# ws2812b-board.net
KiCad netlist of a schematic drawn in EAGLE
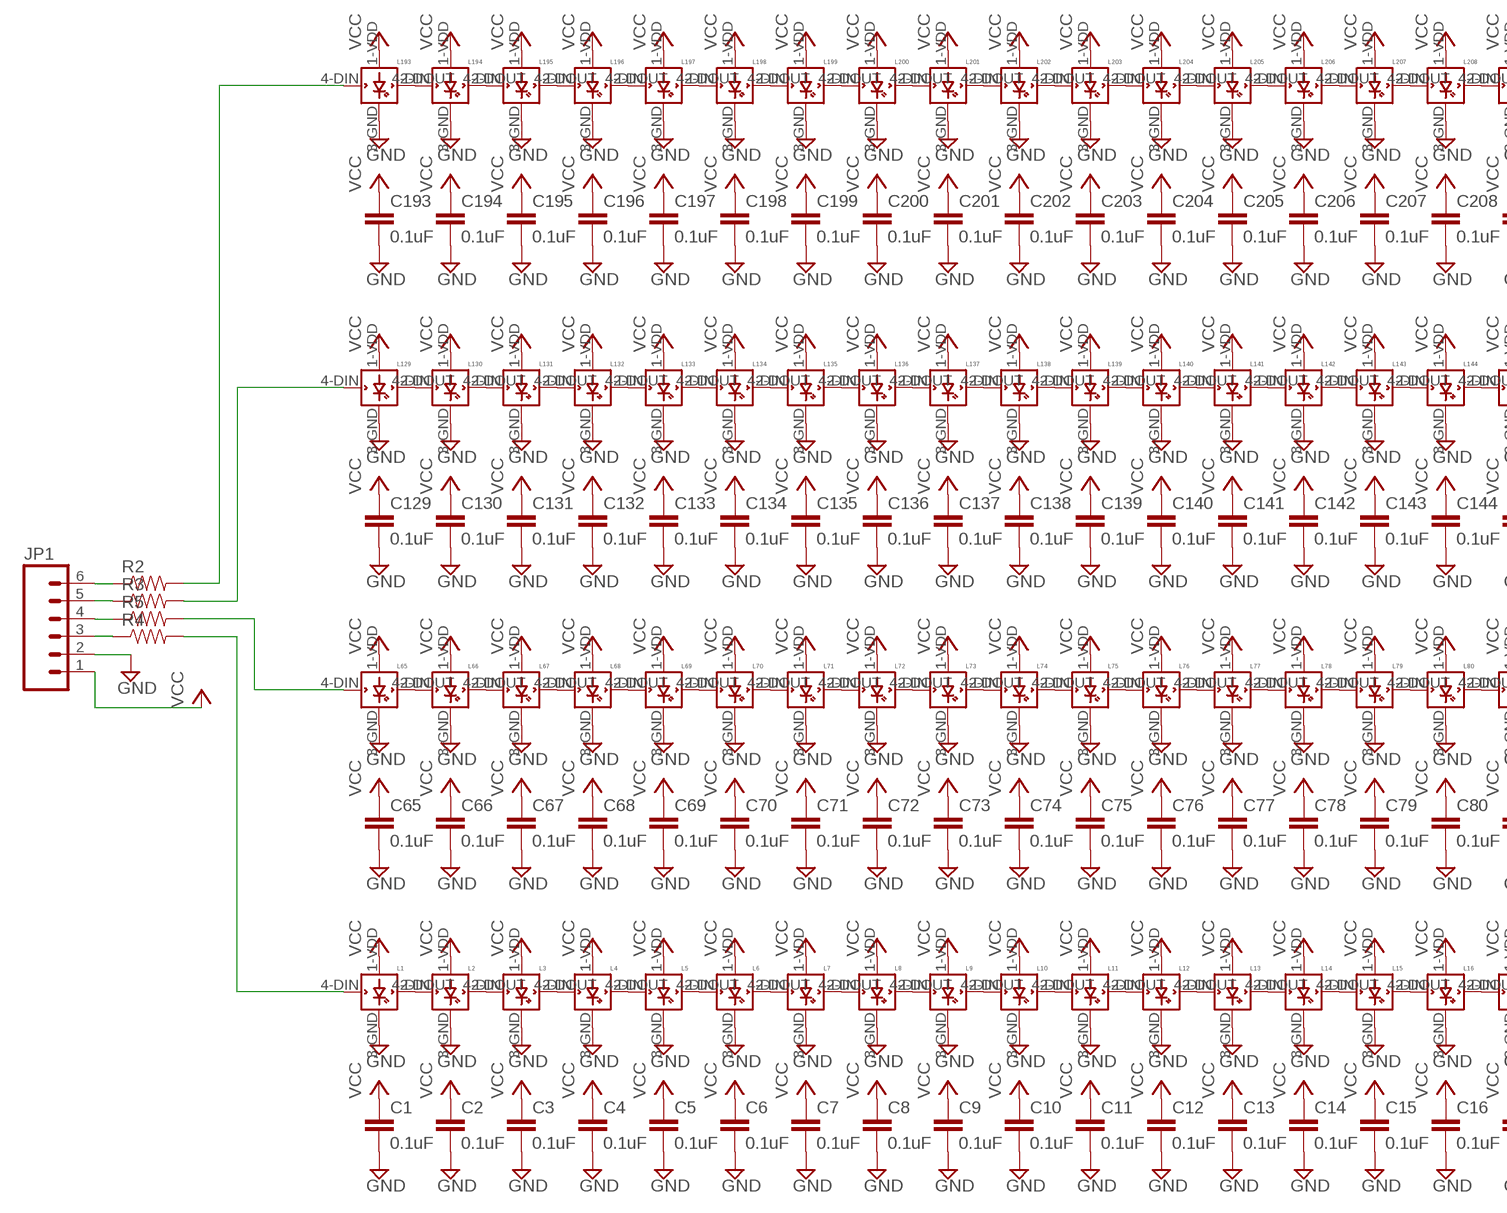
[diagram p0: schematic, sheet 1, part 1 of 2]
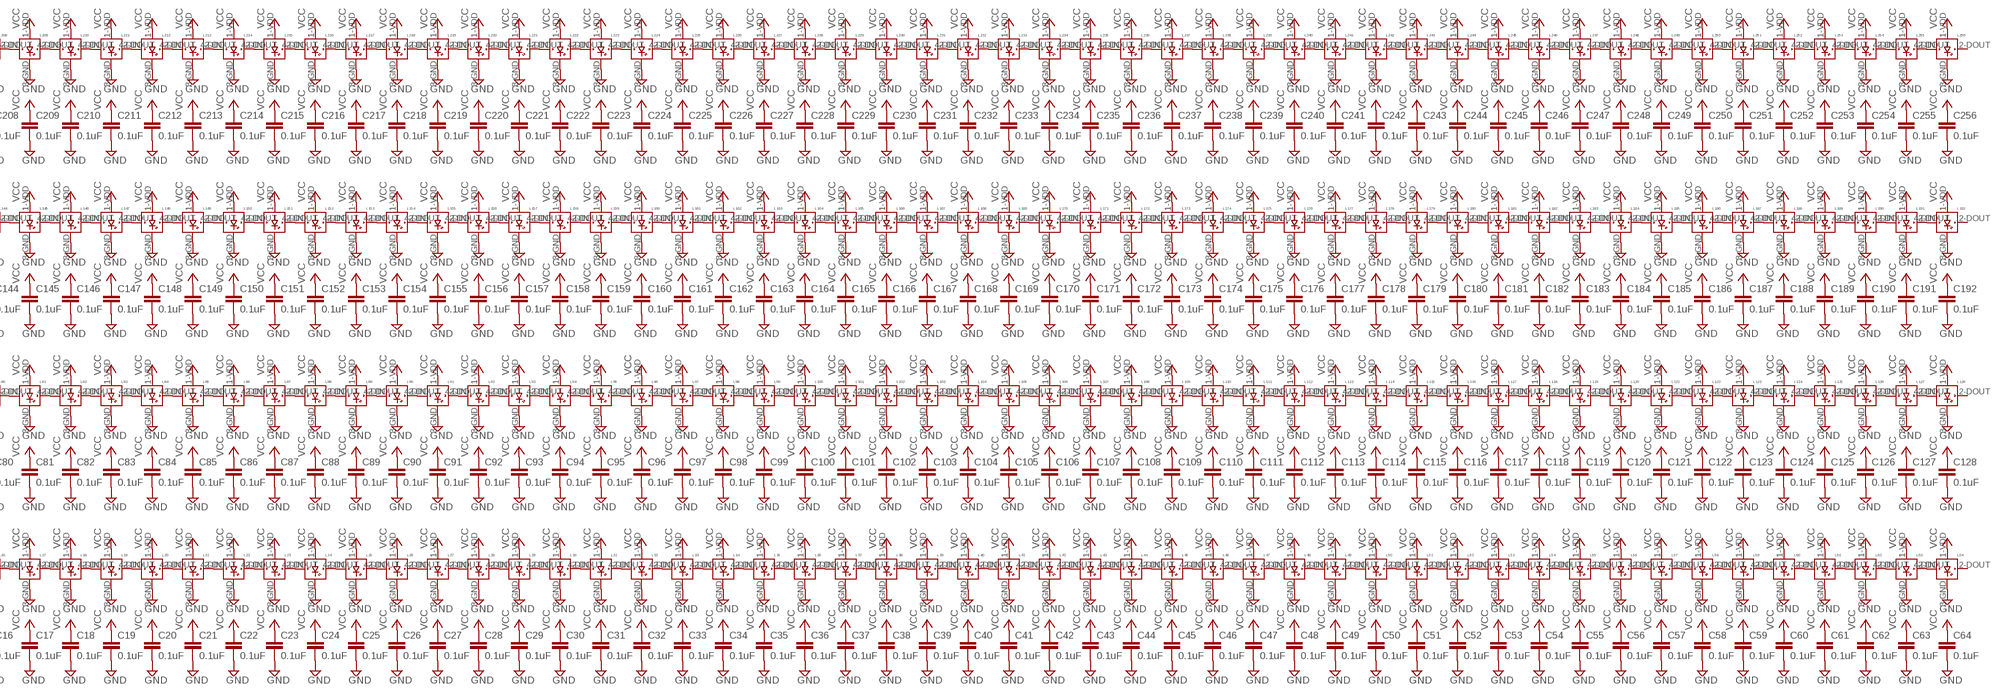
[diagram p1: schematic, sheet 1, part 2 of 2]

(export (version "E")
  (design (tool "Eeschema 10.0.6"))
  (components
    (comp (ref "C1")
      (value "0.1uF")
      (footprint "eagle-import:0603-CAP")
      (libsource (lib "eagle-import") (part "CAP0603-CAP"))
    )
    (comp (ref "C2")
      (value "0.1uF")
      (footprint "eagle-import:0603-CAP")
      (libsource (lib "eagle-import") (part "CAP0603-CAP"))
    )
    (comp (ref "C3")
      (value "0.1uF")
      (footprint "eagle-import:0603-CAP")
      (libsource (lib "eagle-import") (part "CAP0603-CAP"))
    )
    (comp (ref "C4")
      (value "0.1uF")
      (footprint "eagle-import:0603-CAP")
      (libsource (lib "eagle-import") (part "CAP0603-CAP"))
    )
    (comp (ref "C5")
      (value "0.1uF")
      (footprint "eagle-import:0603-CAP")
      (libsource (lib "eagle-import") (part "CAP0603-CAP"))
    )
    (comp (ref "C6")
      (value "0.1uF")
      (footprint "eagle-import:0603-CAP")
      (libsource (lib "eagle-import") (part "CAP0603-CAP"))
    )
    (comp (ref "C7")
      (value "0.1uF")
      (footprint "eagle-import:0603-CAP")
      (libsource (lib "eagle-import") (part "CAP0603-CAP"))
    )
    (comp (ref "C8")
      (value "0.1uF")
      (footprint "eagle-import:0603-CAP")
      (libsource (lib "eagle-import") (part "CAP0603-CAP"))
    )
    (comp (ref "C9")
      (value "0.1uF")
      (footprint "eagle-import:0603-CAP")
      (libsource (lib "eagle-import") (part "CAP0603-CAP"))
    )
    (comp (ref "C10")
      (value "0.1uF")
      (footprint "eagle-import:0603-CAP")
      (libsource (lib "eagle-import") (part "CAP0603-CAP"))
    )
    (comp (ref "C11")
      (value "0.1uF")
      (footprint "eagle-import:0603-CAP")
      (libsource (lib "eagle-import") (part "CAP0603-CAP"))
    )
    (comp (ref "C12")
      (value "0.1uF")
      (footprint "eagle-import:0603-CAP")
      (libsource (lib "eagle-import") (part "CAP0603-CAP"))
    )
    (comp (ref "C13")
      (value "0.1uF")
      (footprint "eagle-import:0603-CAP")
      (libsource (lib "eagle-import") (part "CAP0603-CAP"))
    )
    (comp (ref "C14")
      (value "0.1uF")
      (footprint "eagle-import:0603-CAP")
      (libsource (lib "eagle-import") (part "CAP0603-CAP"))
    )
    (comp (ref "C15")
      (value "0.1uF")
      (footprint "eagle-import:0603-CAP")
      (libsource (lib "eagle-import") (part "CAP0603-CAP"))
    )
    (comp (ref "C16")
      (value "0.1uF")
      (footprint "eagle-import:0603-CAP")
      (libsource (lib "eagle-import") (part "CAP0603-CAP"))
    )
    (comp (ref "C17")
      (value "0.1uF")
      (footprint "eagle-import:0603-CAP")
      (libsource (lib "eagle-import") (part "CAP0603-CAP"))
    )
    (comp (ref "C18")
      (value "0.1uF")
      (footprint "eagle-import:0603-CAP")
      (libsource (lib "eagle-import") (part "CAP0603-CAP"))
    )
    (comp (ref "C19")
      (value "0.1uF")
      (footprint "eagle-import:0603-CAP")
      (libsource (lib "eagle-import") (part "CAP0603-CAP"))
    )
    (comp (ref "C20")
      (value "0.1uF")
      (footprint "eagle-import:0603-CAP")
      (libsource (lib "eagle-import") (part "CAP0603-CAP"))
    )
    (comp (ref "C21")
      (value "0.1uF")
      (footprint "eagle-import:0603-CAP")
      (libsource (lib "eagle-import") (part "CAP0603-CAP"))
    )
    (comp (ref "C22")
      (value "0.1uF")
      (footprint "eagle-import:0603-CAP")
      (libsource (lib "eagle-import") (part "CAP0603-CAP"))
    )
    (comp (ref "C23")
      (value "0.1uF")
      (footprint "eagle-import:0603-CAP")
      (libsource (lib "eagle-import") (part "CAP0603-CAP"))
    )
    (comp (ref "C24")
      (value "0.1uF")
      (footprint "eagle-import:0603-CAP")
      (libsource (lib "eagle-import") (part "CAP0603-CAP"))
    )
    (comp (ref "C25")
      (value "0.1uF")
      (footprint "eagle-import:0603-CAP")
      (libsource (lib "eagle-import") (part "CAP0603-CAP"))
    )
    (comp (ref "C26")
      (value "0.1uF")
      (footprint "eagle-import:0603-CAP")
      (libsource (lib "eagle-import") (part "CAP0603-CAP"))
    )
    (comp (ref "C27")
      (value "0.1uF")
      (footprint "eagle-import:0603-CAP")
      (libsource (lib "eagle-import") (part "CAP0603-CAP"))
    )
    (comp (ref "C28")
      (value "0.1uF")
      (footprint "eagle-import:0603-CAP")
      (libsource (lib "eagle-import") (part "CAP0603-CAP"))
    )
    (comp (ref "C29")
      (value "0.1uF")
      (footprint "eagle-import:0603-CAP")
      (libsource (lib "eagle-import") (part "CAP0603-CAP"))
    )
    (comp (ref "C30")
      (value "0.1uF")
      (footprint "eagle-import:0603-CAP")
      (libsource (lib "eagle-import") (part "CAP0603-CAP"))
    )
    (comp (ref "C31")
      (value "0.1uF")
      (footprint "eagle-import:0603-CAP")
      (libsource (lib "eagle-import") (part "CAP0603-CAP"))
    )
    (comp (ref "C32")
      (value "0.1uF")
      (footprint "eagle-import:0603-CAP")
      (libsource (lib "eagle-import") (part "CAP0603-CAP"))
    )
    (comp (ref "C33")
      (value "0.1uF")
      (footprint "eagle-import:0603-CAP")
      (libsource (lib "eagle-import") (part "CAP0603-CAP"))
    )
    (comp (ref "C34")
      (value "0.1uF")
      (footprint "eagle-import:0603-CAP")
      (libsource (lib "eagle-import") (part "CAP0603-CAP"))
    )
    (comp (ref "C35")
      (value "0.1uF")
      (footprint "eagle-import:0603-CAP")
      (libsource (lib "eagle-import") (part "CAP0603-CAP"))
    )
    (comp (ref "C36")
      (value "0.1uF")
      (footprint "eagle-import:0603-CAP")
      (libsource (lib "eagle-import") (part "CAP0603-CAP"))
    )
    (comp (ref "C37")
      (value "0.1uF")
      (footprint "eagle-import:0603-CAP")
      (libsource (lib "eagle-import") (part "CAP0603-CAP"))
    )
    (comp (ref "C38")
      (value "0.1uF")
      (footprint "eagle-import:0603-CAP")
      (libsource (lib "eagle-import") (part "CAP0603-CAP"))
    )
    (comp (ref "C39")
      (value "0.1uF")
      (footprint "eagle-import:0603-CAP")
      (libsource (lib "eagle-import") (part "CAP0603-CAP"))
    )
    (comp (ref "C40")
      (value "0.1uF")
      (footprint "eagle-import:0603-CAP")
      (libsource (lib "eagle-import") (part "CAP0603-CAP"))
    )
    (comp (ref "C41")
      (value "0.1uF")
      (footprint "eagle-import:0603-CAP")
      (libsource (lib "eagle-import") (part "CAP0603-CAP"))
    )
    (comp (ref "C42")
      (value "0.1uF")
      (footprint "eagle-import:0603-CAP")
      (libsource (lib "eagle-import") (part "CAP0603-CAP"))
    )
    (comp (ref "C43")
      (value "0.1uF")
      (footprint "eagle-import:0603-CAP")
      (libsource (lib "eagle-import") (part "CAP0603-CAP"))
    )
    (comp (ref "C44")
      (value "0.1uF")
      (footprint "eagle-import:0603-CAP")
      (libsource (lib "eagle-import") (part "CAP0603-CAP"))
    )
    (comp (ref "C45")
      (value "0.1uF")
      (footprint "eagle-import:0603-CAP")
      (libsource (lib "eagle-import") (part "CAP0603-CAP"))
    )
    (comp (ref "C46")
      (value "0.1uF")
      (footprint "eagle-import:0603-CAP")
      (libsource (lib "eagle-import") (part "CAP0603-CAP"))
    )
    (comp (ref "C47")
      (value "0.1uF")
      (footprint "eagle-import:0603-CAP")
      (libsource (lib "eagle-import") (part "CAP0603-CAP"))
    )
    (comp (ref "C48")
      (value "0.1uF")
      (footprint "eagle-import:0603-CAP")
      (libsource (lib "eagle-import") (part "CAP0603-CAP"))
    )
    (comp (ref "C49")
      (value "0.1uF")
      (footprint "eagle-import:0603-CAP")
      (libsource (lib "eagle-import") (part "CAP0603-CAP"))
    )
    (comp (ref "C50")
      (value "0.1uF")
      (footprint "eagle-import:0603-CAP")
      (libsource (lib "eagle-import") (part "CAP0603-CAP"))
    )
    (comp (ref "C51")
      (value "0.1uF")
      (footprint "eagle-import:0603-CAP")
      (libsource (lib "eagle-import") (part "CAP0603-CAP"))
    )
    (comp (ref "C52")
      (value "0.1uF")
      (footprint "eagle-import:0603-CAP")
      (libsource (lib "eagle-import") (part "CAP0603-CAP"))
    )
    (comp (ref "C53")
      (value "0.1uF")
      (footprint "eagle-import:0603-CAP")
      (libsource (lib "eagle-import") (part "CAP0603-CAP"))
    )
    (comp (ref "C54")
      (value "0.1uF")
      (footprint "eagle-import:0603-CAP")
      (libsource (lib "eagle-import") (part "CAP0603-CAP"))
    )
    (comp (ref "C55")
      (value "0.1uF")
      (footprint "eagle-import:0603-CAP")
      (libsource (lib "eagle-import") (part "CAP0603-CAP"))
    )
    (comp (ref "C56")
      (value "0.1uF")
      (footprint "eagle-import:0603-CAP")
      (libsource (lib "eagle-import") (part "CAP0603-CAP"))
    )
    (comp (ref "C57")
      (value "0.1uF")
      (footprint "eagle-import:0603-CAP")
      (libsource (lib "eagle-import") (part "CAP0603-CAP"))
    )
    (comp (ref "C58")
      (value "0.1uF")
      (footprint "eagle-import:0603-CAP")
      (libsource (lib "eagle-import") (part "CAP0603-CAP"))
    )
    (comp (ref "C59")
      (value "0.1uF")
      (footprint "eagle-import:0603-CAP")
      (libsource (lib "eagle-import") (part "CAP0603-CAP"))
    )
    (comp (ref "C60")
      (value "0.1uF")
      (footprint "eagle-import:0603-CAP")
      (libsource (lib "eagle-import") (part "CAP0603-CAP"))
    )
    (comp (ref "C61")
      (value "0.1uF")
      (footprint "eagle-import:0603-CAP")
      (libsource (lib "eagle-import") (part "CAP0603-CAP"))
    )
    (comp (ref "C62")
      (value "0.1uF")
      (footprint "eagle-import:0603-CAP")
      (libsource (lib "eagle-import") (part "CAP0603-CAP"))
    )
    (comp (ref "C63")
      (value "0.1uF")
      (footprint "eagle-import:0603-CAP")
      (libsource (lib "eagle-import") (part "CAP0603-CAP"))
    )
    (comp (ref "C64")
      (value "0.1uF")
      (footprint "eagle-import:0603-CAP")
      (libsource (lib "eagle-import") (part "CAP0603-CAP"))
    )
    (comp (ref "C65")
      (value "0.1uF")
      (footprint "eagle-import:0603-CAP")
      (libsource (lib "eagle-import") (part "CAP0603-CAP"))
    )
    (comp (ref "C66")
      (value "0.1uF")
      (footprint "eagle-import:0603-CAP")
      (libsource (lib "eagle-import") (part "CAP0603-CAP"))
    )
    (comp (ref "C67")
      (value "0.1uF")
      (footprint "eagle-import:0603-CAP")
      (libsource (lib "eagle-import") (part "CAP0603-CAP"))
    )
    (comp (ref "C68")
      (value "0.1uF")
      (footprint "eagle-import:0603-CAP")
      (libsource (lib "eagle-import") (part "CAP0603-CAP"))
    )
    (comp (ref "C69")
      (value "0.1uF")
      (footprint "eagle-import:0603-CAP")
      (libsource (lib "eagle-import") (part "CAP0603-CAP"))
    )
    (comp (ref "C70")
      (value "0.1uF")
      (footprint "eagle-import:0603-CAP")
      (libsource (lib "eagle-import") (part "CAP0603-CAP"))
    )
    (comp (ref "C71")
      (value "0.1uF")
      (footprint "eagle-import:0603-CAP")
      (libsource (lib "eagle-import") (part "CAP0603-CAP"))
    )
    (comp (ref "C72")
      (value "0.1uF")
      (footprint "eagle-import:0603-CAP")
      (libsource (lib "eagle-import") (part "CAP0603-CAP"))
    )
    (comp (ref "C73")
      (value "0.1uF")
      (footprint "eagle-import:0603-CAP")
      (libsource (lib "eagle-import") (part "CAP0603-CAP"))
    )
    (comp (ref "C74")
      (value "0.1uF")
      (footprint "eagle-import:0603-CAP")
      (libsource (lib "eagle-import") (part "CAP0603-CAP"))
    )
    (comp (ref "C75")
      (value "0.1uF")
      (footprint "eagle-import:0603-CAP")
      (libsource (lib "eagle-import") (part "CAP0603-CAP"))
    )
    (comp (ref "C76")
      (value "0.1uF")
      (footprint "eagle-import:0603-CAP")
      (libsource (lib "eagle-import") (part "CAP0603-CAP"))
    )
    (comp (ref "C77")
      (value "0.1uF")
      (footprint "eagle-import:0603-CAP")
      (libsource (lib "eagle-import") (part "CAP0603-CAP"))
    )
    (comp (ref "C78")
      (value "0.1uF")
      (footprint "eagle-import:0603-CAP")
      (libsource (lib "eagle-import") (part "CAP0603-CAP"))
    )
    (comp (ref "C79")
      (value "0.1uF")
      (footprint "eagle-import:0603-CAP")
      (libsource (lib "eagle-import") (part "CAP0603-CAP"))
    )
    (comp (ref "C80")
      (value "0.1uF")
      (footprint "eagle-import:0603-CAP")
      (libsource (lib "eagle-import") (part "CAP0603-CAP"))
    )
    (comp (ref "C81")
      (value "0.1uF")
      (footprint "eagle-import:0603-CAP")
      (libsource (lib "eagle-import") (part "CAP0603-CAP"))
    )
    (comp (ref "C82")
      (value "0.1uF")
      (footprint "eagle-import:0603-CAP")
      (libsource (lib "eagle-import") (part "CAP0603-CAP"))
    )
    (comp (ref "C83")
      (value "0.1uF")
      (footprint "eagle-import:0603-CAP")
      (libsource (lib "eagle-import") (part "CAP0603-CAP"))
    )
    (comp (ref "C84")
      (value "0.1uF")
      (footprint "eagle-import:0603-CAP")
      (libsource (lib "eagle-import") (part "CAP0603-CAP"))
    )
    (comp (ref "C85")
      (value "0.1uF")
      (footprint "eagle-import:0603-CAP")
      (libsource (lib "eagle-import") (part "CAP0603-CAP"))
    )
    (comp (ref "C86")
      (value "0.1uF")
      (footprint "eagle-import:0603-CAP")
      (libsource (lib "eagle-import") (part "CAP0603-CAP"))
    )
    (comp (ref "C87")
      (value "0.1uF")
      (footprint "eagle-import:0603-CAP")
      (libsource (lib "eagle-import") (part "CAP0603-CAP"))
    )
    (comp (ref "C88")
      (value "0.1uF")
      (footprint "eagle-import:0603-CAP")
      (libsource (lib "eagle-import") (part "CAP0603-CAP"))
    )
    (comp (ref "C89")
      (value "0.1uF")
      (footprint "eagle-import:0603-CAP")
      (libsource (lib "eagle-import") (part "CAP0603-CAP"))
    )
    (comp (ref "C90")
      (value "0.1uF")
      (footprint "eagle-import:0603-CAP")
      (libsource (lib "eagle-import") (part "CAP0603-CAP"))
    )
    (comp (ref "C91")
      (value "0.1uF")
      (footprint "eagle-import:0603-CAP")
      (libsource (lib "eagle-import") (part "CAP0603-CAP"))
    )
    (comp (ref "C92")
      (value "0.1uF")
      (footprint "eagle-import:0603-CAP")
      (libsource (lib "eagle-import") (part "CAP0603-CAP"))
    )
    (comp (ref "C93")
      (value "0.1uF")
      (footprint "eagle-import:0603-CAP")
      (libsource (lib "eagle-import") (part "CAP0603-CAP"))
    )
    (comp (ref "C94")
      (value "0.1uF")
      (footprint "eagle-import:0603-CAP")
      (libsource (lib "eagle-import") (part "CAP0603-CAP"))
    )
    (comp (ref "C95")
      (value "0.1uF")
      (footprint "eagle-import:0603-CAP")
      (libsource (lib "eagle-import") (part "CAP0603-CAP"))
    )
    (comp (ref "C96")
      (value "0.1uF")
      (footprint "eagle-import:0603-CAP")
      (libsource (lib "eagle-import") (part "CAP0603-CAP"))
    )
    (comp (ref "C97")
      (value "0.1uF")
      (footprint "eagle-import:0603-CAP")
      (libsource (lib "eagle-import") (part "CAP0603-CAP"))
    )
    (comp (ref "C98")
      (value "0.1uF")
      (footprint "eagle-import:0603-CAP")
      (libsource (lib "eagle-import") (part "CAP0603-CAP"))
    )
    (comp (ref "C99")
      (value "0.1uF")
      (footprint "eagle-import:0603-CAP")
      (libsource (lib "eagle-import") (part "CAP0603-CAP"))
    )
    (comp (ref "C100")
      (value "0.1uF")
      (footprint "eagle-import:0603-CAP")
      (libsource (lib "eagle-import") (part "CAP0603-CAP"))
    )
    (comp (ref "C101")
      (value "0.1uF")
      (footprint "eagle-import:0603-CAP")
      (libsource (lib "eagle-import") (part "CAP0603-CAP"))
    )
    (comp (ref "C102")
      (value "0.1uF")
      (footprint "eagle-import:0603-CAP")
      (libsource (lib "eagle-import") (part "CAP0603-CAP"))
    )
    (comp (ref "C103")
      (value "0.1uF")
      (footprint "eagle-import:0603-CAP")
      (libsource (lib "eagle-import") (part "CAP0603-CAP"))
    )
    (comp (ref "C104")
      (value "0.1uF")
      (footprint "eagle-import:0603-CAP")
      (libsource (lib "eagle-import") (part "CAP0603-CAP"))
    )
    (comp (ref "C105")
      (value "0.1uF")
      (footprint "eagle-import:0603-CAP")
      (libsource (lib "eagle-import") (part "CAP0603-CAP"))
    )
    (comp (ref "C106")
      (value "0.1uF")
      (footprint "eagle-import:0603-CAP")
      (libsource (lib "eagle-import") (part "CAP0603-CAP"))
    )
    (comp (ref "C107")
      (value "0.1uF")
      (footprint "eagle-import:0603-CAP")
      (libsource (lib "eagle-import") (part "CAP0603-CAP"))
    )
    (comp (ref "C108")
      (value "0.1uF")
      (footprint "eagle-import:0603-CAP")
      (libsource (lib "eagle-import") (part "CAP0603-CAP"))
    )
    (comp (ref "C109")
      (value "0.1uF")
      (footprint "eagle-import:0603-CAP")
      (libsource (lib "eagle-import") (part "CAP0603-CAP"))
    )
    (comp (ref "C110")
      (value "0.1uF")
      (footprint "eagle-import:0603-CAP")
      (libsource (lib "eagle-import") (part "CAP0603-CAP"))
    )
    (comp (ref "C111")
      (value "0.1uF")
      (footprint "eagle-import:0603-CAP")
      (libsource (lib "eagle-import") (part "CAP0603-CAP"))
    )
    (comp (ref "C112")
      (value "0.1uF")
      (footprint "eagle-import:0603-CAP")
      (libsource (lib "eagle-import") (part "CAP0603-CAP"))
    )
    (comp (ref "C113")
      (value "0.1uF")
      (footprint "eagle-import:0603-CAP")
      (libsource (lib "eagle-import") (part "CAP0603-CAP"))
    )
    (comp (ref "C114")
      (value "0.1uF")
      (footprint "eagle-import:0603-CAP")
      (libsource (lib "eagle-import") (part "CAP0603-CAP"))
    )
    (comp (ref "C115")
      (value "0.1uF")
      (footprint "eagle-import:0603-CAP")
      (libsource (lib "eagle-import") (part "CAP0603-CAP"))
    )
    (comp (ref "C116")
      (value "0.1uF")
      (footprint "eagle-import:0603-CAP")
      (libsource (lib "eagle-import") (part "CAP0603-CAP"))
    )
    (comp (ref "C117")
      (value "0.1uF")
      (footprint "eagle-import:0603-CAP")
      (libsource (lib "eagle-import") (part "CAP0603-CAP"))
    )
    (comp (ref "C118")
      (value "0.1uF")
      (footprint "eagle-import:0603-CAP")
      (libsource (lib "eagle-import") (part "CAP0603-CAP"))
    )
    (comp (ref "C119")
      (value "0.1uF")
      (footprint "eagle-import:0603-CAP")
      (libsource (lib "eagle-import") (part "CAP0603-CAP"))
    )
    (comp (ref "C120")
      (value "0.1uF")
      (footprint "eagle-import:0603-CAP")
      (libsource (lib "eagle-import") (part "CAP0603-CAP"))
    )
    (comp (ref "C121")
      (value "0.1uF")
      (footprint "eagle-import:0603-CAP")
      (libsource (lib "eagle-import") (part "CAP0603-CAP"))
    )
    (comp (ref "C122")
      (value "0.1uF")
      (footprint "eagle-import:0603-CAP")
      (libsource (lib "eagle-import") (part "CAP0603-CAP"))
    )
    (comp (ref "C123")
      (value "0.1uF")
      (footprint "eagle-import:0603-CAP")
      (libsource (lib "eagle-import") (part "CAP0603-CAP"))
    )
    (comp (ref "C124")
      (value "0.1uF")
      (footprint "eagle-import:0603-CAP")
      (libsource (lib "eagle-import") (part "CAP0603-CAP"))
    )
    (comp (ref "C125")
      (value "0.1uF")
      (footprint "eagle-import:0603-CAP")
      (libsource (lib "eagle-import") (part "CAP0603-CAP"))
    )
    (comp (ref "C126")
      (value "0.1uF")
      (footprint "eagle-import:0603-CAP")
      (libsource (lib "eagle-import") (part "CAP0603-CAP"))
    )
    (comp (ref "C127")
      (value "0.1uF")
      (footprint "eagle-import:0603-CAP")
      (libsource (lib "eagle-import") (part "CAP0603-CAP"))
    )
    (comp (ref "C128")
      (value "0.1uF")
      (footprint "eagle-import:0603-CAP")
      (libsource (lib "eagle-import") (part "CAP0603-CAP"))
    )
    (comp (ref "C129")
      (value "0.1uF")
      (footprint "eagle-import:0603-CAP")
      (libsource (lib "eagle-import") (part "CAP0603-CAP"))
    )
    (comp (ref "C130")
      (value "0.1uF")
      (footprint "eagle-import:0603-CAP")
      (libsource (lib "eagle-import") (part "CAP0603-CAP"))
    )
    (comp (ref "C131")
      (value "0.1uF")
      (footprint "eagle-import:0603-CAP")
      (libsource (lib "eagle-import") (part "CAP0603-CAP"))
    )
    (comp (ref "C132")
      (value "0.1uF")
      (footprint "eagle-import:0603-CAP")
      (libsource (lib "eagle-import") (part "CAP0603-CAP"))
    )
    (comp (ref "C133")
      (value "0.1uF")
      (footprint "eagle-import:0603-CAP")
      (libsource (lib "eagle-import") (part "CAP0603-CAP"))
    )
    (comp (ref "C134")
      (value "0.1uF")
      (footprint "eagle-import:0603-CAP")
      (libsource (lib "eagle-import") (part "CAP0603-CAP"))
    )
    (comp (ref "C135")
      (value "0.1uF")
      (footprint "eagle-import:0603-CAP")
      (libsource (lib "eagle-import") (part "CAP0603-CAP"))
    )
    (comp (ref "C136")
      (value "0.1uF")
      (footprint "eagle-import:0603-CAP")
      (libsource (lib "eagle-import") (part "CAP0603-CAP"))
    )
    (comp (ref "C137")
      (value "0.1uF")
      (footprint "eagle-import:0603-CAP")
      (libsource (lib "eagle-import") (part "CAP0603-CAP"))
    )
    (comp (ref "C138")
      (value "0.1uF")
      (footprint "eagle-import:0603-CAP")
      (libsource (lib "eagle-import") (part "CAP0603-CAP"))
    )
    (comp (ref "C139")
      (value "0.1uF")
      (footprint "eagle-import:0603-CAP")
      (libsource (lib "eagle-import") (part "CAP0603-CAP"))
    )
    (comp (ref "C140")
      (value "0.1uF")
      (footprint "eagle-import:0603-CAP")
      (libsource (lib "eagle-import") (part "CAP0603-CAP"))
    )
    (comp (ref "C141")
      (value "0.1uF")
      (footprint "eagle-import:0603-CAP")
      (libsource (lib "eagle-import") (part "CAP0603-CAP"))
    )
    (comp (ref "C142")
      (value "0.1uF")
      (footprint "eagle-import:0603-CAP")
      (libsource (lib "eagle-import") (part "CAP0603-CAP"))
    )
    (comp (ref "C143")
      (value "0.1uF")
      (footprint "eagle-import:0603-CAP")
      (libsource (lib "eagle-import") (part "CAP0603-CAP"))
    )
    (comp (ref "C144")
      (value "0.1uF")
      (footprint "eagle-import:0603-CAP")
      (libsource (lib "eagle-import") (part "CAP0603-CAP"))
    )
    (comp (ref "C145")
      (value "0.1uF")
      (footprint "eagle-import:0603-CAP")
      (libsource (lib "eagle-import") (part "CAP0603-CAP"))
    )
    (comp (ref "C146")
      (value "0.1uF")
      (footprint "eagle-import:0603-CAP")
      (libsource (lib "eagle-import") (part "CAP0603-CAP"))
    )
    (comp (ref "C147")
      (value "0.1uF")
      (footprint "eagle-import:0603-CAP")
      (libsource (lib "eagle-import") (part "CAP0603-CAP"))
    )
    (comp (ref "C148")
      (value "0.1uF")
      (footprint "eagle-import:0603-CAP")
      (libsource (lib "eagle-import") (part "CAP0603-CAP"))
    )
    (comp (ref "C149")
      (value "0.1uF")
      (footprint "eagle-import:0603-CAP")
      (libsource (lib "eagle-import") (part "CAP0603-CAP"))
    )
    (comp (ref "C150")
      (value "0.1uF")
      (footprint "eagle-import:0603-CAP")
      (libsource (lib "eagle-import") (part "CAP0603-CAP"))
    )
    (comp (ref "C151")
      (value "0.1uF")
      (footprint "eagle-import:0603-CAP")
      (libsource (lib "eagle-import") (part "CAP0603-CAP"))
    )
    (comp (ref "C152")
      (value "0.1uF")
      (footprint "eagle-import:0603-CAP")
      (libsource (lib "eagle-import") (part "CAP0603-CAP"))
    )
    (comp (ref "C153")
      (value "0.1uF")
      (footprint "eagle-import:0603-CAP")
      (libsource (lib "eagle-import") (part "CAP0603-CAP"))
    )
    (comp (ref "C154")
      (value "0.1uF")
      (footprint "eagle-import:0603-CAP")
      (libsource (lib "eagle-import") (part "CAP0603-CAP"))
    )
    (comp (ref "C155")
      (value "0.1uF")
      (footprint "eagle-import:0603-CAP")
      (libsource (lib "eagle-import") (part "CAP0603-CAP"))
    )
    (comp (ref "C156")
      (value "0.1uF")
      (footprint "eagle-import:0603-CAP")
      (libsource (lib "eagle-import") (part "CAP0603-CAP"))
    )
    (comp (ref "C157")
      (value "0.1uF")
      (footprint "eagle-import:0603-CAP")
      (libsource (lib "eagle-import") (part "CAP0603-CAP"))
    )
    (comp (ref "C158")
      (value "0.1uF")
      (footprint "eagle-import:0603-CAP")
      (libsource (lib "eagle-import") (part "CAP0603-CAP"))
    )
    (comp (ref "C159")
      (value "0.1uF")
      (footprint "eagle-import:0603-CAP")
      (libsource (lib "eagle-import") (part "CAP0603-CAP"))
    )
    (comp (ref "C160")
      (value "0.1uF")
      (footprint "eagle-import:0603-CAP")
      (libsource (lib "eagle-import") (part "CAP0603-CAP"))
    )
    (comp (ref "C161")
      (value "0.1uF")
      (footprint "eagle-import:0603-CAP")
      (libsource (lib "eagle-import") (part "CAP0603-CAP"))
    )
    (comp (ref "C162")
      (value "0.1uF")
      (footprint "eagle-import:0603-CAP")
      (libsource (lib "eagle-import") (part "CAP0603-CAP"))
    )
    (comp (ref "C163")
      (value "0.1uF")
      (footprint "eagle-import:0603-CAP")
      (libsource (lib "eagle-import") (part "CAP0603-CAP"))
    )
    (comp (ref "C164")
      (value "0.1uF")
      (footprint "eagle-import:0603-CAP")
      (libsource (lib "eagle-import") (part "CAP0603-CAP"))
    )
    (comp (ref "C165")
      (value "0.1uF")
      (footprint "eagle-import:0603-CAP")
      (libsource (lib "eagle-import") (part "CAP0603-CAP"))
    )
    (comp (ref "C166")
      (value "0.1uF")
      (footprint "eagle-import:0603-CAP")
      (libsource (lib "eagle-import") (part "CAP0603-CAP"))
    )
    (comp (ref "C167")
      (value "0.1uF")
      (footprint "eagle-import:0603-CAP")
      (libsource (lib "eagle-import") (part "CAP0603-CAP"))
    )
    (comp (ref "C168")
      (value "0.1uF")
      (footprint "eagle-import:0603-CAP")
      (libsource (lib "eagle-import") (part "CAP0603-CAP"))
    )
    (comp (ref "C169")
      (value "0.1uF")
      (footprint "eagle-import:0603-CAP")
      (libsource (lib "eagle-import") (part "CAP0603-CAP"))
    )
    (comp (ref "C170")
      (value "0.1uF")
      (footprint "eagle-import:0603-CAP")
      (libsource (lib "eagle-import") (part "CAP0603-CAP"))
    )
    (comp (ref "C171")
      (value "0.1uF")
      (footprint "eagle-import:0603-CAP")
      (libsource (lib "eagle-import") (part "CAP0603-CAP"))
    )
    (comp (ref "C172")
      (value "0.1uF")
      (footprint "eagle-import:0603-CAP")
      (libsource (lib "eagle-import") (part "CAP0603-CAP"))
    )
    (comp (ref "C173")
      (value "0.1uF")
      (footprint "eagle-import:0603-CAP")
      (libsource (lib "eagle-import") (part "CAP0603-CAP"))
    )
    (comp (ref "C174")
      (value "0.1uF")
      (footprint "eagle-import:0603-CAP")
      (libsource (lib "eagle-import") (part "CAP0603-CAP"))
    )
    (comp (ref "C175")
      (value "0.1uF")
      (footprint "eagle-import:0603-CAP")
      (libsource (lib "eagle-import") (part "CAP0603-CAP"))
    )
    (comp (ref "C176")
      (value "0.1uF")
      (footprint "eagle-import:0603-CAP")
      (libsource (lib "eagle-import") (part "CAP0603-CAP"))
    )
    (comp (ref "C177")
      (value "0.1uF")
      (footprint "eagle-import:0603-CAP")
      (libsource (lib "eagle-import") (part "CAP0603-CAP"))
    )
    (comp (ref "C178")
      (value "0.1uF")
      (footprint "eagle-import:0603-CAP")
      (libsource (lib "eagle-import") (part "CAP0603-CAP"))
    )
    (comp (ref "C179")
      (value "0.1uF")
      (footprint "eagle-import:0603-CAP")
      (libsource (lib "eagle-import") (part "CAP0603-CAP"))
    )
    (comp (ref "C180")
      (value "0.1uF")
      (footprint "eagle-import:0603-CAP")
      (libsource (lib "eagle-import") (part "CAP0603-CAP"))
    )
    (comp (ref "C181")
      (value "0.1uF")
      (footprint "eagle-import:0603-CAP")
      (libsource (lib "eagle-import") (part "CAP0603-CAP"))
    )
    (comp (ref "C182")
      (value "0.1uF")
      (footprint "eagle-import:0603-CAP")
      (libsource (lib "eagle-import") (part "CAP0603-CAP"))
    )
    (comp (ref "C183")
      (value "0.1uF")
      (footprint "eagle-import:0603-CAP")
      (libsource (lib "eagle-import") (part "CAP0603-CAP"))
    )
    (comp (ref "C184")
      (value "0.1uF")
      (footprint "eagle-import:0603-CAP")
      (libsource (lib "eagle-import") (part "CAP0603-CAP"))
    )
    (comp (ref "C185")
      (value "0.1uF")
      (footprint "eagle-import:0603-CAP")
      (libsource (lib "eagle-import") (part "CAP0603-CAP"))
    )
    (comp (ref "C186")
      (value "0.1uF")
      (footprint "eagle-import:0603-CAP")
      (libsource (lib "eagle-import") (part "CAP0603-CAP"))
    )
    (comp (ref "C187")
      (value "0.1uF")
      (footprint "eagle-import:0603-CAP")
      (libsource (lib "eagle-import") (part "CAP0603-CAP"))
    )
    (comp (ref "C188")
      (value "0.1uF")
      (footprint "eagle-import:0603-CAP")
      (libsource (lib "eagle-import") (part "CAP0603-CAP"))
    )
    (comp (ref "C189")
      (value "0.1uF")
      (footprint "eagle-import:0603-CAP")
      (libsource (lib "eagle-import") (part "CAP0603-CAP"))
    )
    (comp (ref "C190")
      (value "0.1uF")
      (footprint "eagle-import:0603-CAP")
      (libsource (lib "eagle-import") (part "CAP0603-CAP"))
    )
    (comp (ref "C191")
      (value "0.1uF")
      (footprint "eagle-import:0603-CAP")
      (libsource (lib "eagle-import") (part "CAP0603-CAP"))
    )
    (comp (ref "C192")
      (value "0.1uF")
      (footprint "eagle-import:0603-CAP")
      (libsource (lib "eagle-import") (part "CAP0603-CAP"))
    )
    (comp (ref "C193")
      (value "0.1uF")
      (footprint "eagle-import:0603-CAP")
      (libsource (lib "eagle-import") (part "CAP0603-CAP"))
    )
    (comp (ref "C194")
      (value "0.1uF")
      (footprint "eagle-import:0603-CAP")
      (libsource (lib "eagle-import") (part "CAP0603-CAP"))
    )
    (comp (ref "C195")
      (value "0.1uF")
      (footprint "eagle-import:0603-CAP")
      (libsource (lib "eagle-import") (part "CAP0603-CAP"))
    )
    (comp (ref "C196")
      (value "0.1uF")
      (footprint "eagle-import:0603-CAP")
      (libsource (lib "eagle-import") (part "CAP0603-CAP"))
    )
    (comp (ref "C197")
      (value "0.1uF")
      (footprint "eagle-import:0603-CAP")
      (libsource (lib "eagle-import") (part "CAP0603-CAP"))
    )
    (comp (ref "C198")
      (value "0.1uF")
      (footprint "eagle-import:0603-CAP")
      (libsource (lib "eagle-import") (part "CAP0603-CAP"))
    )
    (comp (ref "C199")
      (value "0.1uF")
      (footprint "eagle-import:0603-CAP")
      (libsource (lib "eagle-import") (part "CAP0603-CAP"))
    )
    (comp (ref "C200")
      (value "0.1uF")
      (footprint "eagle-import:0603-CAP")
      (libsource (lib "eagle-import") (part "CAP0603-CAP"))
    )
    (comp (ref "C201")
      (value "0.1uF")
      (footprint "eagle-import:0603-CAP")
      (libsource (lib "eagle-import") (part "CAP0603-CAP"))
    )
    (comp (ref "C202")
      (value "0.1uF")
      (footprint "eagle-import:0603-CAP")
      (libsource (lib "eagle-import") (part "CAP0603-CAP"))
    )
    (comp (ref "C203")
      (value "0.1uF")
      (footprint "eagle-import:0603-CAP")
      (libsource (lib "eagle-import") (part "CAP0603-CAP"))
    )
    (comp (ref "C204")
      (value "0.1uF")
      (footprint "eagle-import:0603-CAP")
      (libsource (lib "eagle-import") (part "CAP0603-CAP"))
    )
    (comp (ref "C205")
      (value "0.1uF")
      (footprint "eagle-import:0603-CAP")
      (libsource (lib "eagle-import") (part "CAP0603-CAP"))
    )
    (comp (ref "C206")
      (value "0.1uF")
      (footprint "eagle-import:0603-CAP")
      (libsource (lib "eagle-import") (part "CAP0603-CAP"))
    )
    (comp (ref "C207")
      (value "0.1uF")
      (footprint "eagle-import:0603-CAP")
      (libsource (lib "eagle-import") (part "CAP0603-CAP"))
    )
    (comp (ref "C208")
      (value "0.1uF")
      (footprint "eagle-import:0603-CAP")
      (libsource (lib "eagle-import") (part "CAP0603-CAP"))
    )
    (comp (ref "C209")
      (value "0.1uF")
      (footprint "eagle-import:0603-CAP")
      (libsource (lib "eagle-import") (part "CAP0603-CAP"))
    )
    (comp (ref "C210")
      (value "0.1uF")
      (footprint "eagle-import:0603-CAP")
      (libsource (lib "eagle-import") (part "CAP0603-CAP"))
    )
    (comp (ref "C211")
      (value "0.1uF")
      (footprint "eagle-import:0603-CAP")
      (libsource (lib "eagle-import") (part "CAP0603-CAP"))
    )
    (comp (ref "C212")
      (value "0.1uF")
      (footprint "eagle-import:0603-CAP")
      (libsource (lib "eagle-import") (part "CAP0603-CAP"))
    )
    (comp (ref "C213")
      (value "0.1uF")
      (footprint "eagle-import:0603-CAP")
      (libsource (lib "eagle-import") (part "CAP0603-CAP"))
    )
    (comp (ref "C214")
      (value "0.1uF")
      (footprint "eagle-import:0603-CAP")
      (libsource (lib "eagle-import") (part "CAP0603-CAP"))
    )
    (comp (ref "C215")
      (value "0.1uF")
      (footprint "eagle-import:0603-CAP")
      (libsource (lib "eagle-import") (part "CAP0603-CAP"))
    )
    (comp (ref "C216")
      (value "0.1uF")
      (footprint "eagle-import:0603-CAP")
      (libsource (lib "eagle-import") (part "CAP0603-CAP"))
    )
    (comp (ref "C217")
      (value "0.1uF")
      (footprint "eagle-import:0603-CAP")
      (libsource (lib "eagle-import") (part "CAP0603-CAP"))
    )
    (comp (ref "C218")
      (value "0.1uF")
      (footprint "eagle-import:0603-CAP")
      (libsource (lib "eagle-import") (part "CAP0603-CAP"))
    )
    (comp (ref "C219")
      (value "0.1uF")
      (footprint "eagle-import:0603-CAP")
      (libsource (lib "eagle-import") (part "CAP0603-CAP"))
    )
    (comp (ref "C220")
      (value "0.1uF")
      (footprint "eagle-import:0603-CAP")
      (libsource (lib "eagle-import") (part "CAP0603-CAP"))
    )
    (comp (ref "C221")
      (value "0.1uF")
      (footprint "eagle-import:0603-CAP")
      (libsource (lib "eagle-import") (part "CAP0603-CAP"))
    )
    (comp (ref "C222")
      (value "0.1uF")
      (footprint "eagle-import:0603-CAP")
      (libsource (lib "eagle-import") (part "CAP0603-CAP"))
    )
    (comp (ref "C223")
      (value "0.1uF")
      (footprint "eagle-import:0603-CAP")
      (libsource (lib "eagle-import") (part "CAP0603-CAP"))
    )
    (comp (ref "C224")
      (value "0.1uF")
      (footprint "eagle-import:0603-CAP")
      (libsource (lib "eagle-import") (part "CAP0603-CAP"))
    )
    (comp (ref "C225")
      (value "0.1uF")
      (footprint "eagle-import:0603-CAP")
      (libsource (lib "eagle-import") (part "CAP0603-CAP"))
    )
    (comp (ref "C226")
      (value "0.1uF")
      (footprint "eagle-import:0603-CAP")
      (libsource (lib "eagle-import") (part "CAP0603-CAP"))
    )
    (comp (ref "C227")
      (value "0.1uF")
      (footprint "eagle-import:0603-CAP")
      (libsource (lib "eagle-import") (part "CAP0603-CAP"))
    )
    (comp (ref "C228")
      (value "0.1uF")
      (footprint "eagle-import:0603-CAP")
      (libsource (lib "eagle-import") (part "CAP0603-CAP"))
    )
    (comp (ref "C229")
      (value "0.1uF")
      (footprint "eagle-import:0603-CAP")
      (libsource (lib "eagle-import") (part "CAP0603-CAP"))
    )
    (comp (ref "C230")
      (value "0.1uF")
      (footprint "eagle-import:0603-CAP")
      (libsource (lib "eagle-import") (part "CAP0603-CAP"))
    )
    (comp (ref "C231")
      (value "0.1uF")
      (footprint "eagle-import:0603-CAP")
      (libsource (lib "eagle-import") (part "CAP0603-CAP"))
    )
    (comp (ref "C232")
      (value "0.1uF")
      (footprint "eagle-import:0603-CAP")
      (libsource (lib "eagle-import") (part "CAP0603-CAP"))
    )
    (comp (ref "C233")
      (value "0.1uF")
      (footprint "eagle-import:0603-CAP")
      (libsource (lib "eagle-import") (part "CAP0603-CAP"))
    )
    (comp (ref "C234")
      (value "0.1uF")
      (footprint "eagle-import:0603-CAP")
      (libsource (lib "eagle-import") (part "CAP0603-CAP"))
    )
    (comp (ref "C235")
      (value "0.1uF")
      (footprint "eagle-import:0603-CAP")
      (libsource (lib "eagle-import") (part "CAP0603-CAP"))
    )
    (comp (ref "C236")
      (value "0.1uF")
      (footprint "eagle-import:0603-CAP")
      (libsource (lib "eagle-import") (part "CAP0603-CAP"))
    )
    (comp (ref "C237")
      (value "0.1uF")
      (footprint "eagle-import:0603-CAP")
      (libsource (lib "eagle-import") (part "CAP0603-CAP"))
    )
    (comp (ref "C238")
      (value "0.1uF")
      (footprint "eagle-import:0603-CAP")
      (libsource (lib "eagle-import") (part "CAP0603-CAP"))
    )
    (comp (ref "C239")
      (value "0.1uF")
      (footprint "eagle-import:0603-CAP")
      (libsource (lib "eagle-import") (part "CAP0603-CAP"))
    )
    (comp (ref "C240")
      (value "0.1uF")
      (footprint "eagle-import:0603-CAP")
      (libsource (lib "eagle-import") (part "CAP0603-CAP"))
    )
    (comp (ref "C241")
      (value "0.1uF")
      (footprint "eagle-import:0603-CAP")
      (libsource (lib "eagle-import") (part "CAP0603-CAP"))
    )
    (comp (ref "C242")
      (value "0.1uF")
      (footprint "eagle-import:0603-CAP")
      (libsource (lib "eagle-import") (part "CAP0603-CAP"))
    )
    (comp (ref "C243")
      (value "0.1uF")
      (footprint "eagle-import:0603-CAP")
      (libsource (lib "eagle-import") (part "CAP0603-CAP"))
    )
    (comp (ref "C244")
      (value "0.1uF")
      (footprint "eagle-import:0603-CAP")
      (libsource (lib "eagle-import") (part "CAP0603-CAP"))
    )
    (comp (ref "C245")
      (value "0.1uF")
      (footprint "eagle-import:0603-CAP")
      (libsource (lib "eagle-import") (part "CAP0603-CAP"))
    )
    (comp (ref "C246")
      (value "0.1uF")
      (footprint "eagle-import:0603-CAP")
      (libsource (lib "eagle-import") (part "CAP0603-CAP"))
    )
    (comp (ref "C247")
      (value "0.1uF")
      (footprint "eagle-import:0603-CAP")
      (libsource (lib "eagle-import") (part "CAP0603-CAP"))
    )
    (comp (ref "C248")
      (value "0.1uF")
      (footprint "eagle-import:0603-CAP")
      (libsource (lib "eagle-import") (part "CAP0603-CAP"))
    )
    (comp (ref "C249")
      (value "0.1uF")
      (footprint "eagle-import:0603-CAP")
      (libsource (lib "eagle-import") (part "CAP0603-CAP"))
    )
    (comp (ref "C250")
      (value "0.1uF")
      (footprint "eagle-import:0603-CAP")
      (libsource (lib "eagle-import") (part "CAP0603-CAP"))
    )
    (comp (ref "C251")
      (value "0.1uF")
      (footprint "eagle-import:0603-CAP")
      (libsource (lib "eagle-import") (part "CAP0603-CAP"))
    )
    (comp (ref "C252")
      (value "0.1uF")
      (footprint "eagle-import:0603-CAP")
      (libsource (lib "eagle-import") (part "CAP0603-CAP"))
    )
    (comp (ref "C253")
      (value "0.1uF")
      (footprint "eagle-import:0603-CAP")
      (libsource (lib "eagle-import") (part "CAP0603-CAP"))
    )
    (comp (ref "C254")
      (value "0.1uF")
      (footprint "eagle-import:0603-CAP")
      (libsource (lib "eagle-import") (part "CAP0603-CAP"))
    )
    (comp (ref "C255")
      (value "0.1uF")
      (footprint "eagle-import:0603-CAP")
      (libsource (lib "eagle-import") (part "CAP0603-CAP"))
    )
    (comp (ref "C256")
      (value "0.1uF")
      (footprint "eagle-import:0603-CAP")
      (libsource (lib "eagle-import") (part "CAP0603-CAP"))
    )
    (comp (ref "JP1")
      (value "M06SIP")
      (footprint "eagle-import:1X06")
      (libsource (lib "eagle-import") (part "M06SIP"))
    )
    (comp (ref "L1")
      (value "WS2812B")
      (footprint "eagle-import:WS2812B")
      (libsource (lib "eagle-import") (part "WS2812B"))
    )
    (comp (ref "L2")
      (value "WS2812B")
      (footprint "eagle-import:WS2812B")
      (libsource (lib "eagle-import") (part "WS2812B"))
    )
    (comp (ref "L3")
      (value "WS2812B")
      (footprint "eagle-import:WS2812B")
      (libsource (lib "eagle-import") (part "WS2812B"))
    )
    (comp (ref "L4")
      (value "WS2812B")
      (footprint "eagle-import:WS2812B")
      (libsource (lib "eagle-import") (part "WS2812B"))
    )
    (comp (ref "L5")
      (value "WS2812B")
      (footprint "eagle-import:WS2812B")
      (libsource (lib "eagle-import") (part "WS2812B"))
    )
    (comp (ref "L6")
      (value "WS2812B")
      (footprint "eagle-import:WS2812B")
      (libsource (lib "eagle-import") (part "WS2812B"))
    )
    (comp (ref "L7")
      (value "WS2812B")
      (footprint "eagle-import:WS2812B")
      (libsource (lib "eagle-import") (part "WS2812B"))
    )
    (comp (ref "L8")
      (value "WS2812B")
      (footprint "eagle-import:WS2812B")
      (libsource (lib "eagle-import") (part "WS2812B"))
    )
    (comp (ref "L9")
      (value "WS2812B")
      (footprint "eagle-import:WS2812B")
      (libsource (lib "eagle-import") (part "WS2812B"))
    )
    (comp (ref "L10")
      (value "WS2812B")
      (footprint "eagle-import:WS2812B")
      (libsource (lib "eagle-import") (part "WS2812B"))
    )
    (comp (ref "L11")
      (value "WS2812B")
      (footprint "eagle-import:WS2812B")
      (libsource (lib "eagle-import") (part "WS2812B"))
    )
    (comp (ref "L12")
      (value "WS2812B")
      (footprint "eagle-import:WS2812B")
      (libsource (lib "eagle-import") (part "WS2812B"))
    )
    (comp (ref "L13")
      (value "WS2812B")
      (footprint "eagle-import:WS2812B")
      (libsource (lib "eagle-import") (part "WS2812B"))
    )
    (comp (ref "L14")
      (value "WS2812B")
      (footprint "eagle-import:WS2812B")
      (libsource (lib "eagle-import") (part "WS2812B"))
    )
    (comp (ref "L15")
      (value "WS2812B")
      (footprint "eagle-import:WS2812B")
      (libsource (lib "eagle-import") (part "WS2812B"))
    )
    (comp (ref "L16")
      (value "WS2812B")
      (footprint "eagle-import:WS2812B")
      (libsource (lib "eagle-import") (part "WS2812B"))
    )
    (comp (ref "L17")
      (value "WS2812B")
      (footprint "eagle-import:WS2812B")
      (libsource (lib "eagle-import") (part "WS2812B"))
    )
    (comp (ref "L18")
      (value "WS2812B")
      (footprint "eagle-import:WS2812B")
      (libsource (lib "eagle-import") (part "WS2812B"))
    )
    (comp (ref "L19")
      (value "WS2812B")
      (footprint "eagle-import:WS2812B")
      (libsource (lib "eagle-import") (part "WS2812B"))
    )
    (comp (ref "L20")
      (value "WS2812B")
      (footprint "eagle-import:WS2812B")
      (libsource (lib "eagle-import") (part "WS2812B"))
    )
    (comp (ref "L21")
      (value "WS2812B")
      (footprint "eagle-import:WS2812B")
      (libsource (lib "eagle-import") (part "WS2812B"))
    )
    (comp (ref "L22")
      (value "WS2812B")
      (footprint "eagle-import:WS2812B")
      (libsource (lib "eagle-import") (part "WS2812B"))
    )
    (comp (ref "L23")
      (value "WS2812B")
      (footprint "eagle-import:WS2812B")
      (libsource (lib "eagle-import") (part "WS2812B"))
    )
    (comp (ref "L24")
      (value "WS2812B")
      (footprint "eagle-import:WS2812B")
      (libsource (lib "eagle-import") (part "WS2812B"))
    )
    (comp (ref "L25")
      (value "WS2812B")
      (footprint "eagle-import:WS2812B")
      (libsource (lib "eagle-import") (part "WS2812B"))
    )
    (comp (ref "L26")
      (value "WS2812B")
      (footprint "eagle-import:WS2812B")
      (libsource (lib "eagle-import") (part "WS2812B"))
    )
    (comp (ref "L27")
      (value "WS2812B")
      (footprint "eagle-import:WS2812B")
      (libsource (lib "eagle-import") (part "WS2812B"))
    )
    (comp (ref "L28")
      (value "WS2812B")
      (footprint "eagle-import:WS2812B")
      (libsource (lib "eagle-import") (part "WS2812B"))
    )
    (comp (ref "L29")
      (value "WS2812B")
      (footprint "eagle-import:WS2812B")
      (libsource (lib "eagle-import") (part "WS2812B"))
    )
    (comp (ref "L30")
      (value "WS2812B")
      (footprint "eagle-import:WS2812B")
      (libsource (lib "eagle-import") (part "WS2812B"))
    )
    (comp (ref "L31")
      (value "WS2812B")
      (footprint "eagle-import:WS2812B")
      (libsource (lib "eagle-import") (part "WS2812B"))
    )
    (comp (ref "L32")
      (value "WS2812B")
      (footprint "eagle-import:WS2812B")
      (libsource (lib "eagle-import") (part "WS2812B"))
    )
    (comp (ref "L33")
      (value "WS2812B")
      (footprint "eagle-import:WS2812B")
      (libsource (lib "eagle-import") (part "WS2812B"))
    )
    (comp (ref "L34")
      (value "WS2812B")
      (footprint "eagle-import:WS2812B")
      (libsource (lib "eagle-import") (part "WS2812B"))
    )
    (comp (ref "L35")
      (value "WS2812B")
      (footprint "eagle-import:WS2812B")
      (libsource (lib "eagle-import") (part "WS2812B"))
    )
    (comp (ref "L36")
      (value "WS2812B")
      (footprint "eagle-import:WS2812B")
      (libsource (lib "eagle-import") (part "WS2812B"))
    )
    (comp (ref "L37")
      (value "WS2812B")
      (footprint "eagle-import:WS2812B")
      (libsource (lib "eagle-import") (part "WS2812B"))
    )
    (comp (ref "L38")
      (value "WS2812B")
      (footprint "eagle-import:WS2812B")
      (libsource (lib "eagle-import") (part "WS2812B"))
    )
    (comp (ref "L39")
      (value "WS2812B")
      (footprint "eagle-import:WS2812B")
      (libsource (lib "eagle-import") (part "WS2812B"))
    )
    (comp (ref "L40")
      (value "WS2812B")
      (footprint "eagle-import:WS2812B")
      (libsource (lib "eagle-import") (part "WS2812B"))
    )
    (comp (ref "L41")
      (value "WS2812B")
      (footprint "eagle-import:WS2812B")
      (libsource (lib "eagle-import") (part "WS2812B"))
    )
    (comp (ref "L42")
      (value "WS2812B")
      (footprint "eagle-import:WS2812B")
      (libsource (lib "eagle-import") (part "WS2812B"))
    )
    (comp (ref "L43")
      (value "WS2812B")
      (footprint "eagle-import:WS2812B")
      (libsource (lib "eagle-import") (part "WS2812B"))
    )
    (comp (ref "L44")
      (value "WS2812B")
      (footprint "eagle-import:WS2812B")
      (libsource (lib "eagle-import") (part "WS2812B"))
    )
    (comp (ref "L45")
      (value "WS2812B")
      (footprint "eagle-import:WS2812B")
      (libsource (lib "eagle-import") (part "WS2812B"))
    )
    (comp (ref "L46")
      (value "WS2812B")
      (footprint "eagle-import:WS2812B")
      (libsource (lib "eagle-import") (part "WS2812B"))
    )
    (comp (ref "L47")
      (value "WS2812B")
      (footprint "eagle-import:WS2812B")
      (libsource (lib "eagle-import") (part "WS2812B"))
    )
    (comp (ref "L48")
      (value "WS2812B")
      (footprint "eagle-import:WS2812B")
      (libsource (lib "eagle-import") (part "WS2812B"))
    )
    (comp (ref "L49")
      (value "WS2812B")
      (footprint "eagle-import:WS2812B")
      (libsource (lib "eagle-import") (part "WS2812B"))
    )
    (comp (ref "L50")
      (value "WS2812B")
      (footprint "eagle-import:WS2812B")
      (libsource (lib "eagle-import") (part "WS2812B"))
    )
    (comp (ref "L51")
      (value "WS2812B")
      (footprint "eagle-import:WS2812B")
      (libsource (lib "eagle-import") (part "WS2812B"))
    )
    (comp (ref "L52")
      (value "WS2812B")
      (footprint "eagle-import:WS2812B")
      (libsource (lib "eagle-import") (part "WS2812B"))
    )
    (comp (ref "L53")
      (value "WS2812B")
      (footprint "eagle-import:WS2812B")
      (libsource (lib "eagle-import") (part "WS2812B"))
    )
    (comp (ref "L54")
      (value "WS2812B")
      (footprint "eagle-import:WS2812B")
      (libsource (lib "eagle-import") (part "WS2812B"))
    )
    (comp (ref "L55")
      (value "WS2812B")
      (footprint "eagle-import:WS2812B")
      (libsource (lib "eagle-import") (part "WS2812B"))
    )
    (comp (ref "L56")
      (value "WS2812B")
      (footprint "eagle-import:WS2812B")
      (libsource (lib "eagle-import") (part "WS2812B"))
    )
    (comp (ref "L57")
      (value "WS2812B")
      (footprint "eagle-import:WS2812B")
      (libsource (lib "eagle-import") (part "WS2812B"))
    )
    (comp (ref "L58")
      (value "WS2812B")
      (footprint "eagle-import:WS2812B")
      (libsource (lib "eagle-import") (part "WS2812B"))
    )
    (comp (ref "L59")
      (value "WS2812B")
      (footprint "eagle-import:WS2812B")
      (libsource (lib "eagle-import") (part "WS2812B"))
    )
    (comp (ref "L60")
      (value "WS2812B")
      (footprint "eagle-import:WS2812B")
      (libsource (lib "eagle-import") (part "WS2812B"))
    )
    (comp (ref "L61")
      (value "WS2812B")
      (footprint "eagle-import:WS2812B")
      (libsource (lib "eagle-import") (part "WS2812B"))
    )
    (comp (ref "L62")
      (value "WS2812B")
      (footprint "eagle-import:WS2812B")
      (libsource (lib "eagle-import") (part "WS2812B"))
    )
    (comp (ref "L63")
      (value "WS2812B")
      (footprint "eagle-import:WS2812B")
      (libsource (lib "eagle-import") (part "WS2812B"))
    )
    (comp (ref "L64")
      (value "WS2812B")
      (footprint "eagle-import:WS2812B")
      (libsource (lib "eagle-import") (part "WS2812B"))
    )
    (comp (ref "L65")
      (value "WS2812B")
      (footprint "eagle-import:WS2812B")
      (libsource (lib "eagle-import") (part "WS2812B"))
    )
    (comp (ref "L66")
      (value "WS2812B")
      (footprint "eagle-import:WS2812B")
      (libsource (lib "eagle-import") (part "WS2812B"))
    )
    (comp (ref "L67")
      (value "WS2812B")
      (footprint "eagle-import:WS2812B")
      (libsource (lib "eagle-import") (part "WS2812B"))
    )
    (comp (ref "L68")
      (value "WS2812B")
      (footprint "eagle-import:WS2812B")
      (libsource (lib "eagle-import") (part "WS2812B"))
    )
    (comp (ref "L69")
      (value "WS2812B")
      (footprint "eagle-import:WS2812B")
      (libsource (lib "eagle-import") (part "WS2812B"))
    )
    (comp (ref "L70")
      (value "WS2812B")
      (footprint "eagle-import:WS2812B")
      (libsource (lib "eagle-import") (part "WS2812B"))
    )
    (comp (ref "L71")
      (value "WS2812B")
      (footprint "eagle-import:WS2812B")
      (libsource (lib "eagle-import") (part "WS2812B"))
    )
    (comp (ref "L72")
      (value "WS2812B")
      (footprint "eagle-import:WS2812B")
      (libsource (lib "eagle-import") (part "WS2812B"))
    )
    (comp (ref "L73")
      (value "WS2812B")
      (footprint "eagle-import:WS2812B")
      (libsource (lib "eagle-import") (part "WS2812B"))
    )
    (comp (ref "L74")
      (value "WS2812B")
      (footprint "eagle-import:WS2812B")
      (libsource (lib "eagle-import") (part "WS2812B"))
    )
    (comp (ref "L75")
      (value "WS2812B")
      (footprint "eagle-import:WS2812B")
      (libsource (lib "eagle-import") (part "WS2812B"))
    )
    (comp (ref "L76")
      (value "WS2812B")
      (footprint "eagle-import:WS2812B")
      (libsource (lib "eagle-import") (part "WS2812B"))
    )
    (comp (ref "L77")
      (value "WS2812B")
      (footprint "eagle-import:WS2812B")
      (libsource (lib "eagle-import") (part "WS2812B"))
    )
    (comp (ref "L78")
      (value "WS2812B")
      (footprint "eagle-import:WS2812B")
      (libsource (lib "eagle-import") (part "WS2812B"))
    )
    (comp (ref "L79")
      (value "WS2812B")
      (footprint "eagle-import:WS2812B")
      (libsource (lib "eagle-import") (part "WS2812B"))
    )
    (comp (ref "L80")
      (value "WS2812B")
      (footprint "eagle-import:WS2812B")
      (libsource (lib "eagle-import") (part "WS2812B"))
    )
    (comp (ref "L81")
      (value "WS2812B")
      (footprint "eagle-import:WS2812B")
      (libsource (lib "eagle-import") (part "WS2812B"))
    )
    (comp (ref "L82")
      (value "WS2812B")
      (footprint "eagle-import:WS2812B")
      (libsource (lib "eagle-import") (part "WS2812B"))
    )
    (comp (ref "L83")
      (value "WS2812B")
      (footprint "eagle-import:WS2812B")
      (libsource (lib "eagle-import") (part "WS2812B"))
    )
    (comp (ref "L84")
      (value "WS2812B")
      (footprint "eagle-import:WS2812B")
      (libsource (lib "eagle-import") (part "WS2812B"))
    )
    (comp (ref "L85")
      (value "WS2812B")
      (footprint "eagle-import:WS2812B")
      (libsource (lib "eagle-import") (part "WS2812B"))
    )
    (comp (ref "L86")
      (value "WS2812B")
      (footprint "eagle-import:WS2812B")
      (libsource (lib "eagle-import") (part "WS2812B"))
    )
    (comp (ref "L87")
      (value "WS2812B")
      (footprint "eagle-import:WS2812B")
      (libsource (lib "eagle-import") (part "WS2812B"))
    )
    (comp (ref "L88")
      (value "WS2812B")
      (footprint "eagle-import:WS2812B")
      (libsource (lib "eagle-import") (part "WS2812B"))
    )
    (comp (ref "L89")
      (value "WS2812B")
      (footprint "eagle-import:WS2812B")
      (libsource (lib "eagle-import") (part "WS2812B"))
    )
    (comp (ref "L90")
      (value "WS2812B")
      (footprint "eagle-import:WS2812B")
      (libsource (lib "eagle-import") (part "WS2812B"))
    )
    (comp (ref "L91")
      (value "WS2812B")
      (footprint "eagle-import:WS2812B")
      (libsource (lib "eagle-import") (part "WS2812B"))
    )
    (comp (ref "L92")
      (value "WS2812B")
      (footprint "eagle-import:WS2812B")
      (libsource (lib "eagle-import") (part "WS2812B"))
    )
    (comp (ref "L93")
      (value "WS2812B")
      (footprint "eagle-import:WS2812B")
      (libsource (lib "eagle-import") (part "WS2812B"))
    )
    (comp (ref "L94")
      (value "WS2812B")
      (footprint "eagle-import:WS2812B")
      (libsource (lib "eagle-import") (part "WS2812B"))
    )
    (comp (ref "L95")
      (value "WS2812B")
      (footprint "eagle-import:WS2812B")
      (libsource (lib "eagle-import") (part "WS2812B"))
    )
    (comp (ref "L96")
      (value "WS2812B")
      (footprint "eagle-import:WS2812B")
      (libsource (lib "eagle-import") (part "WS2812B"))
    )
    (comp (ref "L97")
      (value "WS2812B")
      (footprint "eagle-import:WS2812B")
      (libsource (lib "eagle-import") (part "WS2812B"))
    )
    (comp (ref "L98")
      (value "WS2812B")
      (footprint "eagle-import:WS2812B")
      (libsource (lib "eagle-import") (part "WS2812B"))
    )
    (comp (ref "L99")
      (value "WS2812B")
      (footprint "eagle-import:WS2812B")
      (libsource (lib "eagle-import") (part "WS2812B"))
    )
    (comp (ref "L100")
      (value "WS2812B")
      (footprint "eagle-import:WS2812B")
      (libsource (lib "eagle-import") (part "WS2812B"))
    )
    (comp (ref "L101")
      (value "WS2812B")
      (footprint "eagle-import:WS2812B")
      (libsource (lib "eagle-import") (part "WS2812B"))
    )
    (comp (ref "L102")
      (value "WS2812B")
      (footprint "eagle-import:WS2812B")
      (libsource (lib "eagle-import") (part "WS2812B"))
    )
    (comp (ref "L103")
      (value "WS2812B")
      (footprint "eagle-import:WS2812B")
      (libsource (lib "eagle-import") (part "WS2812B"))
    )
    (comp (ref "L104")
      (value "WS2812B")
      (footprint "eagle-import:WS2812B")
      (libsource (lib "eagle-import") (part "WS2812B"))
    )
    (comp (ref "L105")
      (value "WS2812B")
      (footprint "eagle-import:WS2812B")
      (libsource (lib "eagle-import") (part "WS2812B"))
    )
    (comp (ref "L106")
      (value "WS2812B")
      (footprint "eagle-import:WS2812B")
      (libsource (lib "eagle-import") (part "WS2812B"))
    )
    (comp (ref "L107")
      (value "WS2812B")
      (footprint "eagle-import:WS2812B")
      (libsource (lib "eagle-import") (part "WS2812B"))
    )
    (comp (ref "L108")
      (value "WS2812B")
      (footprint "eagle-import:WS2812B")
      (libsource (lib "eagle-import") (part "WS2812B"))
    )
    (comp (ref "L109")
      (value "WS2812B")
      (footprint "eagle-import:WS2812B")
      (libsource (lib "eagle-import") (part "WS2812B"))
    )
    (comp (ref "L110")
      (value "WS2812B")
      (footprint "eagle-import:WS2812B")
      (libsource (lib "eagle-import") (part "WS2812B"))
    )
    (comp (ref "L111")
      (value "WS2812B")
      (footprint "eagle-import:WS2812B")
      (libsource (lib "eagle-import") (part "WS2812B"))
    )
    (comp (ref "L112")
      (value "WS2812B")
      (footprint "eagle-import:WS2812B")
      (libsource (lib "eagle-import") (part "WS2812B"))
    )
    (comp (ref "L113")
      (value "WS2812B")
      (footprint "eagle-import:WS2812B")
      (libsource (lib "eagle-import") (part "WS2812B"))
    )
    (comp (ref "L114")
      (value "WS2812B")
      (footprint "eagle-import:WS2812B")
      (libsource (lib "eagle-import") (part "WS2812B"))
    )
    (comp (ref "L115")
      (value "WS2812B")
      (footprint "eagle-import:WS2812B")
      (libsource (lib "eagle-import") (part "WS2812B"))
    )
    (comp (ref "L116")
      (value "WS2812B")
      (footprint "eagle-import:WS2812B")
      (libsource (lib "eagle-import") (part "WS2812B"))
    )
    (comp (ref "L117")
      (value "WS2812B")
      (footprint "eagle-import:WS2812B")
      (libsource (lib "eagle-import") (part "WS2812B"))
    )
    (comp (ref "L118")
      (value "WS2812B")
      (footprint "eagle-import:WS2812B")
      (libsource (lib "eagle-import") (part "WS2812B"))
    )
    (comp (ref "L119")
      (value "WS2812B")
      (footprint "eagle-import:WS2812B")
      (libsource (lib "eagle-import") (part "WS2812B"))
    )
    (comp (ref "L120")
      (value "WS2812B")
      (footprint "eagle-import:WS2812B")
      (libsource (lib "eagle-import") (part "WS2812B"))
    )
    (comp (ref "L121")
      (value "WS2812B")
      (footprint "eagle-import:WS2812B")
      (libsource (lib "eagle-import") (part "WS2812B"))
    )
    (comp (ref "L122")
      (value "WS2812B")
      (footprint "eagle-import:WS2812B")
      (libsource (lib "eagle-import") (part "WS2812B"))
    )
    (comp (ref "L123")
      (value "WS2812B")
      (footprint "eagle-import:WS2812B")
      (libsource (lib "eagle-import") (part "WS2812B"))
    )
    (comp (ref "L124")
      (value "WS2812B")
      (footprint "eagle-import:WS2812B")
      (libsource (lib "eagle-import") (part "WS2812B"))
    )
    (comp (ref "L125")
      (value "WS2812B")
      (footprint "eagle-import:WS2812B")
      (libsource (lib "eagle-import") (part "WS2812B"))
    )
    (comp (ref "L126")
      (value "WS2812B")
      (footprint "eagle-import:WS2812B")
      (libsource (lib "eagle-import") (part "WS2812B"))
    )
    (comp (ref "L127")
      (value "WS2812B")
      (footprint "eagle-import:WS2812B")
      (libsource (lib "eagle-import") (part "WS2812B"))
    )
    (comp (ref "L128")
      (value "WS2812B")
      (footprint "eagle-import:WS2812B")
      (libsource (lib "eagle-import") (part "WS2812B"))
    )
    (comp (ref "L129")
      (value "WS2812B")
      (footprint "eagle-import:WS2812B")
      (libsource (lib "eagle-import") (part "WS2812B"))
    )
    (comp (ref "L130")
      (value "WS2812B")
      (footprint "eagle-import:WS2812B")
      (libsource (lib "eagle-import") (part "WS2812B"))
    )
    (comp (ref "L131")
      (value "WS2812B")
      (footprint "eagle-import:WS2812B")
      (libsource (lib "eagle-import") (part "WS2812B"))
    )
    (comp (ref "L132")
      (value "WS2812B")
      (footprint "eagle-import:WS2812B")
      (libsource (lib "eagle-import") (part "WS2812B"))
    )
    (comp (ref "L133")
      (value "WS2812B")
      (footprint "eagle-import:WS2812B")
      (libsource (lib "eagle-import") (part "WS2812B"))
    )
    (comp (ref "L134")
      (value "WS2812B")
      (footprint "eagle-import:WS2812B")
      (libsource (lib "eagle-import") (part "WS2812B"))
    )
    (comp (ref "L135")
      (value "WS2812B")
      (footprint "eagle-import:WS2812B")
      (libsource (lib "eagle-import") (part "WS2812B"))
    )
    (comp (ref "L136")
      (value "WS2812B")
      (footprint "eagle-import:WS2812B")
      (libsource (lib "eagle-import") (part "WS2812B"))
    )
    (comp (ref "L137")
      (value "WS2812B")
      (footprint "eagle-import:WS2812B")
      (libsource (lib "eagle-import") (part "WS2812B"))
    )
    (comp (ref "L138")
      (value "WS2812B")
      (footprint "eagle-import:WS2812B")
      (libsource (lib "eagle-import") (part "WS2812B"))
    )
    (comp (ref "L139")
      (value "WS2812B")
      (footprint "eagle-import:WS2812B")
      (libsource (lib "eagle-import") (part "WS2812B"))
    )
    (comp (ref "L140")
      (value "WS2812B")
      (footprint "eagle-import:WS2812B")
      (libsource (lib "eagle-import") (part "WS2812B"))
    )
    (comp (ref "L141")
      (value "WS2812B")
      (footprint "eagle-import:WS2812B")
      (libsource (lib "eagle-import") (part "WS2812B"))
    )
    (comp (ref "L142")
      (value "WS2812B")
      (footprint "eagle-import:WS2812B")
      (libsource (lib "eagle-import") (part "WS2812B"))
    )
    (comp (ref "L143")
      (value "WS2812B")
      (footprint "eagle-import:WS2812B")
      (libsource (lib "eagle-import") (part "WS2812B"))
    )
    (comp (ref "L144")
      (value "WS2812B")
      (footprint "eagle-import:WS2812B")
      (libsource (lib "eagle-import") (part "WS2812B"))
    )
    (comp (ref "L145")
      (value "WS2812B")
      (footprint "eagle-import:WS2812B")
      (libsource (lib "eagle-import") (part "WS2812B"))
    )
    (comp (ref "L146")
      (value "WS2812B")
      (footprint "eagle-import:WS2812B")
      (libsource (lib "eagle-import") (part "WS2812B"))
    )
    (comp (ref "L147")
      (value "WS2812B")
      (footprint "eagle-import:WS2812B")
      (libsource (lib "eagle-import") (part "WS2812B"))
    )
    (comp (ref "L148")
      (value "WS2812B")
      (footprint "eagle-import:WS2812B")
      (libsource (lib "eagle-import") (part "WS2812B"))
    )
    (comp (ref "L149")
      (value "WS2812B")
      (footprint "eagle-import:WS2812B")
      (libsource (lib "eagle-import") (part "WS2812B"))
    )
    (comp (ref "L150")
      (value "WS2812B")
      (footprint "eagle-import:WS2812B")
      (libsource (lib "eagle-import") (part "WS2812B"))
    )
    (comp (ref "L151")
      (value "WS2812B")
      (footprint "eagle-import:WS2812B")
      (libsource (lib "eagle-import") (part "WS2812B"))
    )
    (comp (ref "L152")
      (value "WS2812B")
      (footprint "eagle-import:WS2812B")
      (libsource (lib "eagle-import") (part "WS2812B"))
    )
    (comp (ref "L153")
      (value "WS2812B")
      (footprint "eagle-import:WS2812B")
      (libsource (lib "eagle-import") (part "WS2812B"))
    )
    (comp (ref "L154")
      (value "WS2812B")
      (footprint "eagle-import:WS2812B")
      (libsource (lib "eagle-import") (part "WS2812B"))
    )
    (comp (ref "L155")
      (value "WS2812B")
      (footprint "eagle-import:WS2812B")
      (libsource (lib "eagle-import") (part "WS2812B"))
    )
    (comp (ref "L156")
      (value "WS2812B")
      (footprint "eagle-import:WS2812B")
      (libsource (lib "eagle-import") (part "WS2812B"))
    )
    (comp (ref "L157")
      (value "WS2812B")
      (footprint "eagle-import:WS2812B")
      (libsource (lib "eagle-import") (part "WS2812B"))
    )
    (comp (ref "L158")
      (value "WS2812B")
      (footprint "eagle-import:WS2812B")
      (libsource (lib "eagle-import") (part "WS2812B"))
    )
    (comp (ref "L159")
      (value "WS2812B")
      (footprint "eagle-import:WS2812B")
      (libsource (lib "eagle-import") (part "WS2812B"))
    )
    (comp (ref "L160")
      (value "WS2812B")
      (footprint "eagle-import:WS2812B")
      (libsource (lib "eagle-import") (part "WS2812B"))
    )
    (comp (ref "L161")
      (value "WS2812B")
      (footprint "eagle-import:WS2812B")
      (libsource (lib "eagle-import") (part "WS2812B"))
    )
    (comp (ref "L162")
      (value "WS2812B")
      (footprint "eagle-import:WS2812B")
      (libsource (lib "eagle-import") (part "WS2812B"))
    )
    (comp (ref "L163")
      (value "WS2812B")
      (footprint "eagle-import:WS2812B")
      (libsource (lib "eagle-import") (part "WS2812B"))
    )
    (comp (ref "L164")
      (value "WS2812B")
      (footprint "eagle-import:WS2812B")
      (libsource (lib "eagle-import") (part "WS2812B"))
    )
    (comp (ref "L165")
      (value "WS2812B")
      (footprint "eagle-import:WS2812B")
      (libsource (lib "eagle-import") (part "WS2812B"))
    )
    (comp (ref "L166")
      (value "WS2812B")
      (footprint "eagle-import:WS2812B")
      (libsource (lib "eagle-import") (part "WS2812B"))
    )
    (comp (ref "L167")
      (value "WS2812B")
      (footprint "eagle-import:WS2812B")
      (libsource (lib "eagle-import") (part "WS2812B"))
    )
    (comp (ref "L168")
      (value "WS2812B")
      (footprint "eagle-import:WS2812B")
      (libsource (lib "eagle-import") (part "WS2812B"))
    )
    (comp (ref "L169")
      (value "WS2812B")
      (footprint "eagle-import:WS2812B")
      (libsource (lib "eagle-import") (part "WS2812B"))
    )
    (comp (ref "L170")
      (value "WS2812B")
      (footprint "eagle-import:WS2812B")
      (libsource (lib "eagle-import") (part "WS2812B"))
    )
    (comp (ref "L171")
      (value "WS2812B")
      (footprint "eagle-import:WS2812B")
      (libsource (lib "eagle-import") (part "WS2812B"))
    )
    (comp (ref "L172")
      (value "WS2812B")
      (footprint "eagle-import:WS2812B")
      (libsource (lib "eagle-import") (part "WS2812B"))
    )
    (comp (ref "L173")
      (value "WS2812B")
      (footprint "eagle-import:WS2812B")
      (libsource (lib "eagle-import") (part "WS2812B"))
    )
    (comp (ref "L174")
      (value "WS2812B")
      (footprint "eagle-import:WS2812B")
      (libsource (lib "eagle-import") (part "WS2812B"))
    )
    (comp (ref "L175")
      (value "WS2812B")
      (footprint "eagle-import:WS2812B")
      (libsource (lib "eagle-import") (part "WS2812B"))
    )
    (comp (ref "L176")
      (value "WS2812B")
      (footprint "eagle-import:WS2812B")
      (libsource (lib "eagle-import") (part "WS2812B"))
    )
    (comp (ref "L177")
      (value "WS2812B")
      (footprint "eagle-import:WS2812B")
      (libsource (lib "eagle-import") (part "WS2812B"))
    )
    (comp (ref "L178")
      (value "WS2812B")
      (footprint "eagle-import:WS2812B")
      (libsource (lib "eagle-import") (part "WS2812B"))
    )
    (comp (ref "L179")
      (value "WS2812B")
      (footprint "eagle-import:WS2812B")
      (libsource (lib "eagle-import") (part "WS2812B"))
    )
    (comp (ref "L180")
      (value "WS2812B")
      (footprint "eagle-import:WS2812B")
      (libsource (lib "eagle-import") (part "WS2812B"))
    )
    (comp (ref "L181")
      (value "WS2812B")
      (footprint "eagle-import:WS2812B")
      (libsource (lib "eagle-import") (part "WS2812B"))
    )
    (comp (ref "L182")
      (value "WS2812B")
      (footprint "eagle-import:WS2812B")
      (libsource (lib "eagle-import") (part "WS2812B"))
    )
    (comp (ref "L183")
      (value "WS2812B")
      (footprint "eagle-import:WS2812B")
      (libsource (lib "eagle-import") (part "WS2812B"))
    )
    (comp (ref "L184")
      (value "WS2812B")
      (footprint "eagle-import:WS2812B")
      (libsource (lib "eagle-import") (part "WS2812B"))
    )
    (comp (ref "L185")
      (value "WS2812B")
      (footprint "eagle-import:WS2812B")
      (libsource (lib "eagle-import") (part "WS2812B"))
    )
    (comp (ref "L186")
      (value "WS2812B")
      (footprint "eagle-import:WS2812B")
      (libsource (lib "eagle-import") (part "WS2812B"))
    )
    (comp (ref "L187")
      (value "WS2812B")
      (footprint "eagle-import:WS2812B")
      (libsource (lib "eagle-import") (part "WS2812B"))
    )
    (comp (ref "L188")
      (value "WS2812B")
      (footprint "eagle-import:WS2812B")
      (libsource (lib "eagle-import") (part "WS2812B"))
    )
    (comp (ref "L189")
      (value "WS2812B")
      (footprint "eagle-import:WS2812B")
      (libsource (lib "eagle-import") (part "WS2812B"))
    )
    (comp (ref "L190")
      (value "WS2812B")
      (footprint "eagle-import:WS2812B")
      (libsource (lib "eagle-import") (part "WS2812B"))
    )
    (comp (ref "L191")
      (value "WS2812B")
      (footprint "eagle-import:WS2812B")
      (libsource (lib "eagle-import") (part "WS2812B"))
    )
    (comp (ref "L192")
      (value "WS2812B")
      (footprint "eagle-import:WS2812B")
      (libsource (lib "eagle-import") (part "WS2812B"))
    )
    (comp (ref "L193")
      (value "WS2812B")
      (footprint "eagle-import:WS2812B")
      (libsource (lib "eagle-import") (part "WS2812B"))
    )
    (comp (ref "L194")
      (value "WS2812B")
      (footprint "eagle-import:WS2812B")
      (libsource (lib "eagle-import") (part "WS2812B"))
    )
    (comp (ref "L195")
      (value "WS2812B")
      (footprint "eagle-import:WS2812B")
      (libsource (lib "eagle-import") (part "WS2812B"))
    )
    (comp (ref "L196")
      (value "WS2812B")
      (footprint "eagle-import:WS2812B")
      (libsource (lib "eagle-import") (part "WS2812B"))
    )
    (comp (ref "L197")
      (value "WS2812B")
      (footprint "eagle-import:WS2812B")
      (libsource (lib "eagle-import") (part "WS2812B"))
    )
    (comp (ref "L198")
      (value "WS2812B")
      (footprint "eagle-import:WS2812B")
      (libsource (lib "eagle-import") (part "WS2812B"))
    )
    (comp (ref "L199")
      (value "WS2812B")
      (footprint "eagle-import:WS2812B")
      (libsource (lib "eagle-import") (part "WS2812B"))
    )
    (comp (ref "L200")
      (value "WS2812B")
      (footprint "eagle-import:WS2812B")
      (libsource (lib "eagle-import") (part "WS2812B"))
    )
    (comp (ref "L201")
      (value "WS2812B")
      (footprint "eagle-import:WS2812B")
      (libsource (lib "eagle-import") (part "WS2812B"))
    )
    (comp (ref "L202")
      (value "WS2812B")
      (footprint "eagle-import:WS2812B")
      (libsource (lib "eagle-import") (part "WS2812B"))
    )
    (comp (ref "L203")
      (value "WS2812B")
      (footprint "eagle-import:WS2812B")
      (libsource (lib "eagle-import") (part "WS2812B"))
    )
    (comp (ref "L204")
      (value "WS2812B")
      (footprint "eagle-import:WS2812B")
      (libsource (lib "eagle-import") (part "WS2812B"))
    )
    (comp (ref "L205")
      (value "WS2812B")
      (footprint "eagle-import:WS2812B")
      (libsource (lib "eagle-import") (part "WS2812B"))
    )
    (comp (ref "L206")
      (value "WS2812B")
      (footprint "eagle-import:WS2812B")
      (libsource (lib "eagle-import") (part "WS2812B"))
    )
    (comp (ref "L207")
      (value "WS2812B")
      (footprint "eagle-import:WS2812B")
      (libsource (lib "eagle-import") (part "WS2812B"))
    )
    (comp (ref "L208")
      (value "WS2812B")
      (footprint "eagle-import:WS2812B")
      (libsource (lib "eagle-import") (part "WS2812B"))
    )
    (comp (ref "L209")
      (value "WS2812B")
      (footprint "eagle-import:WS2812B")
      (libsource (lib "eagle-import") (part "WS2812B"))
    )
    (comp (ref "L210")
      (value "WS2812B")
      (footprint "eagle-import:WS2812B")
      (libsource (lib "eagle-import") (part "WS2812B"))
    )
    (comp (ref "L211")
      (value "WS2812B")
      (footprint "eagle-import:WS2812B")
      (libsource (lib "eagle-import") (part "WS2812B"))
    )
    (comp (ref "L212")
      (value "WS2812B")
      (footprint "eagle-import:WS2812B")
      (libsource (lib "eagle-import") (part "WS2812B"))
    )
    (comp (ref "L213")
      (value "WS2812B")
      (footprint "eagle-import:WS2812B")
      (libsource (lib "eagle-import") (part "WS2812B"))
    )
    (comp (ref "L214")
      (value "WS2812B")
      (footprint "eagle-import:WS2812B")
      (libsource (lib "eagle-import") (part "WS2812B"))
    )
    (comp (ref "L215")
      (value "WS2812B")
      (footprint "eagle-import:WS2812B")
      (libsource (lib "eagle-import") (part "WS2812B"))
    )
    (comp (ref "L216")
      (value "WS2812B")
      (footprint "eagle-import:WS2812B")
      (libsource (lib "eagle-import") (part "WS2812B"))
    )
    (comp (ref "L217")
      (value "WS2812B")
      (footprint "eagle-import:WS2812B")
      (libsource (lib "eagle-import") (part "WS2812B"))
    )
    (comp (ref "L218")
      (value "WS2812B")
      (footprint "eagle-import:WS2812B")
      (libsource (lib "eagle-import") (part "WS2812B"))
    )
    (comp (ref "L219")
      (value "WS2812B")
      (footprint "eagle-import:WS2812B")
      (libsource (lib "eagle-import") (part "WS2812B"))
    )
    (comp (ref "L220")
      (value "WS2812B")
      (footprint "eagle-import:WS2812B")
      (libsource (lib "eagle-import") (part "WS2812B"))
    )
    (comp (ref "L221")
      (value "WS2812B")
      (footprint "eagle-import:WS2812B")
      (libsource (lib "eagle-import") (part "WS2812B"))
    )
    (comp (ref "L222")
      (value "WS2812B")
      (footprint "eagle-import:WS2812B")
      (libsource (lib "eagle-import") (part "WS2812B"))
    )
    (comp (ref "L223")
      (value "WS2812B")
      (footprint "eagle-import:WS2812B")
      (libsource (lib "eagle-import") (part "WS2812B"))
    )
    (comp (ref "L224")
      (value "WS2812B")
      (footprint "eagle-import:WS2812B")
      (libsource (lib "eagle-import") (part "WS2812B"))
    )
    (comp (ref "L225")
      (value "WS2812B")
      (footprint "eagle-import:WS2812B")
      (libsource (lib "eagle-import") (part "WS2812B"))
    )
    (comp (ref "L226")
      (value "WS2812B")
      (footprint "eagle-import:WS2812B")
      (libsource (lib "eagle-import") (part "WS2812B"))
    )
    (comp (ref "L227")
      (value "WS2812B")
      (footprint "eagle-import:WS2812B")
      (libsource (lib "eagle-import") (part "WS2812B"))
    )
    (comp (ref "L228")
      (value "WS2812B")
      (footprint "eagle-import:WS2812B")
      (libsource (lib "eagle-import") (part "WS2812B"))
    )
    (comp (ref "L229")
      (value "WS2812B")
      (footprint "eagle-import:WS2812B")
      (libsource (lib "eagle-import") (part "WS2812B"))
    )
    (comp (ref "L230")
      (value "WS2812B")
      (footprint "eagle-import:WS2812B")
      (libsource (lib "eagle-import") (part "WS2812B"))
    )
    (comp (ref "L231")
      (value "WS2812B")
      (footprint "eagle-import:WS2812B")
      (libsource (lib "eagle-import") (part "WS2812B"))
    )
    (comp (ref "L232")
      (value "WS2812B")
      (footprint "eagle-import:WS2812B")
      (libsource (lib "eagle-import") (part "WS2812B"))
    )
    (comp (ref "L233")
      (value "WS2812B")
      (footprint "eagle-import:WS2812B")
      (libsource (lib "eagle-import") (part "WS2812B"))
    )
    (comp (ref "L234")
      (value "WS2812B")
      (footprint "eagle-import:WS2812B")
      (libsource (lib "eagle-import") (part "WS2812B"))
    )
    (comp (ref "L235")
      (value "WS2812B")
      (footprint "eagle-import:WS2812B")
      (libsource (lib "eagle-import") (part "WS2812B"))
    )
    (comp (ref "L236")
      (value "WS2812B")
      (footprint "eagle-import:WS2812B")
      (libsource (lib "eagle-import") (part "WS2812B"))
    )
    (comp (ref "L237")
      (value "WS2812B")
      (footprint "eagle-import:WS2812B")
      (libsource (lib "eagle-import") (part "WS2812B"))
    )
    (comp (ref "L238")
      (value "WS2812B")
      (footprint "eagle-import:WS2812B")
      (libsource (lib "eagle-import") (part "WS2812B"))
    )
    (comp (ref "L239")
      (value "WS2812B")
      (footprint "eagle-import:WS2812B")
      (libsource (lib "eagle-import") (part "WS2812B"))
    )
    (comp (ref "L240")
      (value "WS2812B")
      (footprint "eagle-import:WS2812B")
      (libsource (lib "eagle-import") (part "WS2812B"))
    )
    (comp (ref "L241")
      (value "WS2812B")
      (footprint "eagle-import:WS2812B")
      (libsource (lib "eagle-import") (part "WS2812B"))
    )
    (comp (ref "L242")
      (value "WS2812B")
      (footprint "eagle-import:WS2812B")
      (libsource (lib "eagle-import") (part "WS2812B"))
    )
    (comp (ref "L243")
      (value "WS2812B")
      (footprint "eagle-import:WS2812B")
      (libsource (lib "eagle-import") (part "WS2812B"))
    )
    (comp (ref "L244")
      (value "WS2812B")
      (footprint "eagle-import:WS2812B")
      (libsource (lib "eagle-import") (part "WS2812B"))
    )
    (comp (ref "L245")
      (value "WS2812B")
      (footprint "eagle-import:WS2812B")
      (libsource (lib "eagle-import") (part "WS2812B"))
    )
    (comp (ref "L246")
      (value "WS2812B")
      (footprint "eagle-import:WS2812B")
      (libsource (lib "eagle-import") (part "WS2812B"))
    )
    (comp (ref "L247")
      (value "WS2812B")
      (footprint "eagle-import:WS2812B")
      (libsource (lib "eagle-import") (part "WS2812B"))
    )
    (comp (ref "L248")
      (value "WS2812B")
      (footprint "eagle-import:WS2812B")
      (libsource (lib "eagle-import") (part "WS2812B"))
    )
    (comp (ref "L249")
      (value "WS2812B")
      (footprint "eagle-import:WS2812B")
      (libsource (lib "eagle-import") (part "WS2812B"))
    )
    (comp (ref "L250")
      (value "WS2812B")
      (footprint "eagle-import:WS2812B")
      (libsource (lib "eagle-import") (part "WS2812B"))
    )
    (comp (ref "L251")
      (value "WS2812B")
      (footprint "eagle-import:WS2812B")
      (libsource (lib "eagle-import") (part "WS2812B"))
    )
    (comp (ref "L252")
      (value "WS2812B")
      (footprint "eagle-import:WS2812B")
      (libsource (lib "eagle-import") (part "WS2812B"))
    )
    (comp (ref "L253")
      (value "WS2812B")
      (footprint "eagle-import:WS2812B")
      (libsource (lib "eagle-import") (part "WS2812B"))
    )
    (comp (ref "L254")
      (value "WS2812B")
      (footprint "eagle-import:WS2812B")
      (libsource (lib "eagle-import") (part "WS2812B"))
    )
    (comp (ref "L255")
      (value "WS2812B")
      (footprint "eagle-import:WS2812B")
      (libsource (lib "eagle-import") (part "WS2812B"))
    )
    (comp (ref "L256")
      (value "WS2812B")
      (footprint "eagle-import:WS2812B")
      (libsource (lib "eagle-import") (part "WS2812B"))
    )
    (comp (ref "R2")
      (value "RESISTOR0805-RES")
      (footprint "eagle-import:0805")
      (libsource (lib "eagle-import") (part "RESISTOR0805-RES"))
    )
    (comp (ref "R3")
      (value "RESISTOR0805-RES")
      (footprint "eagle-import:0805")
      (libsource (lib "eagle-import") (part "RESISTOR0805-RES"))
    )
    (comp (ref "R4")
      (value "RESISTOR0805-RES")
      (footprint "eagle-import:0805")
      (libsource (lib "eagle-import") (part "RESISTOR0805-RES"))
    )
    (comp (ref "R5")
      (value "RESISTOR0805-RES")
      (footprint "eagle-import:0805")
      (libsource (lib "eagle-import") (part "RESISTOR0805-RES"))
    )
  )
  (nets
    (net (code "1") (name "GND") (class "Default")
      (node (ref "C1") (pin "2") (pinfunction "2_2") (pintype "passive"))
      (node (ref "C10") (pin "2") (pinfunction "2_2") (pintype "passive"))
      (node (ref "C100") (pin "2") (pinfunction "2_2") (pintype "passive"))
      (node (ref "C101") (pin "2") (pinfunction "2_2") (pintype "passive"))
      (node (ref "C102") (pin "2") (pinfunction "2_2") (pintype "passive"))
      (node (ref "C103") (pin "2") (pinfunction "2_2") (pintype "passive"))
      (node (ref "C104") (pin "2") (pinfunction "2_2") (pintype "passive"))
      (node (ref "C105") (pin "2") (pinfunction "2_2") (pintype "passive"))
      (node (ref "C106") (pin "2") (pinfunction "2_2") (pintype "passive"))
      (node (ref "C107") (pin "2") (pinfunction "2_2") (pintype "passive"))
      (node (ref "C108") (pin "2") (pinfunction "2_2") (pintype "passive"))
      (node (ref "C109") (pin "2") (pinfunction "2_2") (pintype "passive"))
      (node (ref "C11") (pin "2") (pinfunction "2_2") (pintype "passive"))
      (node (ref "C110") (pin "2") (pinfunction "2_2") (pintype "passive"))
      (node (ref "C111") (pin "2") (pinfunction "2_2") (pintype "passive"))
      (node (ref "C112") (pin "2") (pinfunction "2_2") (pintype "passive"))
      (node (ref "C113") (pin "2") (pinfunction "2_2") (pintype "passive"))
      (node (ref "C114") (pin "2") (pinfunction "2_2") (pintype "passive"))
      (node (ref "C115") (pin "2") (pinfunction "2_2") (pintype "passive"))
      (node (ref "C116") (pin "2") (pinfunction "2_2") (pintype "passive"))
      (node (ref "C117") (pin "2") (pinfunction "2_2") (pintype "passive"))
      (node (ref "C118") (pin "2") (pinfunction "2_2") (pintype "passive"))
      (node (ref "C119") (pin "2") (pinfunction "2_2") (pintype "passive"))
      (node (ref "C12") (pin "2") (pinfunction "2_2") (pintype "passive"))
      (node (ref "C120") (pin "2") (pinfunction "2_2") (pintype "passive"))
      (node (ref "C121") (pin "2") (pinfunction "2_2") (pintype "passive"))
      (node (ref "C122") (pin "2") (pinfunction "2_2") (pintype "passive"))
      (node (ref "C123") (pin "2") (pinfunction "2_2") (pintype "passive"))
      (node (ref "C124") (pin "2") (pinfunction "2_2") (pintype "passive"))
      (node (ref "C125") (pin "2") (pinfunction "2_2") (pintype "passive"))
      (node (ref "C126") (pin "2") (pinfunction "2_2") (pintype "passive"))
      (node (ref "C127") (pin "2") (pinfunction "2_2") (pintype "passive"))
      (node (ref "C128") (pin "2") (pinfunction "2_2") (pintype "passive"))
      (node (ref "C129") (pin "2") (pinfunction "2_2") (pintype "passive"))
      (node (ref "C13") (pin "2") (pinfunction "2_2") (pintype "passive"))
      (node (ref "C130") (pin "2") (pinfunction "2_2") (pintype "passive"))
      (node (ref "C131") (pin "2") (pinfunction "2_2") (pintype "passive"))
      (node (ref "C132") (pin "2") (pinfunction "2_2") (pintype "passive"))
      (node (ref "C133") (pin "2") (pinfunction "2_2") (pintype "passive"))
      (node (ref "C134") (pin "2") (pinfunction "2_2") (pintype "passive"))
      (node (ref "C135") (pin "2") (pinfunction "2_2") (pintype "passive"))
      (node (ref "C136") (pin "2") (pinfunction "2_2") (pintype "passive"))
      (node (ref "C137") (pin "2") (pinfunction "2_2") (pintype "passive"))
      (node (ref "C138") (pin "2") (pinfunction "2_2") (pintype "passive"))
      (node (ref "C139") (pin "2") (pinfunction "2_2") (pintype "passive"))
      (node (ref "C14") (pin "2") (pinfunction "2_2") (pintype "passive"))
      (node (ref "C140") (pin "2") (pinfunction "2_2") (pintype "passive"))
      (node (ref "C141") (pin "2") (pinfunction "2_2") (pintype "passive"))
      (node (ref "C142") (pin "2") (pinfunction "2_2") (pintype "passive"))
      (node (ref "C143") (pin "2") (pinfunction "2_2") (pintype "passive"))
      (node (ref "C144") (pin "2") (pinfunction "2_2") (pintype "passive"))
      (node (ref "C145") (pin "2") (pinfunction "2_2") (pintype "passive"))
      (node (ref "C146") (pin "2") (pinfunction "2_2") (pintype "passive"))
      (node (ref "C147") (pin "2") (pinfunction "2_2") (pintype "passive"))
      (node (ref "C148") (pin "2") (pinfunction "2_2") (pintype "passive"))
      (node (ref "C149") (pin "2") (pinfunction "2_2") (pintype "passive"))
      (node (ref "C15") (pin "2") (pinfunction "2_2") (pintype "passive"))
      (node (ref "C150") (pin "2") (pinfunction "2_2") (pintype "passive"))
      (node (ref "C151") (pin "2") (pinfunction "2_2") (pintype "passive"))
      (node (ref "C152") (pin "2") (pinfunction "2_2") (pintype "passive"))
      (node (ref "C153") (pin "2") (pinfunction "2_2") (pintype "passive"))
      (node (ref "C154") (pin "2") (pinfunction "2_2") (pintype "passive"))
      (node (ref "C155") (pin "2") (pinfunction "2_2") (pintype "passive"))
      (node (ref "C156") (pin "2") (pinfunction "2_2") (pintype "passive"))
      (node (ref "C157") (pin "2") (pinfunction "2_2") (pintype "passive"))
      (node (ref "C158") (pin "2") (pinfunction "2_2") (pintype "passive"))
      (node (ref "C159") (pin "2") (pinfunction "2_2") (pintype "passive"))
      (node (ref "C16") (pin "2") (pinfunction "2_2") (pintype "passive"))
      (node (ref "C160") (pin "2") (pinfunction "2_2") (pintype "passive"))
      (node (ref "C161") (pin "2") (pinfunction "2_2") (pintype "passive"))
      (node (ref "C162") (pin "2") (pinfunction "2_2") (pintype "passive"))
      (node (ref "C163") (pin "2") (pinfunction "2_2") (pintype "passive"))
      (node (ref "C164") (pin "2") (pinfunction "2_2") (pintype "passive"))
      (node (ref "C165") (pin "2") (pinfunction "2_2") (pintype "passive"))
      (node (ref "C166") (pin "2") (pinfunction "2_2") (pintype "passive"))
      (node (ref "C167") (pin "2") (pinfunction "2_2") (pintype "passive"))
      (node (ref "C168") (pin "2") (pinfunction "2_2") (pintype "passive"))
      (node (ref "C169") (pin "2") (pinfunction "2_2") (pintype "passive"))
      (node (ref "C17") (pin "2") (pinfunction "2_2") (pintype "passive"))
      (node (ref "C170") (pin "2") (pinfunction "2_2") (pintype "passive"))
      (node (ref "C171") (pin "2") (pinfunction "2_2") (pintype "passive"))
      (node (ref "C172") (pin "2") (pinfunction "2_2") (pintype "passive"))
      (node (ref "C173") (pin "2") (pinfunction "2_2") (pintype "passive"))
      (node (ref "C174") (pin "2") (pinfunction "2_2") (pintype "passive"))
      (node (ref "C175") (pin "2") (pinfunction "2_2") (pintype "passive"))
      (node (ref "C176") (pin "2") (pinfunction "2_2") (pintype "passive"))
      (node (ref "C177") (pin "2") (pinfunction "2_2") (pintype "passive"))
      (node (ref "C178") (pin "2") (pinfunction "2_2") (pintype "passive"))
      (node (ref "C179") (pin "2") (pinfunction "2_2") (pintype "passive"))
      (node (ref "C18") (pin "2") (pinfunction "2_2") (pintype "passive"))
      (node (ref "C180") (pin "2") (pinfunction "2_2") (pintype "passive"))
      (node (ref "C181") (pin "2") (pinfunction "2_2") (pintype "passive"))
      (node (ref "C182") (pin "2") (pinfunction "2_2") (pintype "passive"))
      (node (ref "C183") (pin "2") (pinfunction "2_2") (pintype "passive"))
      (node (ref "C184") (pin "2") (pinfunction "2_2") (pintype "passive"))
      (node (ref "C185") (pin "2") (pinfunction "2_2") (pintype "passive"))
      (node (ref "C186") (pin "2") (pinfunction "2_2") (pintype "passive"))
      (node (ref "C187") (pin "2") (pinfunction "2_2") (pintype "passive"))
      (node (ref "C188") (pin "2") (pinfunction "2_2") (pintype "passive"))
      (node (ref "C189") (pin "2") (pinfunction "2_2") (pintype "passive"))
      (node (ref "C19") (pin "2") (pinfunction "2_2") (pintype "passive"))
      (node (ref "C190") (pin "2") (pinfunction "2_2") (pintype "passive"))
      (node (ref "C191") (pin "2") (pinfunction "2_2") (pintype "passive"))
      (node (ref "C192") (pin "2") (pinfunction "2_2") (pintype "passive"))
      (node (ref "C193") (pin "2") (pinfunction "2_2") (pintype "passive"))
      (node (ref "C194") (pin "2") (pinfunction "2_2") (pintype "passive"))
      (node (ref "C195") (pin "2") (pinfunction "2_2") (pintype "passive"))
      (node (ref "C196") (pin "2") (pinfunction "2_2") (pintype "passive"))
      (node (ref "C197") (pin "2") (pinfunction "2_2") (pintype "passive"))
      (node (ref "C198") (pin "2") (pinfunction "2_2") (pintype "passive"))
      (node (ref "C199") (pin "2") (pinfunction "2_2") (pintype "passive"))
      (node (ref "C2") (pin "2") (pinfunction "2_2") (pintype "passive"))
      (node (ref "C20") (pin "2") (pinfunction "2_2") (pintype "passive"))
      (node (ref "C200") (pin "2") (pinfunction "2_2") (pintype "passive"))
      (node (ref "C201") (pin "2") (pinfunction "2_2") (pintype "passive"))
      (node (ref "C202") (pin "2") (pinfunction "2_2") (pintype "passive"))
      (node (ref "C203") (pin "2") (pinfunction "2_2") (pintype "passive"))
      (node (ref "C204") (pin "2") (pinfunction "2_2") (pintype "passive"))
      (node (ref "C205") (pin "2") (pinfunction "2_2") (pintype "passive"))
      (node (ref "C206") (pin "2") (pinfunction "2_2") (pintype "passive"))
      (node (ref "C207") (pin "2") (pinfunction "2_2") (pintype "passive"))
      (node (ref "C208") (pin "2") (pinfunction "2_2") (pintype "passive"))
      (node (ref "C209") (pin "2") (pinfunction "2_2") (pintype "passive"))
      (node (ref "C21") (pin "2") (pinfunction "2_2") (pintype "passive"))
      (node (ref "C210") (pin "2") (pinfunction "2_2") (pintype "passive"))
      (node (ref "C211") (pin "2") (pinfunction "2_2") (pintype "passive"))
      (node (ref "C212") (pin "2") (pinfunction "2_2") (pintype "passive"))
      (node (ref "C213") (pin "2") (pinfunction "2_2") (pintype "passive"))
      (node (ref "C214") (pin "2") (pinfunction "2_2") (pintype "passive"))
      (node (ref "C215") (pin "2") (pinfunction "2_2") (pintype "passive"))
      (node (ref "C216") (pin "2") (pinfunction "2_2") (pintype "passive"))
      (node (ref "C217") (pin "2") (pinfunction "2_2") (pintype "passive"))
      (node (ref "C218") (pin "2") (pinfunction "2_2") (pintype "passive"))
      (node (ref "C219") (pin "2") (pinfunction "2_2") (pintype "passive"))
      (node (ref "C22") (pin "2") (pinfunction "2_2") (pintype "passive"))
      (node (ref "C220") (pin "2") (pinfunction "2_2") (pintype "passive"))
      (node (ref "C221") (pin "2") (pinfunction "2_2") (pintype "passive"))
      (node (ref "C222") (pin "2") (pinfunction "2_2") (pintype "passive"))
      (node (ref "C223") (pin "2") (pinfunction "2_2") (pintype "passive"))
      (node (ref "C224") (pin "2") (pinfunction "2_2") (pintype "passive"))
      (node (ref "C225") (pin "2") (pinfunction "2_2") (pintype "passive"))
      (node (ref "C226") (pin "2") (pinfunction "2_2") (pintype "passive"))
      (node (ref "C227") (pin "2") (pinfunction "2_2") (pintype "passive"))
      (node (ref "C228") (pin "2") (pinfunction "2_2") (pintype "passive"))
      (node (ref "C229") (pin "2") (pinfunction "2_2") (pintype "passive"))
      (node (ref "C23") (pin "2") (pinfunction "2_2") (pintype "passive"))
      (node (ref "C230") (pin "2") (pinfunction "2_2") (pintype "passive"))
      (node (ref "C231") (pin "2") (pinfunction "2_2") (pintype "passive"))
      (node (ref "C232") (pin "2") (pinfunction "2_2") (pintype "passive"))
      (node (ref "C233") (pin "2") (pinfunction "2_2") (pintype "passive"))
      (node (ref "C234") (pin "2") (pinfunction "2_2") (pintype "passive"))
      (node (ref "C235") (pin "2") (pinfunction "2_2") (pintype "passive"))
      (node (ref "C236") (pin "2") (pinfunction "2_2") (pintype "passive"))
      (node (ref "C237") (pin "2") (pinfunction "2_2") (pintype "passive"))
      (node (ref "C238") (pin "2") (pinfunction "2_2") (pintype "passive"))
      (node (ref "C239") (pin "2") (pinfunction "2_2") (pintype "passive"))
      (node (ref "C24") (pin "2") (pinfunction "2_2") (pintype "passive"))
      (node (ref "C240") (pin "2") (pinfunction "2_2") (pintype "passive"))
      (node (ref "C241") (pin "2") (pinfunction "2_2") (pintype "passive"))
      (node (ref "C242") (pin "2") (pinfunction "2_2") (pintype "passive"))
      (node (ref "C243") (pin "2") (pinfunction "2_2") (pintype "passive"))
      (node (ref "C244") (pin "2") (pinfunction "2_2") (pintype "passive"))
      (node (ref "C245") (pin "2") (pinfunction "2_2") (pintype "passive"))
      (node (ref "C246") (pin "2") (pinfunction "2_2") (pintype "passive"))
      (node (ref "C247") (pin "2") (pinfunction "2_2") (pintype "passive"))
      (node (ref "C248") (pin "2") (pinfunction "2_2") (pintype "passive"))
      (node (ref "C249") (pin "2") (pinfunction "2_2") (pintype "passive"))
      (node (ref "C25") (pin "2") (pinfunction "2_2") (pintype "passive"))
      (node (ref "C250") (pin "2") (pinfunction "2_2") (pintype "passive"))
      (node (ref "C251") (pin "2") (pinfunction "2_2") (pintype "passive"))
      (node (ref "C252") (pin "2") (pinfunction "2_2") (pintype "passive"))
      (node (ref "C253") (pin "2") (pinfunction "2_2") (pintype "passive"))
      (node (ref "C254") (pin "2") (pinfunction "2_2") (pintype "passive"))
      (node (ref "C255") (pin "2") (pinfunction "2_2") (pintype "passive"))
      (node (ref "C256") (pin "2") (pinfunction "2_2") (pintype "passive"))
      (node (ref "C26") (pin "2") (pinfunction "2_2") (pintype "passive"))
      (node (ref "C27") (pin "2") (pinfunction "2_2") (pintype "passive"))
      (node (ref "C28") (pin "2") (pinfunction "2_2") (pintype "passive"))
      (node (ref "C29") (pin "2") (pinfunction "2_2") (pintype "passive"))
      (node (ref "C3") (pin "2") (pinfunction "2_2") (pintype "passive"))
      (node (ref "C30") (pin "2") (pinfunction "2_2") (pintype "passive"))
      (node (ref "C31") (pin "2") (pinfunction "2_2") (pintype "passive"))
      (node (ref "C32") (pin "2") (pinfunction "2_2") (pintype "passive"))
      (node (ref "C33") (pin "2") (pinfunction "2_2") (pintype "passive"))
      (node (ref "C34") (pin "2") (pinfunction "2_2") (pintype "passive"))
      (node (ref "C35") (pin "2") (pinfunction "2_2") (pintype "passive"))
      (node (ref "C36") (pin "2") (pinfunction "2_2") (pintype "passive"))
      (node (ref "C37") (pin "2") (pinfunction "2_2") (pintype "passive"))
      (node (ref "C38") (pin "2") (pinfunction "2_2") (pintype "passive"))
      (node (ref "C39") (pin "2") (pinfunction "2_2") (pintype "passive"))
      (node (ref "C4") (pin "2") (pinfunction "2_2") (pintype "passive"))
      (node (ref "C40") (pin "2") (pinfunction "2_2") (pintype "passive"))
      (node (ref "C41") (pin "2") (pinfunction "2_2") (pintype "passive"))
      (node (ref "C42") (pin "2") (pinfunction "2_2") (pintype "passive"))
      (node (ref "C43") (pin "2") (pinfunction "2_2") (pintype "passive"))
      (node (ref "C44") (pin "2") (pinfunction "2_2") (pintype "passive"))
      (node (ref "C45") (pin "2") (pinfunction "2_2") (pintype "passive"))
      (node (ref "C46") (pin "2") (pinfunction "2_2") (pintype "passive"))
      (node (ref "C47") (pin "2") (pinfunction "2_2") (pintype "passive"))
      (node (ref "C48") (pin "2") (pinfunction "2_2") (pintype "passive"))
      (node (ref "C49") (pin "2") (pinfunction "2_2") (pintype "passive"))
      (node (ref "C5") (pin "2") (pinfunction "2_2") (pintype "passive"))
      (node (ref "C50") (pin "2") (pinfunction "2_2") (pintype "passive"))
      (node (ref "C51") (pin "2") (pinfunction "2_2") (pintype "passive"))
      (node (ref "C52") (pin "2") (pinfunction "2_2") (pintype "passive"))
      (node (ref "C53") (pin "2") (pinfunction "2_2") (pintype "passive"))
      (node (ref "C54") (pin "2") (pinfunction "2_2") (pintype "passive"))
      (node (ref "C55") (pin "2") (pinfunction "2_2") (pintype "passive"))
      (node (ref "C56") (pin "2") (pinfunction "2_2") (pintype "passive"))
      (node (ref "C57") (pin "2") (pinfunction "2_2") (pintype "passive"))
      (node (ref "C58") (pin "2") (pinfunction "2_2") (pintype "passive"))
      (node (ref "C59") (pin "2") (pinfunction "2_2") (pintype "passive"))
      (node (ref "C6") (pin "2") (pinfunction "2_2") (pintype "passive"))
      (node (ref "C60") (pin "2") (pinfunction "2_2") (pintype "passive"))
      (node (ref "C61") (pin "2") (pinfunction "2_2") (pintype "passive"))
      (node (ref "C62") (pin "2") (pinfunction "2_2") (pintype "passive"))
      (node (ref "C63") (pin "2") (pinfunction "2_2") (pintype "passive"))
      (node (ref "C64") (pin "2") (pinfunction "2_2") (pintype "passive"))
      (node (ref "C65") (pin "2") (pinfunction "2_2") (pintype "passive"))
      (node (ref "C66") (pin "2") (pinfunction "2_2") (pintype "passive"))
      (node (ref "C67") (pin "2") (pinfunction "2_2") (pintype "passive"))
      (node (ref "C68") (pin "2") (pinfunction "2_2") (pintype "passive"))
      (node (ref "C69") (pin "2") (pinfunction "2_2") (pintype "passive"))
      (node (ref "C7") (pin "2") (pinfunction "2_2") (pintype "passive"))
      (node (ref "C70") (pin "2") (pinfunction "2_2") (pintype "passive"))
      (node (ref "C71") (pin "2") (pinfunction "2_2") (pintype "passive"))
      (node (ref "C72") (pin "2") (pinfunction "2_2") (pintype "passive"))
      (node (ref "C73") (pin "2") (pinfunction "2_2") (pintype "passive"))
      (node (ref "C74") (pin "2") (pinfunction "2_2") (pintype "passive"))
      (node (ref "C75") (pin "2") (pinfunction "2_2") (pintype "passive"))
      (node (ref "C76") (pin "2") (pinfunction "2_2") (pintype "passive"))
      (node (ref "C77") (pin "2") (pinfunction "2_2") (pintype "passive"))
      (node (ref "C78") (pin "2") (pinfunction "2_2") (pintype "passive"))
      (node (ref "C79") (pin "2") (pinfunction "2_2") (pintype "passive"))
      (node (ref "C8") (pin "2") (pinfunction "2_2") (pintype "passive"))
      (node (ref "C80") (pin "2") (pinfunction "2_2") (pintype "passive"))
      (node (ref "C81") (pin "2") (pinfunction "2_2") (pintype "passive"))
      (node (ref "C82") (pin "2") (pinfunction "2_2") (pintype "passive"))
      (node (ref "C83") (pin "2") (pinfunction "2_2") (pintype "passive"))
      (node (ref "C84") (pin "2") (pinfunction "2_2") (pintype "passive"))
      (node (ref "C85") (pin "2") (pinfunction "2_2") (pintype "passive"))
      (node (ref "C86") (pin "2") (pinfunction "2_2") (pintype "passive"))
      (node (ref "C87") (pin "2") (pinfunction "2_2") (pintype "passive"))
      (node (ref "C88") (pin "2") (pinfunction "2_2") (pintype "passive"))
      (node (ref "C89") (pin "2") (pinfunction "2_2") (pintype "passive"))
      (node (ref "C9") (pin "2") (pinfunction "2_2") (pintype "passive"))
      (node (ref "C90") (pin "2") (pinfunction "2_2") (pintype "passive"))
      (node (ref "C91") (pin "2") (pinfunction "2_2") (pintype "passive"))
      (node (ref "C92") (pin "2") (pinfunction "2_2") (pintype "passive"))
      (node (ref "C93") (pin "2") (pinfunction "2_2") (pintype "passive"))
      (node (ref "C94") (pin "2") (pinfunction "2_2") (pintype "passive"))
      (node (ref "C95") (pin "2") (pinfunction "2_2") (pintype "passive"))
      (node (ref "C96") (pin "2") (pinfunction "2_2") (pintype "passive"))
      (node (ref "C97") (pin "2") (pinfunction "2_2") (pintype "passive"))
      (node (ref "C98") (pin "2") (pinfunction "2_2") (pintype "passive"))
      (node (ref "C99") (pin "2") (pinfunction "2_2") (pintype "passive"))
      (node (ref "JP1") (pin "2") (pinfunction "2_2") (pintype "passive"))
      (node (ref "L1") (pin "3-GND") (pinfunction "GND_3-GND") (pintype "bidirectional"))
      (node (ref "L10") (pin "3-GND") (pinfunction "GND_3-GND") (pintype "bidirectional"))
      (node (ref "L100") (pin "3-GND") (pinfunction "GND_3-GND") (pintype "bidirectional"))
      (node (ref "L101") (pin "3-GND") (pinfunction "GND_3-GND") (pintype "bidirectional"))
      (node (ref "L102") (pin "3-GND") (pinfunction "GND_3-GND") (pintype "bidirectional"))
      (node (ref "L103") (pin "3-GND") (pinfunction "GND_3-GND") (pintype "bidirectional"))
      (node (ref "L104") (pin "3-GND") (pinfunction "GND_3-GND") (pintype "bidirectional"))
      (node (ref "L105") (pin "3-GND") (pinfunction "GND_3-GND") (pintype "bidirectional"))
      (node (ref "L106") (pin "3-GND") (pinfunction "GND_3-GND") (pintype "bidirectional"))
      (node (ref "L107") (pin "3-GND") (pinfunction "GND_3-GND") (pintype "bidirectional"))
      (node (ref "L108") (pin "3-GND") (pinfunction "GND_3-GND") (pintype "bidirectional"))
      (node (ref "L109") (pin "3-GND") (pinfunction "GND_3-GND") (pintype "bidirectional"))
      (node (ref "L11") (pin "3-GND") (pinfunction "GND_3-GND") (pintype "bidirectional"))
      (node (ref "L110") (pin "3-GND") (pinfunction "GND_3-GND") (pintype "bidirectional"))
      (node (ref "L111") (pin "3-GND") (pinfunction "GND_3-GND") (pintype "bidirectional"))
      (node (ref "L112") (pin "3-GND") (pinfunction "GND_3-GND") (pintype "bidirectional"))
      (node (ref "L113") (pin "3-GND") (pinfunction "GND_3-GND") (pintype "bidirectional"))
      (node (ref "L114") (pin "3-GND") (pinfunction "GND_3-GND") (pintype "bidirectional"))
      (node (ref "L115") (pin "3-GND") (pinfunction "GND_3-GND") (pintype "bidirectional"))
      (node (ref "L116") (pin "3-GND") (pinfunction "GND_3-GND") (pintype "bidirectional"))
      (node (ref "L117") (pin "3-GND") (pinfunction "GND_3-GND") (pintype "bidirectional"))
      (node (ref "L118") (pin "3-GND") (pinfunction "GND_3-GND") (pintype "bidirectional"))
      (node (ref "L119") (pin "3-GND") (pinfunction "GND_3-GND") (pintype "bidirectional"))
      (node (ref "L12") (pin "3-GND") (pinfunction "GND_3-GND") (pintype "bidirectional"))
      (node (ref "L120") (pin "3-GND") (pinfunction "GND_3-GND") (pintype "bidirectional"))
      (node (ref "L121") (pin "3-GND") (pinfunction "GND_3-GND") (pintype "bidirectional"))
      (node (ref "L122") (pin "3-GND") (pinfunction "GND_3-GND") (pintype "bidirectional"))
      (node (ref "L123") (pin "3-GND") (pinfunction "GND_3-GND") (pintype "bidirectional"))
      (node (ref "L124") (pin "3-GND") (pinfunction "GND_3-GND") (pintype "bidirectional"))
      (node (ref "L125") (pin "3-GND") (pinfunction "GND_3-GND") (pintype "bidirectional"))
      (node (ref "L126") (pin "3-GND") (pinfunction "GND_3-GND") (pintype "bidirectional"))
      (node (ref "L127") (pin "3-GND") (pinfunction "GND_3-GND") (pintype "bidirectional"))
      (node (ref "L128") (pin "3-GND") (pinfunction "GND_3-GND") (pintype "bidirectional"))
      (node (ref "L129") (pin "3-GND") (pinfunction "GND_3-GND") (pintype "bidirectional"))
      (node (ref "L13") (pin "3-GND") (pinfunction "GND_3-GND") (pintype "bidirectional"))
      (node (ref "L130") (pin "3-GND") (pinfunction "GND_3-GND") (pintype "bidirectional"))
      (node (ref "L131") (pin "3-GND") (pinfunction "GND_3-GND") (pintype "bidirectional"))
      (node (ref "L132") (pin "3-GND") (pinfunction "GND_3-GND") (pintype "bidirectional"))
      (node (ref "L133") (pin "3-GND") (pinfunction "GND_3-GND") (pintype "bidirectional"))
      (node (ref "L134") (pin "3-GND") (pinfunction "GND_3-GND") (pintype "bidirectional"))
      (node (ref "L135") (pin "3-GND") (pinfunction "GND_3-GND") (pintype "bidirectional"))
      (node (ref "L136") (pin "3-GND") (pinfunction "GND_3-GND") (pintype "bidirectional"))
      (node (ref "L137") (pin "3-GND") (pinfunction "GND_3-GND") (pintype "bidirectional"))
      (node (ref "L138") (pin "3-GND") (pinfunction "GND_3-GND") (pintype "bidirectional"))
      (node (ref "L139") (pin "3-GND") (pinfunction "GND_3-GND") (pintype "bidirectional"))
      (node (ref "L14") (pin "3-GND") (pinfunction "GND_3-GND") (pintype "bidirectional"))
      (node (ref "L140") (pin "3-GND") (pinfunction "GND_3-GND") (pintype "bidirectional"))
      (node (ref "L141") (pin "3-GND") (pinfunction "GND_3-GND") (pintype "bidirectional"))
      (node (ref "L142") (pin "3-GND") (pinfunction "GND_3-GND") (pintype "bidirectional"))
      (node (ref "L143") (pin "3-GND") (pinfunction "GND_3-GND") (pintype "bidirectional"))
      (node (ref "L144") (pin "3-GND") (pinfunction "GND_3-GND") (pintype "bidirectional"))
      (node (ref "L145") (pin "3-GND") (pinfunction "GND_3-GND") (pintype "bidirectional"))
      (node (ref "L146") (pin "3-GND") (pinfunction "GND_3-GND") (pintype "bidirectional"))
      (node (ref "L147") (pin "3-GND") (pinfunction "GND_3-GND") (pintype "bidirectional"))
      (node (ref "L148") (pin "3-GND") (pinfunction "GND_3-GND") (pintype "bidirectional"))
      (node (ref "L149") (pin "3-GND") (pinfunction "GND_3-GND") (pintype "bidirectional"))
      (node (ref "L15") (pin "3-GND") (pinfunction "GND_3-GND") (pintype "bidirectional"))
      (node (ref "L150") (pin "3-GND") (pinfunction "GND_3-GND") (pintype "bidirectional"))
      (node (ref "L151") (pin "3-GND") (pinfunction "GND_3-GND") (pintype "bidirectional"))
      (node (ref "L152") (pin "3-GND") (pinfunction "GND_3-GND") (pintype "bidirectional"))
      (node (ref "L153") (pin "3-GND") (pinfunction "GND_3-GND") (pintype "bidirectional"))
      (node (ref "L154") (pin "3-GND") (pinfunction "GND_3-GND") (pintype "bidirectional"))
      (node (ref "L155") (pin "3-GND") (pinfunction "GND_3-GND") (pintype "bidirectional"))
      (node (ref "L156") (pin "3-GND") (pinfunction "GND_3-GND") (pintype "bidirectional"))
      (node (ref "L157") (pin "3-GND") (pinfunction "GND_3-GND") (pintype "bidirectional"))
      (node (ref "L158") (pin "3-GND") (pinfunction "GND_3-GND") (pintype "bidirectional"))
      (node (ref "L159") (pin "3-GND") (pinfunction "GND_3-GND") (pintype "bidirectional"))
      (node (ref "L16") (pin "3-GND") (pinfunction "GND_3-GND") (pintype "bidirectional"))
      (node (ref "L160") (pin "3-GND") (pinfunction "GND_3-GND") (pintype "bidirectional"))
      (node (ref "L161") (pin "3-GND") (pinfunction "GND_3-GND") (pintype "bidirectional"))
      (node (ref "L162") (pin "3-GND") (pinfunction "GND_3-GND") (pintype "bidirectional"))
      (node (ref "L163") (pin "3-GND") (pinfunction "GND_3-GND") (pintype "bidirectional"))
      (node (ref "L164") (pin "3-GND") (pinfunction "GND_3-GND") (pintype "bidirectional"))
      (node (ref "L165") (pin "3-GND") (pinfunction "GND_3-GND") (pintype "bidirectional"))
      (node (ref "L166") (pin "3-GND") (pinfunction "GND_3-GND") (pintype "bidirectional"))
      (node (ref "L167") (pin "3-GND") (pinfunction "GND_3-GND") (pintype "bidirectional"))
      (node (ref "L168") (pin "3-GND") (pinfunction "GND_3-GND") (pintype "bidirectional"))
      (node (ref "L169") (pin "3-GND") (pinfunction "GND_3-GND") (pintype "bidirectional"))
      (node (ref "L17") (pin "3-GND") (pinfunction "GND_3-GND") (pintype "bidirectional"))
      (node (ref "L170") (pin "3-GND") (pinfunction "GND_3-GND") (pintype "bidirectional"))
      (node (ref "L171") (pin "3-GND") (pinfunction "GND_3-GND") (pintype "bidirectional"))
      (node (ref "L172") (pin "3-GND") (pinfunction "GND_3-GND") (pintype "bidirectional"))
      (node (ref "L173") (pin "3-GND") (pinfunction "GND_3-GND") (pintype "bidirectional"))
      (node (ref "L174") (pin "3-GND") (pinfunction "GND_3-GND") (pintype "bidirectional"))
      (node (ref "L175") (pin "3-GND") (pinfunction "GND_3-GND") (pintype "bidirectional"))
      (node (ref "L176") (pin "3-GND") (pinfunction "GND_3-GND") (pintype "bidirectional"))
      (node (ref "L177") (pin "3-GND") (pinfunction "GND_3-GND") (pintype "bidirectional"))
      (node (ref "L178") (pin "3-GND") (pinfunction "GND_3-GND") (pintype "bidirectional"))
      (node (ref "L179") (pin "3-GND") (pinfunction "GND_3-GND") (pintype "bidirectional"))
      (node (ref "L18") (pin "3-GND") (pinfunction "GND_3-GND") (pintype "bidirectional"))
      (node (ref "L180") (pin "3-GND") (pinfunction "GND_3-GND") (pintype "bidirectional"))
      (node (ref "L181") (pin "3-GND") (pinfunction "GND_3-GND") (pintype "bidirectional"))
      (node (ref "L182") (pin "3-GND") (pinfunction "GND_3-GND") (pintype "bidirectional"))
      (node (ref "L183") (pin "3-GND") (pinfunction "GND_3-GND") (pintype "bidirectional"))
      (node (ref "L184") (pin "3-GND") (pinfunction "GND_3-GND") (pintype "bidirectional"))
      (node (ref "L185") (pin "3-GND") (pinfunction "GND_3-GND") (pintype "bidirectional"))
      (node (ref "L186") (pin "3-GND") (pinfunction "GND_3-GND") (pintype "bidirectional"))
      (node (ref "L187") (pin "3-GND") (pinfunction "GND_3-GND") (pintype "bidirectional"))
      (node (ref "L188") (pin "3-GND") (pinfunction "GND_3-GND") (pintype "bidirectional"))
      (node (ref "L189") (pin "3-GND") (pinfunction "GND_3-GND") (pintype "bidirectional"))
      (node (ref "L19") (pin "3-GND") (pinfunction "GND_3-GND") (pintype "bidirectional"))
      (node (ref "L190") (pin "3-GND") (pinfunction "GND_3-GND") (pintype "bidirectional"))
      (node (ref "L191") (pin "3-GND") (pinfunction "GND_3-GND") (pintype "bidirectional"))
      (node (ref "L192") (pin "3-GND") (pinfunction "GND_3-GND") (pintype "bidirectional"))
      (node (ref "L193") (pin "3-GND") (pinfunction "GND_3-GND") (pintype "bidirectional"))
      (node (ref "L194") (pin "3-GND") (pinfunction "GND_3-GND") (pintype "bidirectional"))
      (node (ref "L195") (pin "3-GND") (pinfunction "GND_3-GND") (pintype "bidirectional"))
      (node (ref "L196") (pin "3-GND") (pinfunction "GND_3-GND") (pintype "bidirectional"))
      (node (ref "L197") (pin "3-GND") (pinfunction "GND_3-GND") (pintype "bidirectional"))
      (node (ref "L198") (pin "3-GND") (pinfunction "GND_3-GND") (pintype "bidirectional"))
      (node (ref "L199") (pin "3-GND") (pinfunction "GND_3-GND") (pintype "bidirectional"))
      (node (ref "L2") (pin "3-GND") (pinfunction "GND_3-GND") (pintype "bidirectional"))
      (node (ref "L20") (pin "3-GND") (pinfunction "GND_3-GND") (pintype "bidirectional"))
      (node (ref "L200") (pin "3-GND") (pinfunction "GND_3-GND") (pintype "bidirectional"))
      (node (ref "L201") (pin "3-GND") (pinfunction "GND_3-GND") (pintype "bidirectional"))
      (node (ref "L202") (pin "3-GND") (pinfunction "GND_3-GND") (pintype "bidirectional"))
      (node (ref "L203") (pin "3-GND") (pinfunction "GND_3-GND") (pintype "bidirectional"))
      (node (ref "L204") (pin "3-GND") (pinfunction "GND_3-GND") (pintype "bidirectional"))
      (node (ref "L205") (pin "3-GND") (pinfunction "GND_3-GND") (pintype "bidirectional"))
      (node (ref "L206") (pin "3-GND") (pinfunction "GND_3-GND") (pintype "bidirectional"))
      (node (ref "L207") (pin "3-GND") (pinfunction "GND_3-GND") (pintype "bidirectional"))
      (node (ref "L208") (pin "3-GND") (pinfunction "GND_3-GND") (pintype "bidirectional"))
      (node (ref "L209") (pin "3-GND") (pinfunction "GND_3-GND") (pintype "bidirectional"))
      (node (ref "L21") (pin "3-GND") (pinfunction "GND_3-GND") (pintype "bidirectional"))
      (node (ref "L210") (pin "3-GND") (pinfunction "GND_3-GND") (pintype "bidirectional"))
      (node (ref "L211") (pin "3-GND") (pinfunction "GND_3-GND") (pintype "bidirectional"))
      (node (ref "L212") (pin "3-GND") (pinfunction "GND_3-GND") (pintype "bidirectional"))
      (node (ref "L213") (pin "3-GND") (pinfunction "GND_3-GND") (pintype "bidirectional"))
      (node (ref "L214") (pin "3-GND") (pinfunction "GND_3-GND") (pintype "bidirectional"))
      (node (ref "L215") (pin "3-GND") (pinfunction "GND_3-GND") (pintype "bidirectional"))
      (node (ref "L216") (pin "3-GND") (pinfunction "GND_3-GND") (pintype "bidirectional"))
      (node (ref "L217") (pin "3-GND") (pinfunction "GND_3-GND") (pintype "bidirectional"))
      (node (ref "L218") (pin "3-GND") (pinfunction "GND_3-GND") (pintype "bidirectional"))
      (node (ref "L219") (pin "3-GND") (pinfunction "GND_3-GND") (pintype "bidirectional"))
      (node (ref "L22") (pin "3-GND") (pinfunction "GND_3-GND") (pintype "bidirectional"))
      (node (ref "L220") (pin "3-GND") (pinfunction "GND_3-GND") (pintype "bidirectional"))
      (node (ref "L221") (pin "3-GND") (pinfunction "GND_3-GND") (pintype "bidirectional"))
      (node (ref "L222") (pin "3-GND") (pinfunction "GND_3-GND") (pintype "bidirectional"))
      (node (ref "L223") (pin "3-GND") (pinfunction "GND_3-GND") (pintype "bidirectional"))
      (node (ref "L224") (pin "3-GND") (pinfunction "GND_3-GND") (pintype "bidirectional"))
      (node (ref "L225") (pin "3-GND") (pinfunction "GND_3-GND") (pintype "bidirectional"))
      (node (ref "L226") (pin "3-GND") (pinfunction "GND_3-GND") (pintype "bidirectional"))
      (node (ref "L227") (pin "3-GND") (pinfunction "GND_3-GND") (pintype "bidirectional"))
      (node (ref "L228") (pin "3-GND") (pinfunction "GND_3-GND") (pintype "bidirectional"))
      (node (ref "L229") (pin "3-GND") (pinfunction "GND_3-GND") (pintype "bidirectional"))
      (node (ref "L23") (pin "3-GND") (pinfunction "GND_3-GND") (pintype "bidirectional"))
      (node (ref "L230") (pin "3-GND") (pinfunction "GND_3-GND") (pintype "bidirectional"))
      (node (ref "L231") (pin "3-GND") (pinfunction "GND_3-GND") (pintype "bidirectional"))
      (node (ref "L232") (pin "3-GND") (pinfunction "GND_3-GND") (pintype "bidirectional"))
      (node (ref "L233") (pin "3-GND") (pinfunction "GND_3-GND") (pintype "bidirectional"))
      (node (ref "L234") (pin "3-GND") (pinfunction "GND_3-GND") (pintype "bidirectional"))
      (node (ref "L235") (pin "3-GND") (pinfunction "GND_3-GND") (pintype "bidirectional"))
      (node (ref "L236") (pin "3-GND") (pinfunction "GND_3-GND") (pintype "bidirectional"))
      (node (ref "L237") (pin "3-GND") (pinfunction "GND_3-GND") (pintype "bidirectional"))
      (node (ref "L238") (pin "3-GND") (pinfunction "GND_3-GND") (pintype "bidirectional"))
      (node (ref "L239") (pin "3-GND") (pinfunction "GND_3-GND") (pintype "bidirectional"))
      (node (ref "L24") (pin "3-GND") (pinfunction "GND_3-GND") (pintype "bidirectional"))
      (node (ref "L240") (pin "3-GND") (pinfunction "GND_3-GND") (pintype "bidirectional"))
      (node (ref "L241") (pin "3-GND") (pinfunction "GND_3-GND") (pintype "bidirectional"))
      (node (ref "L242") (pin "3-GND") (pinfunction "GND_3-GND") (pintype "bidirectional"))
      (node (ref "L243") (pin "3-GND") (pinfunction "GND_3-GND") (pintype "bidirectional"))
      (node (ref "L244") (pin "3-GND") (pinfunction "GND_3-GND") (pintype "bidirectional"))
      (node (ref "L245") (pin "3-GND") (pinfunction "GND_3-GND") (pintype "bidirectional"))
      (node (ref "L246") (pin "3-GND") (pinfunction "GND_3-GND") (pintype "bidirectional"))
      (node (ref "L247") (pin "3-GND") (pinfunction "GND_3-GND") (pintype "bidirectional"))
      (node (ref "L248") (pin "3-GND") (pinfunction "GND_3-GND") (pintype "bidirectional"))
      (node (ref "L249") (pin "3-GND") (pinfunction "GND_3-GND") (pintype "bidirectional"))
      (node (ref "L25") (pin "3-GND") (pinfunction "GND_3-GND") (pintype "bidirectional"))
      (node (ref "L250") (pin "3-GND") (pinfunction "GND_3-GND") (pintype "bidirectional"))
      (node (ref "L251") (pin "3-GND") (pinfunction "GND_3-GND") (pintype "bidirectional"))
      (node (ref "L252") (pin "3-GND") (pinfunction "GND_3-GND") (pintype "bidirectional"))
      (node (ref "L253") (pin "3-GND") (pinfunction "GND_3-GND") (pintype "bidirectional"))
      (node (ref "L254") (pin "3-GND") (pinfunction "GND_3-GND") (pintype "bidirectional"))
      (node (ref "L255") (pin "3-GND") (pinfunction "GND_3-GND") (pintype "bidirectional"))
      (node (ref "L256") (pin "3-GND") (pinfunction "GND_3-GND") (pintype "bidirectional"))
      (node (ref "L26") (pin "3-GND") (pinfunction "GND_3-GND") (pintype "bidirectional"))
      (node (ref "L27") (pin "3-GND") (pinfunction "GND_3-GND") (pintype "bidirectional"))
      (node (ref "L28") (pin "3-GND") (pinfunction "GND_3-GND") (pintype "bidirectional"))
      (node (ref "L29") (pin "3-GND") (pinfunction "GND_3-GND") (pintype "bidirectional"))
      (node (ref "L3") (pin "3-GND") (pinfunction "GND_3-GND") (pintype "bidirectional"))
      (node (ref "L30") (pin "3-GND") (pinfunction "GND_3-GND") (pintype "bidirectional"))
      (node (ref "L31") (pin "3-GND") (pinfunction "GND_3-GND") (pintype "bidirectional"))
      (node (ref "L32") (pin "3-GND") (pinfunction "GND_3-GND") (pintype "bidirectional"))
      (node (ref "L33") (pin "3-GND") (pinfunction "GND_3-GND") (pintype "bidirectional"))
      (node (ref "L34") (pin "3-GND") (pinfunction "GND_3-GND") (pintype "bidirectional"))
      (node (ref "L35") (pin "3-GND") (pinfunction "GND_3-GND") (pintype "bidirectional"))
      (node (ref "L36") (pin "3-GND") (pinfunction "GND_3-GND") (pintype "bidirectional"))
      (node (ref "L37") (pin "3-GND") (pinfunction "GND_3-GND") (pintype "bidirectional"))
      (node (ref "L38") (pin "3-GND") (pinfunction "GND_3-GND") (pintype "bidirectional"))
      (node (ref "L39") (pin "3-GND") (pinfunction "GND_3-GND") (pintype "bidirectional"))
      (node (ref "L4") (pin "3-GND") (pinfunction "GND_3-GND") (pintype "bidirectional"))
      (node (ref "L40") (pin "3-GND") (pinfunction "GND_3-GND") (pintype "bidirectional"))
      (node (ref "L41") (pin "3-GND") (pinfunction "GND_3-GND") (pintype "bidirectional"))
      (node (ref "L42") (pin "3-GND") (pinfunction "GND_3-GND") (pintype "bidirectional"))
      (node (ref "L43") (pin "3-GND") (pinfunction "GND_3-GND") (pintype "bidirectional"))
      (node (ref "L44") (pin "3-GND") (pinfunction "GND_3-GND") (pintype "bidirectional"))
      (node (ref "L45") (pin "3-GND") (pinfunction "GND_3-GND") (pintype "bidirectional"))
      (node (ref "L46") (pin "3-GND") (pinfunction "GND_3-GND") (pintype "bidirectional"))
      (node (ref "L47") (pin "3-GND") (pinfunction "GND_3-GND") (pintype "bidirectional"))
      (node (ref "L48") (pin "3-GND") (pinfunction "GND_3-GND") (pintype "bidirectional"))
      (node (ref "L49") (pin "3-GND") (pinfunction "GND_3-GND") (pintype "bidirectional"))
      (node (ref "L5") (pin "3-GND") (pinfunction "GND_3-GND") (pintype "bidirectional"))
      (node (ref "L50") (pin "3-GND") (pinfunction "GND_3-GND") (pintype "bidirectional"))
      (node (ref "L51") (pin "3-GND") (pinfunction "GND_3-GND") (pintype "bidirectional"))
      (node (ref "L52") (pin "3-GND") (pinfunction "GND_3-GND") (pintype "bidirectional"))
      (node (ref "L53") (pin "3-GND") (pinfunction "GND_3-GND") (pintype "bidirectional"))
      (node (ref "L54") (pin "3-GND") (pinfunction "GND_3-GND") (pintype "bidirectional"))
      (node (ref "L55") (pin "3-GND") (pinfunction "GND_3-GND") (pintype "bidirectional"))
      (node (ref "L56") (pin "3-GND") (pinfunction "GND_3-GND") (pintype "bidirectional"))
      (node (ref "L57") (pin "3-GND") (pinfunction "GND_3-GND") (pintype "bidirectional"))
      (node (ref "L58") (pin "3-GND") (pinfunction "GND_3-GND") (pintype "bidirectional"))
      (node (ref "L59") (pin "3-GND") (pinfunction "GND_3-GND") (pintype "bidirectional"))
      (node (ref "L6") (pin "3-GND") (pinfunction "GND_3-GND") (pintype "bidirectional"))
      (node (ref "L60") (pin "3-GND") (pinfunction "GND_3-GND") (pintype "bidirectional"))
      (node (ref "L61") (pin "3-GND") (pinfunction "GND_3-GND") (pintype "bidirectional"))
      (node (ref "L62") (pin "3-GND") (pinfunction "GND_3-GND") (pintype "bidirectional"))
      (node (ref "L63") (pin "3-GND") (pinfunction "GND_3-GND") (pintype "bidirectional"))
      (node (ref "L64") (pin "3-GND") (pinfunction "GND_3-GND") (pintype "bidirectional"))
      (node (ref "L65") (pin "3-GND") (pinfunction "GND_3-GND") (pintype "bidirectional"))
      (node (ref "L66") (pin "3-GND") (pinfunction "GND_3-GND") (pintype "bidirectional"))
      (node (ref "L67") (pin "3-GND") (pinfunction "GND_3-GND") (pintype "bidirectional"))
      (node (ref "L68") (pin "3-GND") (pinfunction "GND_3-GND") (pintype "bidirectional"))
      (node (ref "L69") (pin "3-GND") (pinfunction "GND_3-GND") (pintype "bidirectional"))
      (node (ref "L7") (pin "3-GND") (pinfunction "GND_3-GND") (pintype "bidirectional"))
      (node (ref "L70") (pin "3-GND") (pinfunction "GND_3-GND") (pintype "bidirectional"))
      (node (ref "L71") (pin "3-GND") (pinfunction "GND_3-GND") (pintype "bidirectional"))
      (node (ref "L72") (pin "3-GND") (pinfunction "GND_3-GND") (pintype "bidirectional"))
      (node (ref "L73") (pin "3-GND") (pinfunction "GND_3-GND") (pintype "bidirectional"))
      (node (ref "L74") (pin "3-GND") (pinfunction "GND_3-GND") (pintype "bidirectional"))
      (node (ref "L75") (pin "3-GND") (pinfunction "GND_3-GND") (pintype "bidirectional"))
      (node (ref "L76") (pin "3-GND") (pinfunction "GND_3-GND") (pintype "bidirectional"))
      (node (ref "L77") (pin "3-GND") (pinfunction "GND_3-GND") (pintype "bidirectional"))
      (node (ref "L78") (pin "3-GND") (pinfunction "GND_3-GND") (pintype "bidirectional"))
      (node (ref "L79") (pin "3-GND") (pinfunction "GND_3-GND") (pintype "bidirectional"))
      (node (ref "L8") (pin "3-GND") (pinfunction "GND_3-GND") (pintype "bidirectional"))
      (node (ref "L80") (pin "3-GND") (pinfunction "GND_3-GND") (pintype "bidirectional"))
      (node (ref "L81") (pin "3-GND") (pinfunction "GND_3-GND") (pintype "bidirectional"))
      (node (ref "L82") (pin "3-GND") (pinfunction "GND_3-GND") (pintype "bidirectional"))
      (node (ref "L83") (pin "3-GND") (pinfunction "GND_3-GND") (pintype "bidirectional"))
      (node (ref "L84") (pin "3-GND") (pinfunction "GND_3-GND") (pintype "bidirectional"))
      (node (ref "L85") (pin "3-GND") (pinfunction "GND_3-GND") (pintype "bidirectional"))
      (node (ref "L86") (pin "3-GND") (pinfunction "GND_3-GND") (pintype "bidirectional"))
      (node (ref "L87") (pin "3-GND") (pinfunction "GND_3-GND") (pintype "bidirectional"))
      (node (ref "L88") (pin "3-GND") (pinfunction "GND_3-GND") (pintype "bidirectional"))
      (node (ref "L89") (pin "3-GND") (pinfunction "GND_3-GND") (pintype "bidirectional"))
      (node (ref "L9") (pin "3-GND") (pinfunction "GND_3-GND") (pintype "bidirectional"))
      (node (ref "L90") (pin "3-GND") (pinfunction "GND_3-GND") (pintype "bidirectional"))
      (node (ref "L91") (pin "3-GND") (pinfunction "GND_3-GND") (pintype "bidirectional"))
      (node (ref "L92") (pin "3-GND") (pinfunction "GND_3-GND") (pintype "bidirectional"))
      (node (ref "L93") (pin "3-GND") (pinfunction "GND_3-GND") (pintype "bidirectional"))
      (node (ref "L94") (pin "3-GND") (pinfunction "GND_3-GND") (pintype "bidirectional"))
      (node (ref "L95") (pin "3-GND") (pinfunction "GND_3-GND") (pintype "bidirectional"))
      (node (ref "L96") (pin "3-GND") (pinfunction "GND_3-GND") (pintype "bidirectional"))
      (node (ref "L97") (pin "3-GND") (pinfunction "GND_3-GND") (pintype "bidirectional"))
      (node (ref "L98") (pin "3-GND") (pinfunction "GND_3-GND") (pintype "bidirectional"))
      (node (ref "L99") (pin "3-GND") (pinfunction "GND_3-GND") (pintype "bidirectional"))
    )
    (net (code "2") (name "Net-(JP1-Pad3)") (class "Default")
      (node (ref "JP1") (pin "3") (pinfunction "3_3") (pintype "passive"))
      (node (ref "R4") (pin "1") (pinfunction "1_1") (pintype "passive"))
    )
    (net (code "3") (name "Net-(JP1-Pad4)") (class "Default")
      (node (ref "JP1") (pin "4") (pinfunction "4_4") (pintype "passive"))
      (node (ref "R5") (pin "1") (pinfunction "1_1") (pintype "passive"))
    )
    (net (code "4") (name "Net-(JP1-Pad5)") (class "Default")
      (node (ref "JP1") (pin "5") (pinfunction "5_5") (pintype "passive"))
      (node (ref "R3") (pin "1") (pinfunction "1_1") (pintype "passive"))
    )
    (net (code "5") (name "Net-(JP1-Pad6)") (class "Default")
      (node (ref "JP1") (pin "6") (pinfunction "6_6") (pintype "passive"))
      (node (ref "R2") (pin "1") (pinfunction "1_1") (pintype "passive"))
    )
    (net (code "6") (name "Net-(L1-DIN)") (class "Default")
      (node (ref "L1") (pin "4-DIN") (pinfunction "DIN_4-DIN") (pintype "input"))
      (node (ref "R4") (pin "2") (pinfunction "2_2") (pintype "passive"))
    )
    (net (code "7") (name "Net-(L1-DOUT)") (class "Default")
      (node (ref "L1") (pin "2-DOUT") (pinfunction "DOUT_2-DOUT") (pintype "output"))
      (node (ref "L2") (pin "4-DIN") (pinfunction "DIN_4-DIN") (pintype "input"))
    )
    (net (code "8") (name "Net-(L2-DOUT)") (class "Default")
      (node (ref "L2") (pin "2-DOUT") (pinfunction "DOUT_2-DOUT") (pintype "output"))
      (node (ref "L3") (pin "4-DIN") (pinfunction "DIN_4-DIN") (pintype "input"))
    )
    (net (code "9") (name "Net-(L3-DOUT)") (class "Default")
      (node (ref "L3") (pin "2-DOUT") (pinfunction "DOUT_2-DOUT") (pintype "output"))
      (node (ref "L4") (pin "4-DIN") (pinfunction "DIN_4-DIN") (pintype "input"))
    )
    (net (code "10") (name "Net-(L4-DOUT)") (class "Default")
      (node (ref "L4") (pin "2-DOUT") (pinfunction "DOUT_2-DOUT") (pintype "output"))
      (node (ref "L5") (pin "4-DIN") (pinfunction "DIN_4-DIN") (pintype "input"))
    )
    (net (code "11") (name "Net-(L5-DOUT)") (class "Default")
      (node (ref "L5") (pin "2-DOUT") (pinfunction "DOUT_2-DOUT") (pintype "output"))
      (node (ref "L6") (pin "4-DIN") (pinfunction "DIN_4-DIN") (pintype "input"))
    )
    (net (code "12") (name "Net-(L6-DOUT)") (class "Default")
      (node (ref "L6") (pin "2-DOUT") (pinfunction "DOUT_2-DOUT") (pintype "output"))
      (node (ref "L7") (pin "4-DIN") (pinfunction "DIN_4-DIN") (pintype "input"))
    )
    (net (code "13") (name "Net-(L7-DOUT)") (class "Default")
      (node (ref "L7") (pin "2-DOUT") (pinfunction "DOUT_2-DOUT") (pintype "output"))
      (node (ref "L8") (pin "4-DIN") (pinfunction "DIN_4-DIN") (pintype "input"))
    )
    (net (code "14") (name "Net-(L8-DOUT)") (class "Default")
      (node (ref "L8") (pin "2-DOUT") (pinfunction "DOUT_2-DOUT") (pintype "output"))
      (node (ref "L9") (pin "4-DIN") (pinfunction "DIN_4-DIN") (pintype "input"))
    )
    (net (code "15") (name "Net-(L10-DIN)") (class "Default")
      (node (ref "L10") (pin "4-DIN") (pinfunction "DIN_4-DIN") (pintype "input"))
      (node (ref "L9") (pin "2-DOUT") (pinfunction "DOUT_2-DOUT") (pintype "output"))
    )
    (net (code "16") (name "Net-(L10-DOUT)") (class "Default")
      (node (ref "L10") (pin "2-DOUT") (pinfunction "DOUT_2-DOUT") (pintype "output"))
      (node (ref "L11") (pin "4-DIN") (pinfunction "DIN_4-DIN") (pintype "input"))
    )
    (net (code "17") (name "Net-(L11-DOUT)") (class "Default")
      (node (ref "L11") (pin "2-DOUT") (pinfunction "DOUT_2-DOUT") (pintype "output"))
      (node (ref "L12") (pin "4-DIN") (pinfunction "DIN_4-DIN") (pintype "input"))
    )
    (net (code "18") (name "Net-(L12-DOUT)") (class "Default")
      (node (ref "L12") (pin "2-DOUT") (pinfunction "DOUT_2-DOUT") (pintype "output"))
      (node (ref "L13") (pin "4-DIN") (pinfunction "DIN_4-DIN") (pintype "input"))
    )
    (net (code "19") (name "Net-(L13-DOUT)") (class "Default")
      (node (ref "L13") (pin "2-DOUT") (pinfunction "DOUT_2-DOUT") (pintype "output"))
      (node (ref "L14") (pin "4-DIN") (pinfunction "DIN_4-DIN") (pintype "input"))
    )
    (net (code "20") (name "Net-(L14-DOUT)") (class "Default")
      (node (ref "L14") (pin "2-DOUT") (pinfunction "DOUT_2-DOUT") (pintype "output"))
      (node (ref "L15") (pin "4-DIN") (pinfunction "DIN_4-DIN") (pintype "input"))
    )
    (net (code "21") (name "Net-(L15-DOUT)") (class "Default")
      (node (ref "L15") (pin "2-DOUT") (pinfunction "DOUT_2-DOUT") (pintype "output"))
      (node (ref "L16") (pin "4-DIN") (pinfunction "DIN_4-DIN") (pintype "input"))
    )
    (net (code "22") (name "Net-(L16-DOUT)") (class "Default")
      (node (ref "L16") (pin "2-DOUT") (pinfunction "DOUT_2-DOUT") (pintype "output"))
      (node (ref "L17") (pin "4-DIN") (pinfunction "DIN_4-DIN") (pintype "input"))
    )
    (net (code "23") (name "Net-(L17-DOUT)") (class "Default")
      (node (ref "L17") (pin "2-DOUT") (pinfunction "DOUT_2-DOUT") (pintype "output"))
      (node (ref "L18") (pin "4-DIN") (pinfunction "DIN_4-DIN") (pintype "input"))
    )
    (net (code "24") (name "Net-(L18-DOUT)") (class "Default")
      (node (ref "L18") (pin "2-DOUT") (pinfunction "DOUT_2-DOUT") (pintype "output"))
      (node (ref "L19") (pin "4-DIN") (pinfunction "DIN_4-DIN") (pintype "input"))
    )
    (net (code "25") (name "Net-(L19-DOUT)") (class "Default")
      (node (ref "L19") (pin "2-DOUT") (pinfunction "DOUT_2-DOUT") (pintype "output"))
      (node (ref "L20") (pin "4-DIN") (pinfunction "DIN_4-DIN") (pintype "input"))
    )
    (net (code "26") (name "Net-(L20-DOUT)") (class "Default")
      (node (ref "L20") (pin "2-DOUT") (pinfunction "DOUT_2-DOUT") (pintype "output"))
      (node (ref "L21") (pin "4-DIN") (pinfunction "DIN_4-DIN") (pintype "input"))
    )
    (net (code "27") (name "Net-(L21-DOUT)") (class "Default")
      (node (ref "L21") (pin "2-DOUT") (pinfunction "DOUT_2-DOUT") (pintype "output"))
      (node (ref "L22") (pin "4-DIN") (pinfunction "DIN_4-DIN") (pintype "input"))
    )
    (net (code "28") (name "Net-(L22-DOUT)") (class "Default")
      (node (ref "L22") (pin "2-DOUT") (pinfunction "DOUT_2-DOUT") (pintype "output"))
      (node (ref "L23") (pin "4-DIN") (pinfunction "DIN_4-DIN") (pintype "input"))
    )
    (net (code "29") (name "Net-(L23-DOUT)") (class "Default")
      (node (ref "L23") (pin "2-DOUT") (pinfunction "DOUT_2-DOUT") (pintype "output"))
      (node (ref "L24") (pin "4-DIN") (pinfunction "DIN_4-DIN") (pintype "input"))
    )
    (net (code "30") (name "Net-(L24-DOUT)") (class "Default")
      (node (ref "L24") (pin "2-DOUT") (pinfunction "DOUT_2-DOUT") (pintype "output"))
      (node (ref "L25") (pin "4-DIN") (pinfunction "DIN_4-DIN") (pintype "input"))
    )
    (net (code "31") (name "Net-(L25-DOUT)") (class "Default")
      (node (ref "L25") (pin "2-DOUT") (pinfunction "DOUT_2-DOUT") (pintype "output"))
      (node (ref "L26") (pin "4-DIN") (pinfunction "DIN_4-DIN") (pintype "input"))
    )
    (net (code "32") (name "Net-(L26-DOUT)") (class "Default")
      (node (ref "L26") (pin "2-DOUT") (pinfunction "DOUT_2-DOUT") (pintype "output"))
      (node (ref "L27") (pin "4-DIN") (pinfunction "DIN_4-DIN") (pintype "input"))
    )
    (net (code "33") (name "Net-(L27-DOUT)") (class "Default")
      (node (ref "L27") (pin "2-DOUT") (pinfunction "DOUT_2-DOUT") (pintype "output"))
      (node (ref "L28") (pin "4-DIN") (pinfunction "DIN_4-DIN") (pintype "input"))
    )
    (net (code "34") (name "Net-(L28-DOUT)") (class "Default")
      (node (ref "L28") (pin "2-DOUT") (pinfunction "DOUT_2-DOUT") (pintype "output"))
      (node (ref "L29") (pin "4-DIN") (pinfunction "DIN_4-DIN") (pintype "input"))
    )
    (net (code "35") (name "Net-(L29-DOUT)") (class "Default")
      (node (ref "L29") (pin "2-DOUT") (pinfunction "DOUT_2-DOUT") (pintype "output"))
      (node (ref "L30") (pin "4-DIN") (pinfunction "DIN_4-DIN") (pintype "input"))
    )
    (net (code "36") (name "Net-(L30-DOUT)") (class "Default")
      (node (ref "L30") (pin "2-DOUT") (pinfunction "DOUT_2-DOUT") (pintype "output"))
      (node (ref "L31") (pin "4-DIN") (pinfunction "DIN_4-DIN") (pintype "input"))
    )
    (net (code "37") (name "Net-(L31-DOUT)") (class "Default")
      (node (ref "L31") (pin "2-DOUT") (pinfunction "DOUT_2-DOUT") (pintype "output"))
      (node (ref "L32") (pin "4-DIN") (pinfunction "DIN_4-DIN") (pintype "input"))
    )
    (net (code "38") (name "Net-(L32-DOUT)") (class "Default")
      (node (ref "L32") (pin "2-DOUT") (pinfunction "DOUT_2-DOUT") (pintype "output"))
      (node (ref "L33") (pin "4-DIN") (pinfunction "DIN_4-DIN") (pintype "input"))
    )
    (net (code "39") (name "Net-(L33-DOUT)") (class "Default")
      (node (ref "L33") (pin "2-DOUT") (pinfunction "DOUT_2-DOUT") (pintype "output"))
      (node (ref "L34") (pin "4-DIN") (pinfunction "DIN_4-DIN") (pintype "input"))
    )
    (net (code "40") (name "Net-(L34-DOUT)") (class "Default")
      (node (ref "L34") (pin "2-DOUT") (pinfunction "DOUT_2-DOUT") (pintype "output"))
      (node (ref "L35") (pin "4-DIN") (pinfunction "DIN_4-DIN") (pintype "input"))
    )
    (net (code "41") (name "Net-(L35-DOUT)") (class "Default")
      (node (ref "L35") (pin "2-DOUT") (pinfunction "DOUT_2-DOUT") (pintype "output"))
      (node (ref "L36") (pin "4-DIN") (pinfunction "DIN_4-DIN") (pintype "input"))
    )
    (net (code "42") (name "Net-(L36-DOUT)") (class "Default")
      (node (ref "L36") (pin "2-DOUT") (pinfunction "DOUT_2-DOUT") (pintype "output"))
      (node (ref "L37") (pin "4-DIN") (pinfunction "DIN_4-DIN") (pintype "input"))
    )
    (net (code "43") (name "Net-(L37-DOUT)") (class "Default")
      (node (ref "L37") (pin "2-DOUT") (pinfunction "DOUT_2-DOUT") (pintype "output"))
      (node (ref "L38") (pin "4-DIN") (pinfunction "DIN_4-DIN") (pintype "input"))
    )
    (net (code "44") (name "Net-(L38-DOUT)") (class "Default")
      (node (ref "L38") (pin "2-DOUT") (pinfunction "DOUT_2-DOUT") (pintype "output"))
      (node (ref "L39") (pin "4-DIN") (pinfunction "DIN_4-DIN") (pintype "input"))
    )
    (net (code "45") (name "Net-(L39-DOUT)") (class "Default")
      (node (ref "L39") (pin "2-DOUT") (pinfunction "DOUT_2-DOUT") (pintype "output"))
      (node (ref "L40") (pin "4-DIN") (pinfunction "DIN_4-DIN") (pintype "input"))
    )
    (net (code "46") (name "Net-(L40-DOUT)") (class "Default")
      (node (ref "L40") (pin "2-DOUT") (pinfunction "DOUT_2-DOUT") (pintype "output"))
      (node (ref "L41") (pin "4-DIN") (pinfunction "DIN_4-DIN") (pintype "input"))
    )
    (net (code "47") (name "Net-(L41-DOUT)") (class "Default")
      (node (ref "L41") (pin "2-DOUT") (pinfunction "DOUT_2-DOUT") (pintype "output"))
      (node (ref "L42") (pin "4-DIN") (pinfunction "DIN_4-DIN") (pintype "input"))
    )
    (net (code "48") (name "Net-(L42-DOUT)") (class "Default")
      (node (ref "L42") (pin "2-DOUT") (pinfunction "DOUT_2-DOUT") (pintype "output"))
      (node (ref "L43") (pin "4-DIN") (pinfunction "DIN_4-DIN") (pintype "input"))
    )
    (net (code "49") (name "Net-(L43-DOUT)") (class "Default")
      (node (ref "L43") (pin "2-DOUT") (pinfunction "DOUT_2-DOUT") (pintype "output"))
      (node (ref "L44") (pin "4-DIN") (pinfunction "DIN_4-DIN") (pintype "input"))
    )
    (net (code "50") (name "Net-(L44-DOUT)") (class "Default")
      (node (ref "L44") (pin "2-DOUT") (pinfunction "DOUT_2-DOUT") (pintype "output"))
      (node (ref "L45") (pin "4-DIN") (pinfunction "DIN_4-DIN") (pintype "input"))
    )
    (net (code "51") (name "Net-(L45-DOUT)") (class "Default")
      (node (ref "L45") (pin "2-DOUT") (pinfunction "DOUT_2-DOUT") (pintype "output"))
      (node (ref "L46") (pin "4-DIN") (pinfunction "DIN_4-DIN") (pintype "input"))
    )
    (net (code "52") (name "Net-(L46-DOUT)") (class "Default")
      (node (ref "L46") (pin "2-DOUT") (pinfunction "DOUT_2-DOUT") (pintype "output"))
      (node (ref "L47") (pin "4-DIN") (pinfunction "DIN_4-DIN") (pintype "input"))
    )
    (net (code "53") (name "Net-(L47-DOUT)") (class "Default")
      (node (ref "L47") (pin "2-DOUT") (pinfunction "DOUT_2-DOUT") (pintype "output"))
      (node (ref "L48") (pin "4-DIN") (pinfunction "DIN_4-DIN") (pintype "input"))
    )
    (net (code "54") (name "Net-(L48-DOUT)") (class "Default")
      (node (ref "L48") (pin "2-DOUT") (pinfunction "DOUT_2-DOUT") (pintype "output"))
      (node (ref "L49") (pin "4-DIN") (pinfunction "DIN_4-DIN") (pintype "input"))
    )
    (net (code "55") (name "Net-(L49-DOUT)") (class "Default")
      (node (ref "L49") (pin "2-DOUT") (pinfunction "DOUT_2-DOUT") (pintype "output"))
      (node (ref "L50") (pin "4-DIN") (pinfunction "DIN_4-DIN") (pintype "input"))
    )
    (net (code "56") (name "Net-(L50-DOUT)") (class "Default")
      (node (ref "L50") (pin "2-DOUT") (pinfunction "DOUT_2-DOUT") (pintype "output"))
      (node (ref "L51") (pin "4-DIN") (pinfunction "DIN_4-DIN") (pintype "input"))
    )
    (net (code "57") (name "Net-(L51-DOUT)") (class "Default")
      (node (ref "L51") (pin "2-DOUT") (pinfunction "DOUT_2-DOUT") (pintype "output"))
      (node (ref "L52") (pin "4-DIN") (pinfunction "DIN_4-DIN") (pintype "input"))
    )
    (net (code "58") (name "Net-(L52-DOUT)") (class "Default")
      (node (ref "L52") (pin "2-DOUT") (pinfunction "DOUT_2-DOUT") (pintype "output"))
      (node (ref "L53") (pin "4-DIN") (pinfunction "DIN_4-DIN") (pintype "input"))
    )
    (net (code "59") (name "Net-(L53-DOUT)") (class "Default")
      (node (ref "L53") (pin "2-DOUT") (pinfunction "DOUT_2-DOUT") (pintype "output"))
      (node (ref "L54") (pin "4-DIN") (pinfunction "DIN_4-DIN") (pintype "input"))
    )
    (net (code "60") (name "Net-(L54-DOUT)") (class "Default")
      (node (ref "L54") (pin "2-DOUT") (pinfunction "DOUT_2-DOUT") (pintype "output"))
      (node (ref "L55") (pin "4-DIN") (pinfunction "DIN_4-DIN") (pintype "input"))
    )
    (net (code "61") (name "Net-(L55-DOUT)") (class "Default")
      (node (ref "L55") (pin "2-DOUT") (pinfunction "DOUT_2-DOUT") (pintype "output"))
      (node (ref "L56") (pin "4-DIN") (pinfunction "DIN_4-DIN") (pintype "input"))
    )
    (net (code "62") (name "Net-(L56-DOUT)") (class "Default")
      (node (ref "L56") (pin "2-DOUT") (pinfunction "DOUT_2-DOUT") (pintype "output"))
      (node (ref "L57") (pin "4-DIN") (pinfunction "DIN_4-DIN") (pintype "input"))
    )
    (net (code "63") (name "Net-(L57-DOUT)") (class "Default")
      (node (ref "L57") (pin "2-DOUT") (pinfunction "DOUT_2-DOUT") (pintype "output"))
      (node (ref "L58") (pin "4-DIN") (pinfunction "DIN_4-DIN") (pintype "input"))
    )
    (net (code "64") (name "Net-(L58-DOUT)") (class "Default")
      (node (ref "L58") (pin "2-DOUT") (pinfunction "DOUT_2-DOUT") (pintype "output"))
      (node (ref "L59") (pin "4-DIN") (pinfunction "DIN_4-DIN") (pintype "input"))
    )
    (net (code "65") (name "Net-(L59-DOUT)") (class "Default")
      (node (ref "L59") (pin "2-DOUT") (pinfunction "DOUT_2-DOUT") (pintype "output"))
      (node (ref "L60") (pin "4-DIN") (pinfunction "DIN_4-DIN") (pintype "input"))
    )
    (net (code "66") (name "Net-(L60-DOUT)") (class "Default")
      (node (ref "L60") (pin "2-DOUT") (pinfunction "DOUT_2-DOUT") (pintype "output"))
      (node (ref "L61") (pin "4-DIN") (pinfunction "DIN_4-DIN") (pintype "input"))
    )
    (net (code "67") (name "Net-(L61-DOUT)") (class "Default")
      (node (ref "L61") (pin "2-DOUT") (pinfunction "DOUT_2-DOUT") (pintype "output"))
      (node (ref "L62") (pin "4-DIN") (pinfunction "DIN_4-DIN") (pintype "input"))
    )
    (net (code "68") (name "Net-(L62-DOUT)") (class "Default")
      (node (ref "L62") (pin "2-DOUT") (pinfunction "DOUT_2-DOUT") (pintype "output"))
      (node (ref "L63") (pin "4-DIN") (pinfunction "DIN_4-DIN") (pintype "input"))
    )
    (net (code "69") (name "Net-(L63-DOUT)") (class "Default")
      (node (ref "L63") (pin "2-DOUT") (pinfunction "DOUT_2-DOUT") (pintype "output"))
      (node (ref "L64") (pin "4-DIN") (pinfunction "DIN_4-DIN") (pintype "input"))
    )
    (net (code "70") (name "Net-(L65-DIN)") (class "Default")
      (node (ref "L65") (pin "4-DIN") (pinfunction "DIN_4-DIN") (pintype "input"))
      (node (ref "R5") (pin "2") (pinfunction "2_2") (pintype "passive"))
    )
    (net (code "71") (name "Net-(L65-DOUT)") (class "Default")
      (node (ref "L65") (pin "2-DOUT") (pinfunction "DOUT_2-DOUT") (pintype "output"))
      (node (ref "L66") (pin "4-DIN") (pinfunction "DIN_4-DIN") (pintype "input"))
    )
    (net (code "72") (name "Net-(L66-DOUT)") (class "Default")
      (node (ref "L66") (pin "2-DOUT") (pinfunction "DOUT_2-DOUT") (pintype "output"))
      (node (ref "L67") (pin "4-DIN") (pinfunction "DIN_4-DIN") (pintype "input"))
    )
    (net (code "73") (name "Net-(L67-DOUT)") (class "Default")
      (node (ref "L67") (pin "2-DOUT") (pinfunction "DOUT_2-DOUT") (pintype "output"))
      (node (ref "L68") (pin "4-DIN") (pinfunction "DIN_4-DIN") (pintype "input"))
    )
    (net (code "74") (name "Net-(L68-DOUT)") (class "Default")
      (node (ref "L68") (pin "2-DOUT") (pinfunction "DOUT_2-DOUT") (pintype "output"))
      (node (ref "L69") (pin "4-DIN") (pinfunction "DIN_4-DIN") (pintype "input"))
    )
    (net (code "75") (name "Net-(L69-DOUT)") (class "Default")
      (node (ref "L69") (pin "2-DOUT") (pinfunction "DOUT_2-DOUT") (pintype "output"))
      (node (ref "L70") (pin "4-DIN") (pinfunction "DIN_4-DIN") (pintype "input"))
    )
    (net (code "76") (name "Net-(L70-DOUT)") (class "Default")
      (node (ref "L70") (pin "2-DOUT") (pinfunction "DOUT_2-DOUT") (pintype "output"))
      (node (ref "L71") (pin "4-DIN") (pinfunction "DIN_4-DIN") (pintype "input"))
    )
    (net (code "77") (name "Net-(L71-DOUT)") (class "Default")
      (node (ref "L71") (pin "2-DOUT") (pinfunction "DOUT_2-DOUT") (pintype "output"))
      (node (ref "L72") (pin "4-DIN") (pinfunction "DIN_4-DIN") (pintype "input"))
    )
    (net (code "78") (name "Net-(L72-DOUT)") (class "Default")
      (node (ref "L72") (pin "2-DOUT") (pinfunction "DOUT_2-DOUT") (pintype "output"))
      (node (ref "L73") (pin "4-DIN") (pinfunction "DIN_4-DIN") (pintype "input"))
    )
    (net (code "79") (name "Net-(L73-DOUT)") (class "Default")
      (node (ref "L73") (pin "2-DOUT") (pinfunction "DOUT_2-DOUT") (pintype "output"))
      (node (ref "L74") (pin "4-DIN") (pinfunction "DIN_4-DIN") (pintype "input"))
    )
    (net (code "80") (name "Net-(L74-DOUT)") (class "Default")
      (node (ref "L74") (pin "2-DOUT") (pinfunction "DOUT_2-DOUT") (pintype "output"))
      (node (ref "L75") (pin "4-DIN") (pinfunction "DIN_4-DIN") (pintype "input"))
    )
    (net (code "81") (name "Net-(L75-DOUT)") (class "Default")
      (node (ref "L75") (pin "2-DOUT") (pinfunction "DOUT_2-DOUT") (pintype "output"))
      (node (ref "L76") (pin "4-DIN") (pinfunction "DIN_4-DIN") (pintype "input"))
    )
    (net (code "82") (name "Net-(L76-DOUT)") (class "Default")
      (node (ref "L76") (pin "2-DOUT") (pinfunction "DOUT_2-DOUT") (pintype "output"))
      (node (ref "L77") (pin "4-DIN") (pinfunction "DIN_4-DIN") (pintype "input"))
    )
    (net (code "83") (name "Net-(L77-DOUT)") (class "Default")
      (node (ref "L77") (pin "2-DOUT") (pinfunction "DOUT_2-DOUT") (pintype "output"))
      (node (ref "L78") (pin "4-DIN") (pinfunction "DIN_4-DIN") (pintype "input"))
    )
    (net (code "84") (name "Net-(L78-DOUT)") (class "Default")
      (node (ref "L78") (pin "2-DOUT") (pinfunction "DOUT_2-DOUT") (pintype "output"))
      (node (ref "L79") (pin "4-DIN") (pinfunction "DIN_4-DIN") (pintype "input"))
    )
    (net (code "85") (name "Net-(L79-DOUT)") (class "Default")
      (node (ref "L79") (pin "2-DOUT") (pinfunction "DOUT_2-DOUT") (pintype "output"))
      (node (ref "L80") (pin "4-DIN") (pinfunction "DIN_4-DIN") (pintype "input"))
    )
    (net (code "86") (name "Net-(L80-DOUT)") (class "Default")
      (node (ref "L80") (pin "2-DOUT") (pinfunction "DOUT_2-DOUT") (pintype "output"))
      (node (ref "L81") (pin "4-DIN") (pinfunction "DIN_4-DIN") (pintype "input"))
    )
    (net (code "87") (name "Net-(L81-DOUT)") (class "Default")
      (node (ref "L81") (pin "2-DOUT") (pinfunction "DOUT_2-DOUT") (pintype "output"))
      (node (ref "L82") (pin "4-DIN") (pinfunction "DIN_4-DIN") (pintype "input"))
    )
    (net (code "88") (name "Net-(L82-DOUT)") (class "Default")
      (node (ref "L82") (pin "2-DOUT") (pinfunction "DOUT_2-DOUT") (pintype "output"))
      (node (ref "L83") (pin "4-DIN") (pinfunction "DIN_4-DIN") (pintype "input"))
    )
    (net (code "89") (name "Net-(L83-DOUT)") (class "Default")
      (node (ref "L83") (pin "2-DOUT") (pinfunction "DOUT_2-DOUT") (pintype "output"))
      (node (ref "L84") (pin "4-DIN") (pinfunction "DIN_4-DIN") (pintype "input"))
    )
    (net (code "90") (name "Net-(L84-DOUT)") (class "Default")
      (node (ref "L84") (pin "2-DOUT") (pinfunction "DOUT_2-DOUT") (pintype "output"))
      (node (ref "L85") (pin "4-DIN") (pinfunction "DIN_4-DIN") (pintype "input"))
    )
    (net (code "91") (name "Net-(L85-DOUT)") (class "Default")
      (node (ref "L85") (pin "2-DOUT") (pinfunction "DOUT_2-DOUT") (pintype "output"))
      (node (ref "L86") (pin "4-DIN") (pinfunction "DIN_4-DIN") (pintype "input"))
    )
    (net (code "92") (name "Net-(L86-DOUT)") (class "Default")
      (node (ref "L86") (pin "2-DOUT") (pinfunction "DOUT_2-DOUT") (pintype "output"))
      (node (ref "L87") (pin "4-DIN") (pinfunction "DIN_4-DIN") (pintype "input"))
    )
    (net (code "93") (name "Net-(L87-DOUT)") (class "Default")
      (node (ref "L87") (pin "2-DOUT") (pinfunction "DOUT_2-DOUT") (pintype "output"))
      (node (ref "L88") (pin "4-DIN") (pinfunction "DIN_4-DIN") (pintype "input"))
    )
    (net (code "94") (name "Net-(L88-DOUT)") (class "Default")
      (node (ref "L88") (pin "2-DOUT") (pinfunction "DOUT_2-DOUT") (pintype "output"))
      (node (ref "L89") (pin "4-DIN") (pinfunction "DIN_4-DIN") (pintype "input"))
    )
    (net (code "95") (name "Net-(L89-DOUT)") (class "Default")
      (node (ref "L89") (pin "2-DOUT") (pinfunction "DOUT_2-DOUT") (pintype "output"))
      (node (ref "L90") (pin "4-DIN") (pinfunction "DIN_4-DIN") (pintype "input"))
    )
    (net (code "96") (name "Net-(L90-DOUT)") (class "Default")
      (node (ref "L90") (pin "2-DOUT") (pinfunction "DOUT_2-DOUT") (pintype "output"))
      (node (ref "L91") (pin "4-DIN") (pinfunction "DIN_4-DIN") (pintype "input"))
    )
    (net (code "97") (name "Net-(L91-DOUT)") (class "Default")
      (node (ref "L91") (pin "2-DOUT") (pinfunction "DOUT_2-DOUT") (pintype "output"))
      (node (ref "L92") (pin "4-DIN") (pinfunction "DIN_4-DIN") (pintype "input"))
    )
    (net (code "98") (name "Net-(L92-DOUT)") (class "Default")
      (node (ref "L92") (pin "2-DOUT") (pinfunction "DOUT_2-DOUT") (pintype "output"))
      (node (ref "L93") (pin "4-DIN") (pinfunction "DIN_4-DIN") (pintype "input"))
    )
    (net (code "99") (name "Net-(L93-DOUT)") (class "Default")
      (node (ref "L93") (pin "2-DOUT") (pinfunction "DOUT_2-DOUT") (pintype "output"))
      (node (ref "L94") (pin "4-DIN") (pinfunction "DIN_4-DIN") (pintype "input"))
    )
    (net (code "100") (name "Net-(L94-DOUT)") (class "Default")
      (node (ref "L94") (pin "2-DOUT") (pinfunction "DOUT_2-DOUT") (pintype "output"))
      (node (ref "L95") (pin "4-DIN") (pinfunction "DIN_4-DIN") (pintype "input"))
    )
    (net (code "101") (name "Net-(L95-DOUT)") (class "Default")
      (node (ref "L95") (pin "2-DOUT") (pinfunction "DOUT_2-DOUT") (pintype "output"))
      (node (ref "L96") (pin "4-DIN") (pinfunction "DIN_4-DIN") (pintype "input"))
    )
    (net (code "102") (name "Net-(L96-DOUT)") (class "Default")
      (node (ref "L96") (pin "2-DOUT") (pinfunction "DOUT_2-DOUT") (pintype "output"))
      (node (ref "L97") (pin "4-DIN") (pinfunction "DIN_4-DIN") (pintype "input"))
    )
    (net (code "103") (name "Net-(L97-DOUT)") (class "Default")
      (node (ref "L97") (pin "2-DOUT") (pinfunction "DOUT_2-DOUT") (pintype "output"))
      (node (ref "L98") (pin "4-DIN") (pinfunction "DIN_4-DIN") (pintype "input"))
    )
    (net (code "104") (name "Net-(L98-DOUT)") (class "Default")
      (node (ref "L98") (pin "2-DOUT") (pinfunction "DOUT_2-DOUT") (pintype "output"))
      (node (ref "L99") (pin "4-DIN") (pinfunction "DIN_4-DIN") (pintype "input"))
    )
    (net (code "105") (name "Net-(L100-DIN)") (class "Default")
      (node (ref "L100") (pin "4-DIN") (pinfunction "DIN_4-DIN") (pintype "input"))
      (node (ref "L99") (pin "2-DOUT") (pinfunction "DOUT_2-DOUT") (pintype "output"))
    )
    (net (code "106") (name "Net-(L100-DOUT)") (class "Default")
      (node (ref "L100") (pin "2-DOUT") (pinfunction "DOUT_2-DOUT") (pintype "output"))
      (node (ref "L101") (pin "4-DIN") (pinfunction "DIN_4-DIN") (pintype "input"))
    )
    (net (code "107") (name "Net-(L101-DOUT)") (class "Default")
      (node (ref "L101") (pin "2-DOUT") (pinfunction "DOUT_2-DOUT") (pintype "output"))
      (node (ref "L102") (pin "4-DIN") (pinfunction "DIN_4-DIN") (pintype "input"))
    )
    (net (code "108") (name "Net-(L102-DOUT)") (class "Default")
      (node (ref "L102") (pin "2-DOUT") (pinfunction "DOUT_2-DOUT") (pintype "output"))
      (node (ref "L103") (pin "4-DIN") (pinfunction "DIN_4-DIN") (pintype "input"))
    )
    (net (code "109") (name "Net-(L103-DOUT)") (class "Default")
      (node (ref "L103") (pin "2-DOUT") (pinfunction "DOUT_2-DOUT") (pintype "output"))
      (node (ref "L104") (pin "4-DIN") (pinfunction "DIN_4-DIN") (pintype "input"))
    )
    (net (code "110") (name "Net-(L104-DOUT)") (class "Default")
      (node (ref "L104") (pin "2-DOUT") (pinfunction "DOUT_2-DOUT") (pintype "output"))
      (node (ref "L105") (pin "4-DIN") (pinfunction "DIN_4-DIN") (pintype "input"))
    )
    (net (code "111") (name "Net-(L105-DOUT)") (class "Default")
      (node (ref "L105") (pin "2-DOUT") (pinfunction "DOUT_2-DOUT") (pintype "output"))
      (node (ref "L106") (pin "4-DIN") (pinfunction "DIN_4-DIN") (pintype "input"))
    )
    (net (code "112") (name "Net-(L106-DOUT)") (class "Default")
      (node (ref "L106") (pin "2-DOUT") (pinfunction "DOUT_2-DOUT") (pintype "output"))
      (node (ref "L107") (pin "4-DIN") (pinfunction "DIN_4-DIN") (pintype "input"))
    )
    (net (code "113") (name "Net-(L107-DOUT)") (class "Default")
      (node (ref "L107") (pin "2-DOUT") (pinfunction "DOUT_2-DOUT") (pintype "output"))
      (node (ref "L108") (pin "4-DIN") (pinfunction "DIN_4-DIN") (pintype "input"))
    )
    (net (code "114") (name "Net-(L108-DOUT)") (class "Default")
      (node (ref "L108") (pin "2-DOUT") (pinfunction "DOUT_2-DOUT") (pintype "output"))
      (node (ref "L109") (pin "4-DIN") (pinfunction "DIN_4-DIN") (pintype "input"))
    )
    (net (code "115") (name "Net-(L109-DOUT)") (class "Default")
      (node (ref "L109") (pin "2-DOUT") (pinfunction "DOUT_2-DOUT") (pintype "output"))
      (node (ref "L110") (pin "4-DIN") (pinfunction "DIN_4-DIN") (pintype "input"))
    )
    (net (code "116") (name "Net-(L110-DOUT)") (class "Default")
      (node (ref "L110") (pin "2-DOUT") (pinfunction "DOUT_2-DOUT") (pintype "output"))
      (node (ref "L111") (pin "4-DIN") (pinfunction "DIN_4-DIN") (pintype "input"))
    )
    (net (code "117") (name "Net-(L111-DOUT)") (class "Default")
      (node (ref "L111") (pin "2-DOUT") (pinfunction "DOUT_2-DOUT") (pintype "output"))
      (node (ref "L112") (pin "4-DIN") (pinfunction "DIN_4-DIN") (pintype "input"))
    )
    (net (code "118") (name "Net-(L112-DOUT)") (class "Default")
      (node (ref "L112") (pin "2-DOUT") (pinfunction "DOUT_2-DOUT") (pintype "output"))
      (node (ref "L113") (pin "4-DIN") (pinfunction "DIN_4-DIN") (pintype "input"))
    )
    (net (code "119") (name "Net-(L113-DOUT)") (class "Default")
      (node (ref "L113") (pin "2-DOUT") (pinfunction "DOUT_2-DOUT") (pintype "output"))
      (node (ref "L114") (pin "4-DIN") (pinfunction "DIN_4-DIN") (pintype "input"))
    )
    (net (code "120") (name "Net-(L114-DOUT)") (class "Default")
      (node (ref "L114") (pin "2-DOUT") (pinfunction "DOUT_2-DOUT") (pintype "output"))
      (node (ref "L115") (pin "4-DIN") (pinfunction "DIN_4-DIN") (pintype "input"))
    )
    (net (code "121") (name "Net-(L115-DOUT)") (class "Default")
      (node (ref "L115") (pin "2-DOUT") (pinfunction "DOUT_2-DOUT") (pintype "output"))
      (node (ref "L116") (pin "4-DIN") (pinfunction "DIN_4-DIN") (pintype "input"))
    )
    (net (code "122") (name "Net-(L116-DOUT)") (class "Default")
      (node (ref "L116") (pin "2-DOUT") (pinfunction "DOUT_2-DOUT") (pintype "output"))
      (node (ref "L117") (pin "4-DIN") (pinfunction "DIN_4-DIN") (pintype "input"))
    )
    (net (code "123") (name "Net-(L117-DOUT)") (class "Default")
      (node (ref "L117") (pin "2-DOUT") (pinfunction "DOUT_2-DOUT") (pintype "output"))
      (node (ref "L118") (pin "4-DIN") (pinfunction "DIN_4-DIN") (pintype "input"))
    )
    (net (code "124") (name "Net-(L118-DOUT)") (class "Default")
      (node (ref "L118") (pin "2-DOUT") (pinfunction "DOUT_2-DOUT") (pintype "output"))
      (node (ref "L119") (pin "4-DIN") (pinfunction "DIN_4-DIN") (pintype "input"))
    )
    (net (code "125") (name "Net-(L119-DOUT)") (class "Default")
      (node (ref "L119") (pin "2-DOUT") (pinfunction "DOUT_2-DOUT") (pintype "output"))
      (node (ref "L120") (pin "4-DIN") (pinfunction "DIN_4-DIN") (pintype "input"))
    )
    (net (code "126") (name "Net-(L120-DOUT)") (class "Default")
      (node (ref "L120") (pin "2-DOUT") (pinfunction "DOUT_2-DOUT") (pintype "output"))
      (node (ref "L121") (pin "4-DIN") (pinfunction "DIN_4-DIN") (pintype "input"))
    )
    (net (code "127") (name "Net-(L121-DOUT)") (class "Default")
      (node (ref "L121") (pin "2-DOUT") (pinfunction "DOUT_2-DOUT") (pintype "output"))
      (node (ref "L122") (pin "4-DIN") (pinfunction "DIN_4-DIN") (pintype "input"))
    )
    (net (code "128") (name "Net-(L122-DOUT)") (class "Default")
      (node (ref "L122") (pin "2-DOUT") (pinfunction "DOUT_2-DOUT") (pintype "output"))
      (node (ref "L123") (pin "4-DIN") (pinfunction "DIN_4-DIN") (pintype "input"))
    )
    (net (code "129") (name "Net-(L123-DOUT)") (class "Default")
      (node (ref "L123") (pin "2-DOUT") (pinfunction "DOUT_2-DOUT") (pintype "output"))
      (node (ref "L124") (pin "4-DIN") (pinfunction "DIN_4-DIN") (pintype "input"))
    )
    (net (code "130") (name "Net-(L124-DOUT)") (class "Default")
      (node (ref "L124") (pin "2-DOUT") (pinfunction "DOUT_2-DOUT") (pintype "output"))
      (node (ref "L125") (pin "4-DIN") (pinfunction "DIN_4-DIN") (pintype "input"))
    )
    (net (code "131") (name "Net-(L125-DOUT)") (class "Default")
      (node (ref "L125") (pin "2-DOUT") (pinfunction "DOUT_2-DOUT") (pintype "output"))
      (node (ref "L126") (pin "4-DIN") (pinfunction "DIN_4-DIN") (pintype "input"))
    )
    (net (code "132") (name "Net-(L126-DOUT)") (class "Default")
      (node (ref "L126") (pin "2-DOUT") (pinfunction "DOUT_2-DOUT") (pintype "output"))
      (node (ref "L127") (pin "4-DIN") (pinfunction "DIN_4-DIN") (pintype "input"))
    )
    (net (code "133") (name "Net-(L127-DOUT)") (class "Default")
      (node (ref "L127") (pin "2-DOUT") (pinfunction "DOUT_2-DOUT") (pintype "output"))
      (node (ref "L128") (pin "4-DIN") (pinfunction "DIN_4-DIN") (pintype "input"))
    )
    (net (code "134") (name "Net-(L129-DIN)") (class "Default")
      (node (ref "L129") (pin "4-DIN") (pinfunction "DIN_4-DIN") (pintype "input"))
      (node (ref "R3") (pin "2") (pinfunction "2_2") (pintype "passive"))
    )
    (net (code "135") (name "Net-(L129-DOUT)") (class "Default")
      (node (ref "L129") (pin "2-DOUT") (pinfunction "DOUT_2-DOUT") (pintype "output"))
      (node (ref "L130") (pin "4-DIN") (pinfunction "DIN_4-DIN") (pintype "input"))
    )
    (net (code "136") (name "Net-(L130-DOUT)") (class "Default")
      (node (ref "L130") (pin "2-DOUT") (pinfunction "DOUT_2-DOUT") (pintype "output"))
      (node (ref "L131") (pin "4-DIN") (pinfunction "DIN_4-DIN") (pintype "input"))
    )
    (net (code "137") (name "Net-(L131-DOUT)") (class "Default")
      (node (ref "L131") (pin "2-DOUT") (pinfunction "DOUT_2-DOUT") (pintype "output"))
      (node (ref "L132") (pin "4-DIN") (pinfunction "DIN_4-DIN") (pintype "input"))
    )
    (net (code "138") (name "Net-(L132-DOUT)") (class "Default")
      (node (ref "L132") (pin "2-DOUT") (pinfunction "DOUT_2-DOUT") (pintype "output"))
      (node (ref "L133") (pin "4-DIN") (pinfunction "DIN_4-DIN") (pintype "input"))
    )
    (net (code "139") (name "Net-(L133-DOUT)") (class "Default")
      (node (ref "L133") (pin "2-DOUT") (pinfunction "DOUT_2-DOUT") (pintype "output"))
      (node (ref "L134") (pin "4-DIN") (pinfunction "DIN_4-DIN") (pintype "input"))
    )
    (net (code "140") (name "Net-(L134-DOUT)") (class "Default")
      (node (ref "L134") (pin "2-DOUT") (pinfunction "DOUT_2-DOUT") (pintype "output"))
      (node (ref "L135") (pin "4-DIN") (pinfunction "DIN_4-DIN") (pintype "input"))
    )
    (net (code "141") (name "Net-(L135-DOUT)") (class "Default")
      (node (ref "L135") (pin "2-DOUT") (pinfunction "DOUT_2-DOUT") (pintype "output"))
      (node (ref "L136") (pin "4-DIN") (pinfunction "DIN_4-DIN") (pintype "input"))
    )
    (net (code "142") (name "Net-(L136-DOUT)") (class "Default")
      (node (ref "L136") (pin "2-DOUT") (pinfunction "DOUT_2-DOUT") (pintype "output"))
      (node (ref "L137") (pin "4-DIN") (pinfunction "DIN_4-DIN") (pintype "input"))
    )
    (net (code "143") (name "Net-(L137-DOUT)") (class "Default")
      (node (ref "L137") (pin "2-DOUT") (pinfunction "DOUT_2-DOUT") (pintype "output"))
      (node (ref "L138") (pin "4-DIN") (pinfunction "DIN_4-DIN") (pintype "input"))
    )
    (net (code "144") (name "Net-(L138-DOUT)") (class "Default")
      (node (ref "L138") (pin "2-DOUT") (pinfunction "DOUT_2-DOUT") (pintype "output"))
      (node (ref "L139") (pin "4-DIN") (pinfunction "DIN_4-DIN") (pintype "input"))
    )
    (net (code "145") (name "Net-(L139-DOUT)") (class "Default")
      (node (ref "L139") (pin "2-DOUT") (pinfunction "DOUT_2-DOUT") (pintype "output"))
      (node (ref "L140") (pin "4-DIN") (pinfunction "DIN_4-DIN") (pintype "input"))
    )
    (net (code "146") (name "Net-(L140-DOUT)") (class "Default")
      (node (ref "L140") (pin "2-DOUT") (pinfunction "DOUT_2-DOUT") (pintype "output"))
      (node (ref "L141") (pin "4-DIN") (pinfunction "DIN_4-DIN") (pintype "input"))
    )
    (net (code "147") (name "Net-(L141-DOUT)") (class "Default")
      (node (ref "L141") (pin "2-DOUT") (pinfunction "DOUT_2-DOUT") (pintype "output"))
      (node (ref "L142") (pin "4-DIN") (pinfunction "DIN_4-DIN") (pintype "input"))
    )
    (net (code "148") (name "Net-(L142-DOUT)") (class "Default")
      (node (ref "L142") (pin "2-DOUT") (pinfunction "DOUT_2-DOUT") (pintype "output"))
      (node (ref "L143") (pin "4-DIN") (pinfunction "DIN_4-DIN") (pintype "input"))
    )
    (net (code "149") (name "Net-(L143-DOUT)") (class "Default")
      (node (ref "L143") (pin "2-DOUT") (pinfunction "DOUT_2-DOUT") (pintype "output"))
      (node (ref "L144") (pin "4-DIN") (pinfunction "DIN_4-DIN") (pintype "input"))
    )
    (net (code "150") (name "Net-(L144-DOUT)") (class "Default")
      (node (ref "L144") (pin "2-DOUT") (pinfunction "DOUT_2-DOUT") (pintype "output"))
      (node (ref "L145") (pin "4-DIN") (pinfunction "DIN_4-DIN") (pintype "input"))
    )
    (net (code "151") (name "Net-(L145-DOUT)") (class "Default")
      (node (ref "L145") (pin "2-DOUT") (pinfunction "DOUT_2-DOUT") (pintype "output"))
      (node (ref "L146") (pin "4-DIN") (pinfunction "DIN_4-DIN") (pintype "input"))
    )
    (net (code "152") (name "Net-(L146-DOUT)") (class "Default")
      (node (ref "L146") (pin "2-DOUT") (pinfunction "DOUT_2-DOUT") (pintype "output"))
      (node (ref "L147") (pin "4-DIN") (pinfunction "DIN_4-DIN") (pintype "input"))
    )
    (net (code "153") (name "Net-(L147-DOUT)") (class "Default")
      (node (ref "L147") (pin "2-DOUT") (pinfunction "DOUT_2-DOUT") (pintype "output"))
      (node (ref "L148") (pin "4-DIN") (pinfunction "DIN_4-DIN") (pintype "input"))
    )
    (net (code "154") (name "Net-(L148-DOUT)") (class "Default")
      (node (ref "L148") (pin "2-DOUT") (pinfunction "DOUT_2-DOUT") (pintype "output"))
      (node (ref "L149") (pin "4-DIN") (pinfunction "DIN_4-DIN") (pintype "input"))
    )
    (net (code "155") (name "Net-(L149-DOUT)") (class "Default")
      (node (ref "L149") (pin "2-DOUT") (pinfunction "DOUT_2-DOUT") (pintype "output"))
      (node (ref "L150") (pin "4-DIN") (pinfunction "DIN_4-DIN") (pintype "input"))
    )
    (net (code "156") (name "Net-(L150-DOUT)") (class "Default")
      (node (ref "L150") (pin "2-DOUT") (pinfunction "DOUT_2-DOUT") (pintype "output"))
      (node (ref "L151") (pin "4-DIN") (pinfunction "DIN_4-DIN") (pintype "input"))
    )
    (net (code "157") (name "Net-(L151-DOUT)") (class "Default")
      (node (ref "L151") (pin "2-DOUT") (pinfunction "DOUT_2-DOUT") (pintype "output"))
      (node (ref "L152") (pin "4-DIN") (pinfunction "DIN_4-DIN") (pintype "input"))
    )
    (net (code "158") (name "Net-(L152-DOUT)") (class "Default")
      (node (ref "L152") (pin "2-DOUT") (pinfunction "DOUT_2-DOUT") (pintype "output"))
      (node (ref "L153") (pin "4-DIN") (pinfunction "DIN_4-DIN") (pintype "input"))
    )
    (net (code "159") (name "Net-(L153-DOUT)") (class "Default")
      (node (ref "L153") (pin "2-DOUT") (pinfunction "DOUT_2-DOUT") (pintype "output"))
      (node (ref "L154") (pin "4-DIN") (pinfunction "DIN_4-DIN") (pintype "input"))
    )
    (net (code "160") (name "Net-(L154-DOUT)") (class "Default")
      (node (ref "L154") (pin "2-DOUT") (pinfunction "DOUT_2-DOUT") (pintype "output"))
      (node (ref "L155") (pin "4-DIN") (pinfunction "DIN_4-DIN") (pintype "input"))
    )
    (net (code "161") (name "Net-(L155-DOUT)") (class "Default")
      (node (ref "L155") (pin "2-DOUT") (pinfunction "DOUT_2-DOUT") (pintype "output"))
      (node (ref "L156") (pin "4-DIN") (pinfunction "DIN_4-DIN") (pintype "input"))
    )
    (net (code "162") (name "Net-(L156-DOUT)") (class "Default")
      (node (ref "L156") (pin "2-DOUT") (pinfunction "DOUT_2-DOUT") (pintype "output"))
      (node (ref "L157") (pin "4-DIN") (pinfunction "DIN_4-DIN") (pintype "input"))
    )
    (net (code "163") (name "Net-(L157-DOUT)") (class "Default")
      (node (ref "L157") (pin "2-DOUT") (pinfunction "DOUT_2-DOUT") (pintype "output"))
      (node (ref "L158") (pin "4-DIN") (pinfunction "DIN_4-DIN") (pintype "input"))
    )
    (net (code "164") (name "Net-(L158-DOUT)") (class "Default")
      (node (ref "L158") (pin "2-DOUT") (pinfunction "DOUT_2-DOUT") (pintype "output"))
      (node (ref "L159") (pin "4-DIN") (pinfunction "DIN_4-DIN") (pintype "input"))
    )
    (net (code "165") (name "Net-(L159-DOUT)") (class "Default")
      (node (ref "L159") (pin "2-DOUT") (pinfunction "DOUT_2-DOUT") (pintype "output"))
      (node (ref "L160") (pin "4-DIN") (pinfunction "DIN_4-DIN") (pintype "input"))
    )
    (net (code "166") (name "Net-(L160-DOUT)") (class "Default")
      (node (ref "L160") (pin "2-DOUT") (pinfunction "DOUT_2-DOUT") (pintype "output"))
      (node (ref "L161") (pin "4-DIN") (pinfunction "DIN_4-DIN") (pintype "input"))
    )
    (net (code "167") (name "Net-(L161-DOUT)") (class "Default")
      (node (ref "L161") (pin "2-DOUT") (pinfunction "DOUT_2-DOUT") (pintype "output"))
      (node (ref "L162") (pin "4-DIN") (pinfunction "DIN_4-DIN") (pintype "input"))
    )
    (net (code "168") (name "Net-(L162-DOUT)") (class "Default")
      (node (ref "L162") (pin "2-DOUT") (pinfunction "DOUT_2-DOUT") (pintype "output"))
      (node (ref "L163") (pin "4-DIN") (pinfunction "DIN_4-DIN") (pintype "input"))
    )
    (net (code "169") (name "Net-(L163-DOUT)") (class "Default")
      (node (ref "L163") (pin "2-DOUT") (pinfunction "DOUT_2-DOUT") (pintype "output"))
      (node (ref "L164") (pin "4-DIN") (pinfunction "DIN_4-DIN") (pintype "input"))
    )
    (net (code "170") (name "Net-(L164-DOUT)") (class "Default")
      (node (ref "L164") (pin "2-DOUT") (pinfunction "DOUT_2-DOUT") (pintype "output"))
      (node (ref "L165") (pin "4-DIN") (pinfunction "DIN_4-DIN") (pintype "input"))
    )
    (net (code "171") (name "Net-(L165-DOUT)") (class "Default")
      (node (ref "L165") (pin "2-DOUT") (pinfunction "DOUT_2-DOUT") (pintype "output"))
      (node (ref "L166") (pin "4-DIN") (pinfunction "DIN_4-DIN") (pintype "input"))
    )
    (net (code "172") (name "Net-(L166-DOUT)") (class "Default")
      (node (ref "L166") (pin "2-DOUT") (pinfunction "DOUT_2-DOUT") (pintype "output"))
      (node (ref "L167") (pin "4-DIN") (pinfunction "DIN_4-DIN") (pintype "input"))
    )
    (net (code "173") (name "Net-(L167-DOUT)") (class "Default")
      (node (ref "L167") (pin "2-DOUT") (pinfunction "DOUT_2-DOUT") (pintype "output"))
      (node (ref "L168") (pin "4-DIN") (pinfunction "DIN_4-DIN") (pintype "input"))
    )
    (net (code "174") (name "Net-(L168-DOUT)") (class "Default")
      (node (ref "L168") (pin "2-DOUT") (pinfunction "DOUT_2-DOUT") (pintype "output"))
      (node (ref "L169") (pin "4-DIN") (pinfunction "DIN_4-DIN") (pintype "input"))
    )
    (net (code "175") (name "Net-(L169-DOUT)") (class "Default")
      (node (ref "L169") (pin "2-DOUT") (pinfunction "DOUT_2-DOUT") (pintype "output"))
      (node (ref "L170") (pin "4-DIN") (pinfunction "DIN_4-DIN") (pintype "input"))
    )
    (net (code "176") (name "Net-(L170-DOUT)") (class "Default")
      (node (ref "L170") (pin "2-DOUT") (pinfunction "DOUT_2-DOUT") (pintype "output"))
      (node (ref "L171") (pin "4-DIN") (pinfunction "DIN_4-DIN") (pintype "input"))
    )
    (net (code "177") (name "Net-(L171-DOUT)") (class "Default")
      (node (ref "L171") (pin "2-DOUT") (pinfunction "DOUT_2-DOUT") (pintype "output"))
      (node (ref "L172") (pin "4-DIN") (pinfunction "DIN_4-DIN") (pintype "input"))
    )
    (net (code "178") (name "Net-(L172-DOUT)") (class "Default")
      (node (ref "L172") (pin "2-DOUT") (pinfunction "DOUT_2-DOUT") (pintype "output"))
      (node (ref "L173") (pin "4-DIN") (pinfunction "DIN_4-DIN") (pintype "input"))
    )
    (net (code "179") (name "Net-(L173-DOUT)") (class "Default")
      (node (ref "L173") (pin "2-DOUT") (pinfunction "DOUT_2-DOUT") (pintype "output"))
      (node (ref "L174") (pin "4-DIN") (pinfunction "DIN_4-DIN") (pintype "input"))
    )
    (net (code "180") (name "Net-(L174-DOUT)") (class "Default")
      (node (ref "L174") (pin "2-DOUT") (pinfunction "DOUT_2-DOUT") (pintype "output"))
      (node (ref "L175") (pin "4-DIN") (pinfunction "DIN_4-DIN") (pintype "input"))
    )
    (net (code "181") (name "Net-(L175-DOUT)") (class "Default")
      (node (ref "L175") (pin "2-DOUT") (pinfunction "DOUT_2-DOUT") (pintype "output"))
      (node (ref "L176") (pin "4-DIN") (pinfunction "DIN_4-DIN") (pintype "input"))
    )
    (net (code "182") (name "Net-(L176-DOUT)") (class "Default")
      (node (ref "L176") (pin "2-DOUT") (pinfunction "DOUT_2-DOUT") (pintype "output"))
      (node (ref "L177") (pin "4-DIN") (pinfunction "DIN_4-DIN") (pintype "input"))
    )
    (net (code "183") (name "Net-(L177-DOUT)") (class "Default")
      (node (ref "L177") (pin "2-DOUT") (pinfunction "DOUT_2-DOUT") (pintype "output"))
      (node (ref "L178") (pin "4-DIN") (pinfunction "DIN_4-DIN") (pintype "input"))
    )
    (net (code "184") (name "Net-(L178-DOUT)") (class "Default")
      (node (ref "L178") (pin "2-DOUT") (pinfunction "DOUT_2-DOUT") (pintype "output"))
      (node (ref "L179") (pin "4-DIN") (pinfunction "DIN_4-DIN") (pintype "input"))
    )
    (net (code "185") (name "Net-(L179-DOUT)") (class "Default")
      (node (ref "L179") (pin "2-DOUT") (pinfunction "DOUT_2-DOUT") (pintype "output"))
      (node (ref "L180") (pin "4-DIN") (pinfunction "DIN_4-DIN") (pintype "input"))
    )
    (net (code "186") (name "Net-(L180-DOUT)") (class "Default")
      (node (ref "L180") (pin "2-DOUT") (pinfunction "DOUT_2-DOUT") (pintype "output"))
      (node (ref "L181") (pin "4-DIN") (pinfunction "DIN_4-DIN") (pintype "input"))
    )
    (net (code "187") (name "Net-(L181-DOUT)") (class "Default")
      (node (ref "L181") (pin "2-DOUT") (pinfunction "DOUT_2-DOUT") (pintype "output"))
      (node (ref "L182") (pin "4-DIN") (pinfunction "DIN_4-DIN") (pintype "input"))
    )
    (net (code "188") (name "Net-(L182-DOUT)") (class "Default")
      (node (ref "L182") (pin "2-DOUT") (pinfunction "DOUT_2-DOUT") (pintype "output"))
      (node (ref "L183") (pin "4-DIN") (pinfunction "DIN_4-DIN") (pintype "input"))
    )
    (net (code "189") (name "Net-(L183-DOUT)") (class "Default")
      (node (ref "L183") (pin "2-DOUT") (pinfunction "DOUT_2-DOUT") (pintype "output"))
      (node (ref "L184") (pin "4-DIN") (pinfunction "DIN_4-DIN") (pintype "input"))
    )
    (net (code "190") (name "Net-(L184-DOUT)") (class "Default")
      (node (ref "L184") (pin "2-DOUT") (pinfunction "DOUT_2-DOUT") (pintype "output"))
      (node (ref "L185") (pin "4-DIN") (pinfunction "DIN_4-DIN") (pintype "input"))
    )
    (net (code "191") (name "Net-(L185-DOUT)") (class "Default")
      (node (ref "L185") (pin "2-DOUT") (pinfunction "DOUT_2-DOUT") (pintype "output"))
      (node (ref "L186") (pin "4-DIN") (pinfunction "DIN_4-DIN") (pintype "input"))
    )
    (net (code "192") (name "Net-(L186-DOUT)") (class "Default")
      (node (ref "L186") (pin "2-DOUT") (pinfunction "DOUT_2-DOUT") (pintype "output"))
      (node (ref "L187") (pin "4-DIN") (pinfunction "DIN_4-DIN") (pintype "input"))
    )
    (net (code "193") (name "Net-(L187-DOUT)") (class "Default")
      (node (ref "L187") (pin "2-DOUT") (pinfunction "DOUT_2-DOUT") (pintype "output"))
      (node (ref "L188") (pin "4-DIN") (pinfunction "DIN_4-DIN") (pintype "input"))
    )
    (net (code "194") (name "Net-(L188-DOUT)") (class "Default")
      (node (ref "L188") (pin "2-DOUT") (pinfunction "DOUT_2-DOUT") (pintype "output"))
      (node (ref "L189") (pin "4-DIN") (pinfunction "DIN_4-DIN") (pintype "input"))
    )
    (net (code "195") (name "Net-(L189-DOUT)") (class "Default")
      (node (ref "L189") (pin "2-DOUT") (pinfunction "DOUT_2-DOUT") (pintype "output"))
      (node (ref "L190") (pin "4-DIN") (pinfunction "DIN_4-DIN") (pintype "input"))
    )
    (net (code "196") (name "Net-(L190-DOUT)") (class "Default")
      (node (ref "L190") (pin "2-DOUT") (pinfunction "DOUT_2-DOUT") (pintype "output"))
      (node (ref "L191") (pin "4-DIN") (pinfunction "DIN_4-DIN") (pintype "input"))
    )
    (net (code "197") (name "Net-(L191-DOUT)") (class "Default")
      (node (ref "L191") (pin "2-DOUT") (pinfunction "DOUT_2-DOUT") (pintype "output"))
      (node (ref "L192") (pin "4-DIN") (pinfunction "DIN_4-DIN") (pintype "input"))
    )
    (net (code "198") (name "Net-(L193-DIN)") (class "Default")
      (node (ref "L193") (pin "4-DIN") (pinfunction "DIN_4-DIN") (pintype "input"))
      (node (ref "R2") (pin "2") (pinfunction "2_2") (pintype "passive"))
    )
    (net (code "199") (name "Net-(L193-DOUT)") (class "Default")
      (node (ref "L193") (pin "2-DOUT") (pinfunction "DOUT_2-DOUT") (pintype "output"))
      (node (ref "L194") (pin "4-DIN") (pinfunction "DIN_4-DIN") (pintype "input"))
    )
    (net (code "200") (name "Net-(L194-DOUT)") (class "Default")
      (node (ref "L194") (pin "2-DOUT") (pinfunction "DOUT_2-DOUT") (pintype "output"))
      (node (ref "L195") (pin "4-DIN") (pinfunction "DIN_4-DIN") (pintype "input"))
    )
    (net (code "201") (name "Net-(L195-DOUT)") (class "Default")
      (node (ref "L195") (pin "2-DOUT") (pinfunction "DOUT_2-DOUT") (pintype "output"))
      (node (ref "L196") (pin "4-DIN") (pinfunction "DIN_4-DIN") (pintype "input"))
    )
    (net (code "202") (name "Net-(L196-DOUT)") (class "Default")
      (node (ref "L196") (pin "2-DOUT") (pinfunction "DOUT_2-DOUT") (pintype "output"))
      (node (ref "L197") (pin "4-DIN") (pinfunction "DIN_4-DIN") (pintype "input"))
    )
    (net (code "203") (name "Net-(L197-DOUT)") (class "Default")
      (node (ref "L197") (pin "2-DOUT") (pinfunction "DOUT_2-DOUT") (pintype "output"))
      (node (ref "L198") (pin "4-DIN") (pinfunction "DIN_4-DIN") (pintype "input"))
    )
    (net (code "204") (name "Net-(L198-DOUT)") (class "Default")
      (node (ref "L198") (pin "2-DOUT") (pinfunction "DOUT_2-DOUT") (pintype "output"))
      (node (ref "L199") (pin "4-DIN") (pinfunction "DIN_4-DIN") (pintype "input"))
    )
    (net (code "205") (name "Net-(L199-DOUT)") (class "Default")
      (node (ref "L199") (pin "2-DOUT") (pinfunction "DOUT_2-DOUT") (pintype "output"))
      (node (ref "L200") (pin "4-DIN") (pinfunction "DIN_4-DIN") (pintype "input"))
    )
    (net (code "206") (name "Net-(L200-DOUT)") (class "Default")
      (node (ref "L200") (pin "2-DOUT") (pinfunction "DOUT_2-DOUT") (pintype "output"))
      (node (ref "L201") (pin "4-DIN") (pinfunction "DIN_4-DIN") (pintype "input"))
    )
    (net (code "207") (name "Net-(L201-DOUT)") (class "Default")
      (node (ref "L201") (pin "2-DOUT") (pinfunction "DOUT_2-DOUT") (pintype "output"))
      (node (ref "L202") (pin "4-DIN") (pinfunction "DIN_4-DIN") (pintype "input"))
    )
    (net (code "208") (name "Net-(L202-DOUT)") (class "Default")
      (node (ref "L202") (pin "2-DOUT") (pinfunction "DOUT_2-DOUT") (pintype "output"))
      (node (ref "L203") (pin "4-DIN") (pinfunction "DIN_4-DIN") (pintype "input"))
    )
    (net (code "209") (name "Net-(L203-DOUT)") (class "Default")
      (node (ref "L203") (pin "2-DOUT") (pinfunction "DOUT_2-DOUT") (pintype "output"))
      (node (ref "L204") (pin "4-DIN") (pinfunction "DIN_4-DIN") (pintype "input"))
    )
    (net (code "210") (name "Net-(L204-DOUT)") (class "Default")
      (node (ref "L204") (pin "2-DOUT") (pinfunction "DOUT_2-DOUT") (pintype "output"))
      (node (ref "L205") (pin "4-DIN") (pinfunction "DIN_4-DIN") (pintype "input"))
    )
    (net (code "211") (name "Net-(L205-DOUT)") (class "Default")
      (node (ref "L205") (pin "2-DOUT") (pinfunction "DOUT_2-DOUT") (pintype "output"))
      (node (ref "L206") (pin "4-DIN") (pinfunction "DIN_4-DIN") (pintype "input"))
    )
    (net (code "212") (name "Net-(L206-DOUT)") (class "Default")
      (node (ref "L206") (pin "2-DOUT") (pinfunction "DOUT_2-DOUT") (pintype "output"))
      (node (ref "L207") (pin "4-DIN") (pinfunction "DIN_4-DIN") (pintype "input"))
    )
    (net (code "213") (name "Net-(L207-DOUT)") (class "Default")
      (node (ref "L207") (pin "2-DOUT") (pinfunction "DOUT_2-DOUT") (pintype "output"))
      (node (ref "L208") (pin "4-DIN") (pinfunction "DIN_4-DIN") (pintype "input"))
    )
    (net (code "214") (name "Net-(L208-DOUT)") (class "Default")
      (node (ref "L208") (pin "2-DOUT") (pinfunction "DOUT_2-DOUT") (pintype "output"))
      (node (ref "L209") (pin "4-DIN") (pinfunction "DIN_4-DIN") (pintype "input"))
    )
    (net (code "215") (name "Net-(L209-DOUT)") (class "Default")
      (node (ref "L209") (pin "2-DOUT") (pinfunction "DOUT_2-DOUT") (pintype "output"))
      (node (ref "L210") (pin "4-DIN") (pinfunction "DIN_4-DIN") (pintype "input"))
    )
    (net (code "216") (name "Net-(L210-DOUT)") (class "Default")
      (node (ref "L210") (pin "2-DOUT") (pinfunction "DOUT_2-DOUT") (pintype "output"))
      (node (ref "L211") (pin "4-DIN") (pinfunction "DIN_4-DIN") (pintype "input"))
    )
    (net (code "217") (name "Net-(L211-DOUT)") (class "Default")
      (node (ref "L211") (pin "2-DOUT") (pinfunction "DOUT_2-DOUT") (pintype "output"))
      (node (ref "L212") (pin "4-DIN") (pinfunction "DIN_4-DIN") (pintype "input"))
    )
    (net (code "218") (name "Net-(L212-DOUT)") (class "Default")
      (node (ref "L212") (pin "2-DOUT") (pinfunction "DOUT_2-DOUT") (pintype "output"))
      (node (ref "L213") (pin "4-DIN") (pinfunction "DIN_4-DIN") (pintype "input"))
    )
    (net (code "219") (name "Net-(L213-DOUT)") (class "Default")
      (node (ref "L213") (pin "2-DOUT") (pinfunction "DOUT_2-DOUT") (pintype "output"))
      (node (ref "L214") (pin "4-DIN") (pinfunction "DIN_4-DIN") (pintype "input"))
    )
    (net (code "220") (name "Net-(L214-DOUT)") (class "Default")
      (node (ref "L214") (pin "2-DOUT") (pinfunction "DOUT_2-DOUT") (pintype "output"))
      (node (ref "L215") (pin "4-DIN") (pinfunction "DIN_4-DIN") (pintype "input"))
    )
    (net (code "221") (name "Net-(L215-DOUT)") (class "Default")
      (node (ref "L215") (pin "2-DOUT") (pinfunction "DOUT_2-DOUT") (pintype "output"))
      (node (ref "L216") (pin "4-DIN") (pinfunction "DIN_4-DIN") (pintype "input"))
    )
    (net (code "222") (name "Net-(L216-DOUT)") (class "Default")
      (node (ref "L216") (pin "2-DOUT") (pinfunction "DOUT_2-DOUT") (pintype "output"))
      (node (ref "L217") (pin "4-DIN") (pinfunction "DIN_4-DIN") (pintype "input"))
    )
    (net (code "223") (name "Net-(L217-DOUT)") (class "Default")
      (node (ref "L217") (pin "2-DOUT") (pinfunction "DOUT_2-DOUT") (pintype "output"))
      (node (ref "L218") (pin "4-DIN") (pinfunction "DIN_4-DIN") (pintype "input"))
    )
    (net (code "224") (name "Net-(L218-DOUT)") (class "Default")
      (node (ref "L218") (pin "2-DOUT") (pinfunction "DOUT_2-DOUT") (pintype "output"))
      (node (ref "L219") (pin "4-DIN") (pinfunction "DIN_4-DIN") (pintype "input"))
    )
    (net (code "225") (name "Net-(L219-DOUT)") (class "Default")
      (node (ref "L219") (pin "2-DOUT") (pinfunction "DOUT_2-DOUT") (pintype "output"))
      (node (ref "L220") (pin "4-DIN") (pinfunction "DIN_4-DIN") (pintype "input"))
    )
    (net (code "226") (name "Net-(L220-DOUT)") (class "Default")
      (node (ref "L220") (pin "2-DOUT") (pinfunction "DOUT_2-DOUT") (pintype "output"))
      (node (ref "L221") (pin "4-DIN") (pinfunction "DIN_4-DIN") (pintype "input"))
    )
    (net (code "227") (name "Net-(L221-DOUT)") (class "Default")
      (node (ref "L221") (pin "2-DOUT") (pinfunction "DOUT_2-DOUT") (pintype "output"))
      (node (ref "L222") (pin "4-DIN") (pinfunction "DIN_4-DIN") (pintype "input"))
    )
    (net (code "228") (name "Net-(L222-DOUT)") (class "Default")
      (node (ref "L222") (pin "2-DOUT") (pinfunction "DOUT_2-DOUT") (pintype "output"))
      (node (ref "L223") (pin "4-DIN") (pinfunction "DIN_4-DIN") (pintype "input"))
    )
    (net (code "229") (name "Net-(L223-DOUT)") (class "Default")
      (node (ref "L223") (pin "2-DOUT") (pinfunction "DOUT_2-DOUT") (pintype "output"))
      (node (ref "L224") (pin "4-DIN") (pinfunction "DIN_4-DIN") (pintype "input"))
    )
    (net (code "230") (name "Net-(L224-DOUT)") (class "Default")
      (node (ref "L224") (pin "2-DOUT") (pinfunction "DOUT_2-DOUT") (pintype "output"))
      (node (ref "L225") (pin "4-DIN") (pinfunction "DIN_4-DIN") (pintype "input"))
    )
    (net (code "231") (name "Net-(L225-DOUT)") (class "Default")
      (node (ref "L225") (pin "2-DOUT") (pinfunction "DOUT_2-DOUT") (pintype "output"))
      (node (ref "L226") (pin "4-DIN") (pinfunction "DIN_4-DIN") (pintype "input"))
    )
    (net (code "232") (name "Net-(L226-DOUT)") (class "Default")
      (node (ref "L226") (pin "2-DOUT") (pinfunction "DOUT_2-DOUT") (pintype "output"))
      (node (ref "L227") (pin "4-DIN") (pinfunction "DIN_4-DIN") (pintype "input"))
    )
    (net (code "233") (name "Net-(L227-DOUT)") (class "Default")
      (node (ref "L227") (pin "2-DOUT") (pinfunction "DOUT_2-DOUT") (pintype "output"))
      (node (ref "L228") (pin "4-DIN") (pinfunction "DIN_4-DIN") (pintype "input"))
    )
    (net (code "234") (name "Net-(L228-DOUT)") (class "Default")
      (node (ref "L228") (pin "2-DOUT") (pinfunction "DOUT_2-DOUT") (pintype "output"))
      (node (ref "L229") (pin "4-DIN") (pinfunction "DIN_4-DIN") (pintype "input"))
    )
    (net (code "235") (name "Net-(L229-DOUT)") (class "Default")
      (node (ref "L229") (pin "2-DOUT") (pinfunction "DOUT_2-DOUT") (pintype "output"))
      (node (ref "L230") (pin "4-DIN") (pinfunction "DIN_4-DIN") (pintype "input"))
    )
    (net (code "236") (name "Net-(L230-DOUT)") (class "Default")
      (node (ref "L230") (pin "2-DOUT") (pinfunction "DOUT_2-DOUT") (pintype "output"))
      (node (ref "L231") (pin "4-DIN") (pinfunction "DIN_4-DIN") (pintype "input"))
    )
    (net (code "237") (name "Net-(L231-DOUT)") (class "Default")
      (node (ref "L231") (pin "2-DOUT") (pinfunction "DOUT_2-DOUT") (pintype "output"))
      (node (ref "L232") (pin "4-DIN") (pinfunction "DIN_4-DIN") (pintype "input"))
    )
    (net (code "238") (name "Net-(L232-DOUT)") (class "Default")
      (node (ref "L232") (pin "2-DOUT") (pinfunction "DOUT_2-DOUT") (pintype "output"))
      (node (ref "L233") (pin "4-DIN") (pinfunction "DIN_4-DIN") (pintype "input"))
    )
    (net (code "239") (name "Net-(L233-DOUT)") (class "Default")
      (node (ref "L233") (pin "2-DOUT") (pinfunction "DOUT_2-DOUT") (pintype "output"))
      (node (ref "L234") (pin "4-DIN") (pinfunction "DIN_4-DIN") (pintype "input"))
    )
    (net (code "240") (name "Net-(L234-DOUT)") (class "Default")
      (node (ref "L234") (pin "2-DOUT") (pinfunction "DOUT_2-DOUT") (pintype "output"))
      (node (ref "L235") (pin "4-DIN") (pinfunction "DIN_4-DIN") (pintype "input"))
    )
    (net (code "241") (name "Net-(L235-DOUT)") (class "Default")
      (node (ref "L235") (pin "2-DOUT") (pinfunction "DOUT_2-DOUT") (pintype "output"))
      (node (ref "L236") (pin "4-DIN") (pinfunction "DIN_4-DIN") (pintype "input"))
    )
    (net (code "242") (name "Net-(L236-DOUT)") (class "Default")
      (node (ref "L236") (pin "2-DOUT") (pinfunction "DOUT_2-DOUT") (pintype "output"))
      (node (ref "L237") (pin "4-DIN") (pinfunction "DIN_4-DIN") (pintype "input"))
    )
    (net (code "243") (name "Net-(L237-DOUT)") (class "Default")
      (node (ref "L237") (pin "2-DOUT") (pinfunction "DOUT_2-DOUT") (pintype "output"))
      (node (ref "L238") (pin "4-DIN") (pinfunction "DIN_4-DIN") (pintype "input"))
    )
    (net (code "244") (name "Net-(L238-DOUT)") (class "Default")
      (node (ref "L238") (pin "2-DOUT") (pinfunction "DOUT_2-DOUT") (pintype "output"))
      (node (ref "L239") (pin "4-DIN") (pinfunction "DIN_4-DIN") (pintype "input"))
    )
    (net (code "245") (name "Net-(L239-DOUT)") (class "Default")
      (node (ref "L239") (pin "2-DOUT") (pinfunction "DOUT_2-DOUT") (pintype "output"))
      (node (ref "L240") (pin "4-DIN") (pinfunction "DIN_4-DIN") (pintype "input"))
    )
    (net (code "246") (name "Net-(L240-DOUT)") (class "Default")
      (node (ref "L240") (pin "2-DOUT") (pinfunction "DOUT_2-DOUT") (pintype "output"))
      (node (ref "L241") (pin "4-DIN") (pinfunction "DIN_4-DIN") (pintype "input"))
    )
    (net (code "247") (name "Net-(L241-DOUT)") (class "Default")
      (node (ref "L241") (pin "2-DOUT") (pinfunction "DOUT_2-DOUT") (pintype "output"))
      (node (ref "L242") (pin "4-DIN") (pinfunction "DIN_4-DIN") (pintype "input"))
    )
    (net (code "248") (name "Net-(L242-DOUT)") (class "Default")
      (node (ref "L242") (pin "2-DOUT") (pinfunction "DOUT_2-DOUT") (pintype "output"))
      (node (ref "L243") (pin "4-DIN") (pinfunction "DIN_4-DIN") (pintype "input"))
    )
    (net (code "249") (name "Net-(L243-DOUT)") (class "Default")
      (node (ref "L243") (pin "2-DOUT") (pinfunction "DOUT_2-DOUT") (pintype "output"))
      (node (ref "L244") (pin "4-DIN") (pinfunction "DIN_4-DIN") (pintype "input"))
    )
    (net (code "250") (name "Net-(L244-DOUT)") (class "Default")
      (node (ref "L244") (pin "2-DOUT") (pinfunction "DOUT_2-DOUT") (pintype "output"))
      (node (ref "L245") (pin "4-DIN") (pinfunction "DIN_4-DIN") (pintype "input"))
    )
    (net (code "251") (name "Net-(L245-DOUT)") (class "Default")
      (node (ref "L245") (pin "2-DOUT") (pinfunction "DOUT_2-DOUT") (pintype "output"))
      (node (ref "L246") (pin "4-DIN") (pinfunction "DIN_4-DIN") (pintype "input"))
    )
    (net (code "252") (name "Net-(L246-DOUT)") (class "Default")
      (node (ref "L246") (pin "2-DOUT") (pinfunction "DOUT_2-DOUT") (pintype "output"))
      (node (ref "L247") (pin "4-DIN") (pinfunction "DIN_4-DIN") (pintype "input"))
    )
    (net (code "253") (name "Net-(L247-DOUT)") (class "Default")
      (node (ref "L247") (pin "2-DOUT") (pinfunction "DOUT_2-DOUT") (pintype "output"))
      (node (ref "L248") (pin "4-DIN") (pinfunction "DIN_4-DIN") (pintype "input"))
    )
    (net (code "254") (name "Net-(L248-DOUT)") (class "Default")
      (node (ref "L248") (pin "2-DOUT") (pinfunction "DOUT_2-DOUT") (pintype "output"))
      (node (ref "L249") (pin "4-DIN") (pinfunction "DIN_4-DIN") (pintype "input"))
    )
    (net (code "255") (name "Net-(L249-DOUT)") (class "Default")
      (node (ref "L249") (pin "2-DOUT") (pinfunction "DOUT_2-DOUT") (pintype "output"))
      (node (ref "L250") (pin "4-DIN") (pinfunction "DIN_4-DIN") (pintype "input"))
    )
    (net (code "256") (name "Net-(L250-DOUT)") (class "Default")
      (node (ref "L250") (pin "2-DOUT") (pinfunction "DOUT_2-DOUT") (pintype "output"))
      (node (ref "L251") (pin "4-DIN") (pinfunction "DIN_4-DIN") (pintype "input"))
    )
    (net (code "257") (name "Net-(L251-DOUT)") (class "Default")
      (node (ref "L251") (pin "2-DOUT") (pinfunction "DOUT_2-DOUT") (pintype "output"))
      (node (ref "L252") (pin "4-DIN") (pinfunction "DIN_4-DIN") (pintype "input"))
    )
    (net (code "258") (name "Net-(L252-DOUT)") (class "Default")
      (node (ref "L252") (pin "2-DOUT") (pinfunction "DOUT_2-DOUT") (pintype "output"))
      (node (ref "L253") (pin "4-DIN") (pinfunction "DIN_4-DIN") (pintype "input"))
    )
    (net (code "259") (name "Net-(L253-DOUT)") (class "Default")
      (node (ref "L253") (pin "2-DOUT") (pinfunction "DOUT_2-DOUT") (pintype "output"))
      (node (ref "L254") (pin "4-DIN") (pinfunction "DIN_4-DIN") (pintype "input"))
    )
    (net (code "260") (name "Net-(L254-DOUT)") (class "Default")
      (node (ref "L254") (pin "2-DOUT") (pinfunction "DOUT_2-DOUT") (pintype "output"))
      (node (ref "L255") (pin "4-DIN") (pinfunction "DIN_4-DIN") (pintype "input"))
    )
    (net (code "261") (name "Net-(L255-DOUT)") (class "Default")
      (node (ref "L255") (pin "2-DOUT") (pinfunction "DOUT_2-DOUT") (pintype "output"))
      (node (ref "L256") (pin "4-DIN") (pinfunction "DIN_4-DIN") (pintype "input"))
    )
    (net (code "262") (name "VCC") (class "Default")
      (node (ref "C1") (pin "1") (pinfunction "1_1") (pintype "passive"))
      (node (ref "C10") (pin "1") (pinfunction "1_1") (pintype "passive"))
      (node (ref "C100") (pin "1") (pinfunction "1_1") (pintype "passive"))
      (node (ref "C101") (pin "1") (pinfunction "1_1") (pintype "passive"))
      (node (ref "C102") (pin "1") (pinfunction "1_1") (pintype "passive"))
      (node (ref "C103") (pin "1") (pinfunction "1_1") (pintype "passive"))
      (node (ref "C104") (pin "1") (pinfunction "1_1") (pintype "passive"))
      (node (ref "C105") (pin "1") (pinfunction "1_1") (pintype "passive"))
      (node (ref "C106") (pin "1") (pinfunction "1_1") (pintype "passive"))
      (node (ref "C107") (pin "1") (pinfunction "1_1") (pintype "passive"))
      (node (ref "C108") (pin "1") (pinfunction "1_1") (pintype "passive"))
      (node (ref "C109") (pin "1") (pinfunction "1_1") (pintype "passive"))
      (node (ref "C11") (pin "1") (pinfunction "1_1") (pintype "passive"))
      (node (ref "C110") (pin "1") (pinfunction "1_1") (pintype "passive"))
      (node (ref "C111") (pin "1") (pinfunction "1_1") (pintype "passive"))
      (node (ref "C112") (pin "1") (pinfunction "1_1") (pintype "passive"))
      (node (ref "C113") (pin "1") (pinfunction "1_1") (pintype "passive"))
      (node (ref "C114") (pin "1") (pinfunction "1_1") (pintype "passive"))
      (node (ref "C115") (pin "1") (pinfunction "1_1") (pintype "passive"))
      (node (ref "C116") (pin "1") (pinfunction "1_1") (pintype "passive"))
      (node (ref "C117") (pin "1") (pinfunction "1_1") (pintype "passive"))
      (node (ref "C118") (pin "1") (pinfunction "1_1") (pintype "passive"))
      (node (ref "C119") (pin "1") (pinfunction "1_1") (pintype "passive"))
      (node (ref "C12") (pin "1") (pinfunction "1_1") (pintype "passive"))
      (node (ref "C120") (pin "1") (pinfunction "1_1") (pintype "passive"))
      (node (ref "C121") (pin "1") (pinfunction "1_1") (pintype "passive"))
      (node (ref "C122") (pin "1") (pinfunction "1_1") (pintype "passive"))
      (node (ref "C123") (pin "1") (pinfunction "1_1") (pintype "passive"))
      (node (ref "C124") (pin "1") (pinfunction "1_1") (pintype "passive"))
      (node (ref "C125") (pin "1") (pinfunction "1_1") (pintype "passive"))
      (node (ref "C126") (pin "1") (pinfunction "1_1") (pintype "passive"))
      (node (ref "C127") (pin "1") (pinfunction "1_1") (pintype "passive"))
      (node (ref "C128") (pin "1") (pinfunction "1_1") (pintype "passive"))
      (node (ref "C129") (pin "1") (pinfunction "1_1") (pintype "passive"))
      (node (ref "C13") (pin "1") (pinfunction "1_1") (pintype "passive"))
      (node (ref "C130") (pin "1") (pinfunction "1_1") (pintype "passive"))
      (node (ref "C131") (pin "1") (pinfunction "1_1") (pintype "passive"))
      (node (ref "C132") (pin "1") (pinfunction "1_1") (pintype "passive"))
      (node (ref "C133") (pin "1") (pinfunction "1_1") (pintype "passive"))
      (node (ref "C134") (pin "1") (pinfunction "1_1") (pintype "passive"))
      (node (ref "C135") (pin "1") (pinfunction "1_1") (pintype "passive"))
      (node (ref "C136") (pin "1") (pinfunction "1_1") (pintype "passive"))
      (node (ref "C137") (pin "1") (pinfunction "1_1") (pintype "passive"))
      (node (ref "C138") (pin "1") (pinfunction "1_1") (pintype "passive"))
      (node (ref "C139") (pin "1") (pinfunction "1_1") (pintype "passive"))
      (node (ref "C14") (pin "1") (pinfunction "1_1") (pintype "passive"))
      (node (ref "C140") (pin "1") (pinfunction "1_1") (pintype "passive"))
      (node (ref "C141") (pin "1") (pinfunction "1_1") (pintype "passive"))
      (node (ref "C142") (pin "1") (pinfunction "1_1") (pintype "passive"))
      (node (ref "C143") (pin "1") (pinfunction "1_1") (pintype "passive"))
      (node (ref "C144") (pin "1") (pinfunction "1_1") (pintype "passive"))
      (node (ref "C145") (pin "1") (pinfunction "1_1") (pintype "passive"))
      (node (ref "C146") (pin "1") (pinfunction "1_1") (pintype "passive"))
      (node (ref "C147") (pin "1") (pinfunction "1_1") (pintype "passive"))
      (node (ref "C148") (pin "1") (pinfunction "1_1") (pintype "passive"))
      (node (ref "C149") (pin "1") (pinfunction "1_1") (pintype "passive"))
      (node (ref "C15") (pin "1") (pinfunction "1_1") (pintype "passive"))
      (node (ref "C150") (pin "1") (pinfunction "1_1") (pintype "passive"))
      (node (ref "C151") (pin "1") (pinfunction "1_1") (pintype "passive"))
      (node (ref "C152") (pin "1") (pinfunction "1_1") (pintype "passive"))
      (node (ref "C153") (pin "1") (pinfunction "1_1") (pintype "passive"))
      (node (ref "C154") (pin "1") (pinfunction "1_1") (pintype "passive"))
      (node (ref "C155") (pin "1") (pinfunction "1_1") (pintype "passive"))
      (node (ref "C156") (pin "1") (pinfunction "1_1") (pintype "passive"))
      (node (ref "C157") (pin "1") (pinfunction "1_1") (pintype "passive"))
      (node (ref "C158") (pin "1") (pinfunction "1_1") (pintype "passive"))
      (node (ref "C159") (pin "1") (pinfunction "1_1") (pintype "passive"))
      (node (ref "C16") (pin "1") (pinfunction "1_1") (pintype "passive"))
      (node (ref "C160") (pin "1") (pinfunction "1_1") (pintype "passive"))
      (node (ref "C161") (pin "1") (pinfunction "1_1") (pintype "passive"))
      (node (ref "C162") (pin "1") (pinfunction "1_1") (pintype "passive"))
      (node (ref "C163") (pin "1") (pinfunction "1_1") (pintype "passive"))
      (node (ref "C164") (pin "1") (pinfunction "1_1") (pintype "passive"))
      (node (ref "C165") (pin "1") (pinfunction "1_1") (pintype "passive"))
      (node (ref "C166") (pin "1") (pinfunction "1_1") (pintype "passive"))
      (node (ref "C167") (pin "1") (pinfunction "1_1") (pintype "passive"))
      (node (ref "C168") (pin "1") (pinfunction "1_1") (pintype "passive"))
      (node (ref "C169") (pin "1") (pinfunction "1_1") (pintype "passive"))
      (node (ref "C17") (pin "1") (pinfunction "1_1") (pintype "passive"))
      (node (ref "C170") (pin "1") (pinfunction "1_1") (pintype "passive"))
      (node (ref "C171") (pin "1") (pinfunction "1_1") (pintype "passive"))
      (node (ref "C172") (pin "1") (pinfunction "1_1") (pintype "passive"))
      (node (ref "C173") (pin "1") (pinfunction "1_1") (pintype "passive"))
      (node (ref "C174") (pin "1") (pinfunction "1_1") (pintype "passive"))
      (node (ref "C175") (pin "1") (pinfunction "1_1") (pintype "passive"))
      (node (ref "C176") (pin "1") (pinfunction "1_1") (pintype "passive"))
      (node (ref "C177") (pin "1") (pinfunction "1_1") (pintype "passive"))
      (node (ref "C178") (pin "1") (pinfunction "1_1") (pintype "passive"))
      (node (ref "C179") (pin "1") (pinfunction "1_1") (pintype "passive"))
      (node (ref "C18") (pin "1") (pinfunction "1_1") (pintype "passive"))
      (node (ref "C180") (pin "1") (pinfunction "1_1") (pintype "passive"))
      (node (ref "C181") (pin "1") (pinfunction "1_1") (pintype "passive"))
      (node (ref "C182") (pin "1") (pinfunction "1_1") (pintype "passive"))
      (node (ref "C183") (pin "1") (pinfunction "1_1") (pintype "passive"))
      (node (ref "C184") (pin "1") (pinfunction "1_1") (pintype "passive"))
      (node (ref "C185") (pin "1") (pinfunction "1_1") (pintype "passive"))
      (node (ref "C186") (pin "1") (pinfunction "1_1") (pintype "passive"))
      (node (ref "C187") (pin "1") (pinfunction "1_1") (pintype "passive"))
      (node (ref "C188") (pin "1") (pinfunction "1_1") (pintype "passive"))
      (node (ref "C189") (pin "1") (pinfunction "1_1") (pintype "passive"))
      (node (ref "C19") (pin "1") (pinfunction "1_1") (pintype "passive"))
      (node (ref "C190") (pin "1") (pinfunction "1_1") (pintype "passive"))
      (node (ref "C191") (pin "1") (pinfunction "1_1") (pintype "passive"))
      (node (ref "C192") (pin "1") (pinfunction "1_1") (pintype "passive"))
      (node (ref "C193") (pin "1") (pinfunction "1_1") (pintype "passive"))
      (node (ref "C194") (pin "1") (pinfunction "1_1") (pintype "passive"))
      (node (ref "C195") (pin "1") (pinfunction "1_1") (pintype "passive"))
      (node (ref "C196") (pin "1") (pinfunction "1_1") (pintype "passive"))
      (node (ref "C197") (pin "1") (pinfunction "1_1") (pintype "passive"))
      (node (ref "C198") (pin "1") (pinfunction "1_1") (pintype "passive"))
      (node (ref "C199") (pin "1") (pinfunction "1_1") (pintype "passive"))
      (node (ref "C2") (pin "1") (pinfunction "1_1") (pintype "passive"))
      (node (ref "C20") (pin "1") (pinfunction "1_1") (pintype "passive"))
      (node (ref "C200") (pin "1") (pinfunction "1_1") (pintype "passive"))
      (node (ref "C201") (pin "1") (pinfunction "1_1") (pintype "passive"))
      (node (ref "C202") (pin "1") (pinfunction "1_1") (pintype "passive"))
      (node (ref "C203") (pin "1") (pinfunction "1_1") (pintype "passive"))
      (node (ref "C204") (pin "1") (pinfunction "1_1") (pintype "passive"))
      (node (ref "C205") (pin "1") (pinfunction "1_1") (pintype "passive"))
      (node (ref "C206") (pin "1") (pinfunction "1_1") (pintype "passive"))
      (node (ref "C207") (pin "1") (pinfunction "1_1") (pintype "passive"))
      (node (ref "C208") (pin "1") (pinfunction "1_1") (pintype "passive"))
      (node (ref "C209") (pin "1") (pinfunction "1_1") (pintype "passive"))
      (node (ref "C21") (pin "1") (pinfunction "1_1") (pintype "passive"))
      (node (ref "C210") (pin "1") (pinfunction "1_1") (pintype "passive"))
      (node (ref "C211") (pin "1") (pinfunction "1_1") (pintype "passive"))
      (node (ref "C212") (pin "1") (pinfunction "1_1") (pintype "passive"))
      (node (ref "C213") (pin "1") (pinfunction "1_1") (pintype "passive"))
      (node (ref "C214") (pin "1") (pinfunction "1_1") (pintype "passive"))
      (node (ref "C215") (pin "1") (pinfunction "1_1") (pintype "passive"))
      (node (ref "C216") (pin "1") (pinfunction "1_1") (pintype "passive"))
      (node (ref "C217") (pin "1") (pinfunction "1_1") (pintype "passive"))
      (node (ref "C218") (pin "1") (pinfunction "1_1") (pintype "passive"))
      (node (ref "C219") (pin "1") (pinfunction "1_1") (pintype "passive"))
      (node (ref "C22") (pin "1") (pinfunction "1_1") (pintype "passive"))
      (node (ref "C220") (pin "1") (pinfunction "1_1") (pintype "passive"))
      (node (ref "C221") (pin "1") (pinfunction "1_1") (pintype "passive"))
      (node (ref "C222") (pin "1") (pinfunction "1_1") (pintype "passive"))
      (node (ref "C223") (pin "1") (pinfunction "1_1") (pintype "passive"))
      (node (ref "C224") (pin "1") (pinfunction "1_1") (pintype "passive"))
      (node (ref "C225") (pin "1") (pinfunction "1_1") (pintype "passive"))
      (node (ref "C226") (pin "1") (pinfunction "1_1") (pintype "passive"))
      (node (ref "C227") (pin "1") (pinfunction "1_1") (pintype "passive"))
      (node (ref "C228") (pin "1") (pinfunction "1_1") (pintype "passive"))
      (node (ref "C229") (pin "1") (pinfunction "1_1") (pintype "passive"))
      (node (ref "C23") (pin "1") (pinfunction "1_1") (pintype "passive"))
      (node (ref "C230") (pin "1") (pinfunction "1_1") (pintype "passive"))
      (node (ref "C231") (pin "1") (pinfunction "1_1") (pintype "passive"))
      (node (ref "C232") (pin "1") (pinfunction "1_1") (pintype "passive"))
      (node (ref "C233") (pin "1") (pinfunction "1_1") (pintype "passive"))
      (node (ref "C234") (pin "1") (pinfunction "1_1") (pintype "passive"))
      (node (ref "C235") (pin "1") (pinfunction "1_1") (pintype "passive"))
      (node (ref "C236") (pin "1") (pinfunction "1_1") (pintype "passive"))
      (node (ref "C237") (pin "1") (pinfunction "1_1") (pintype "passive"))
      (node (ref "C238") (pin "1") (pinfunction "1_1") (pintype "passive"))
      (node (ref "C239") (pin "1") (pinfunction "1_1") (pintype "passive"))
      (node (ref "C24") (pin "1") (pinfunction "1_1") (pintype "passive"))
      (node (ref "C240") (pin "1") (pinfunction "1_1") (pintype "passive"))
      (node (ref "C241") (pin "1") (pinfunction "1_1") (pintype "passive"))
      (node (ref "C242") (pin "1") (pinfunction "1_1") (pintype "passive"))
      (node (ref "C243") (pin "1") (pinfunction "1_1") (pintype "passive"))
      (node (ref "C244") (pin "1") (pinfunction "1_1") (pintype "passive"))
      (node (ref "C245") (pin "1") (pinfunction "1_1") (pintype "passive"))
      (node (ref "C246") (pin "1") (pinfunction "1_1") (pintype "passive"))
      (node (ref "C247") (pin "1") (pinfunction "1_1") (pintype "passive"))
      (node (ref "C248") (pin "1") (pinfunction "1_1") (pintype "passive"))
      (node (ref "C249") (pin "1") (pinfunction "1_1") (pintype "passive"))
      (node (ref "C25") (pin "1") (pinfunction "1_1") (pintype "passive"))
      (node (ref "C250") (pin "1") (pinfunction "1_1") (pintype "passive"))
      (node (ref "C251") (pin "1") (pinfunction "1_1") (pintype "passive"))
      (node (ref "C252") (pin "1") (pinfunction "1_1") (pintype "passive"))
      (node (ref "C253") (pin "1") (pinfunction "1_1") (pintype "passive"))
      (node (ref "C254") (pin "1") (pinfunction "1_1") (pintype "passive"))
      (node (ref "C255") (pin "1") (pinfunction "1_1") (pintype "passive"))
      (node (ref "C256") (pin "1") (pinfunction "1_1") (pintype "passive"))
      (node (ref "C26") (pin "1") (pinfunction "1_1") (pintype "passive"))
      (node (ref "C27") (pin "1") (pinfunction "1_1") (pintype "passive"))
      (node (ref "C28") (pin "1") (pinfunction "1_1") (pintype "passive"))
      (node (ref "C29") (pin "1") (pinfunction "1_1") (pintype "passive"))
      (node (ref "C3") (pin "1") (pinfunction "1_1") (pintype "passive"))
      (node (ref "C30") (pin "1") (pinfunction "1_1") (pintype "passive"))
      (node (ref "C31") (pin "1") (pinfunction "1_1") (pintype "passive"))
      (node (ref "C32") (pin "1") (pinfunction "1_1") (pintype "passive"))
      (node (ref "C33") (pin "1") (pinfunction "1_1") (pintype "passive"))
      (node (ref "C34") (pin "1") (pinfunction "1_1") (pintype "passive"))
      (node (ref "C35") (pin "1") (pinfunction "1_1") (pintype "passive"))
      (node (ref "C36") (pin "1") (pinfunction "1_1") (pintype "passive"))
      (node (ref "C37") (pin "1") (pinfunction "1_1") (pintype "passive"))
      (node (ref "C38") (pin "1") (pinfunction "1_1") (pintype "passive"))
      (node (ref "C39") (pin "1") (pinfunction "1_1") (pintype "passive"))
      (node (ref "C4") (pin "1") (pinfunction "1_1") (pintype "passive"))
      (node (ref "C40") (pin "1") (pinfunction "1_1") (pintype "passive"))
      (node (ref "C41") (pin "1") (pinfunction "1_1") (pintype "passive"))
      (node (ref "C42") (pin "1") (pinfunction "1_1") (pintype "passive"))
      (node (ref "C43") (pin "1") (pinfunction "1_1") (pintype "passive"))
      (node (ref "C44") (pin "1") (pinfunction "1_1") (pintype "passive"))
      (node (ref "C45") (pin "1") (pinfunction "1_1") (pintype "passive"))
      (node (ref "C46") (pin "1") (pinfunction "1_1") (pintype "passive"))
      (node (ref "C47") (pin "1") (pinfunction "1_1") (pintype "passive"))
      (node (ref "C48") (pin "1") (pinfunction "1_1") (pintype "passive"))
      (node (ref "C49") (pin "1") (pinfunction "1_1") (pintype "passive"))
      (node (ref "C5") (pin "1") (pinfunction "1_1") (pintype "passive"))
      (node (ref "C50") (pin "1") (pinfunction "1_1") (pintype "passive"))
      (node (ref "C51") (pin "1") (pinfunction "1_1") (pintype "passive"))
      (node (ref "C52") (pin "1") (pinfunction "1_1") (pintype "passive"))
      (node (ref "C53") (pin "1") (pinfunction "1_1") (pintype "passive"))
      (node (ref "C54") (pin "1") (pinfunction "1_1") (pintype "passive"))
      (node (ref "C55") (pin "1") (pinfunction "1_1") (pintype "passive"))
      (node (ref "C56") (pin "1") (pinfunction "1_1") (pintype "passive"))
      (node (ref "C57") (pin "1") (pinfunction "1_1") (pintype "passive"))
      (node (ref "C58") (pin "1") (pinfunction "1_1") (pintype "passive"))
      (node (ref "C59") (pin "1") (pinfunction "1_1") (pintype "passive"))
      (node (ref "C6") (pin "1") (pinfunction "1_1") (pintype "passive"))
      (node (ref "C60") (pin "1") (pinfunction "1_1") (pintype "passive"))
      (node (ref "C61") (pin "1") (pinfunction "1_1") (pintype "passive"))
      (node (ref "C62") (pin "1") (pinfunction "1_1") (pintype "passive"))
      (node (ref "C63") (pin "1") (pinfunction "1_1") (pintype "passive"))
      (node (ref "C64") (pin "1") (pinfunction "1_1") (pintype "passive"))
      (node (ref "C65") (pin "1") (pinfunction "1_1") (pintype "passive"))
      (node (ref "C66") (pin "1") (pinfunction "1_1") (pintype "passive"))
      (node (ref "C67") (pin "1") (pinfunction "1_1") (pintype "passive"))
      (node (ref "C68") (pin "1") (pinfunction "1_1") (pintype "passive"))
      (node (ref "C69") (pin "1") (pinfunction "1_1") (pintype "passive"))
      (node (ref "C7") (pin "1") (pinfunction "1_1") (pintype "passive"))
      (node (ref "C70") (pin "1") (pinfunction "1_1") (pintype "passive"))
      (node (ref "C71") (pin "1") (pinfunction "1_1") (pintype "passive"))
      (node (ref "C72") (pin "1") (pinfunction "1_1") (pintype "passive"))
      (node (ref "C73") (pin "1") (pinfunction "1_1") (pintype "passive"))
      (node (ref "C74") (pin "1") (pinfunction "1_1") (pintype "passive"))
      (node (ref "C75") (pin "1") (pinfunction "1_1") (pintype "passive"))
      (node (ref "C76") (pin "1") (pinfunction "1_1") (pintype "passive"))
      (node (ref "C77") (pin "1") (pinfunction "1_1") (pintype "passive"))
      (node (ref "C78") (pin "1") (pinfunction "1_1") (pintype "passive"))
      (node (ref "C79") (pin "1") (pinfunction "1_1") (pintype "passive"))
      (node (ref "C8") (pin "1") (pinfunction "1_1") (pintype "passive"))
      (node (ref "C80") (pin "1") (pinfunction "1_1") (pintype "passive"))
      (node (ref "C81") (pin "1") (pinfunction "1_1") (pintype "passive"))
      (node (ref "C82") (pin "1") (pinfunction "1_1") (pintype "passive"))
      (node (ref "C83") (pin "1") (pinfunction "1_1") (pintype "passive"))
      (node (ref "C84") (pin "1") (pinfunction "1_1") (pintype "passive"))
      (node (ref "C85") (pin "1") (pinfunction "1_1") (pintype "passive"))
      (node (ref "C86") (pin "1") (pinfunction "1_1") (pintype "passive"))
      (node (ref "C87") (pin "1") (pinfunction "1_1") (pintype "passive"))
      (node (ref "C88") (pin "1") (pinfunction "1_1") (pintype "passive"))
      (node (ref "C89") (pin "1") (pinfunction "1_1") (pintype "passive"))
      (node (ref "C9") (pin "1") (pinfunction "1_1") (pintype "passive"))
      (node (ref "C90") (pin "1") (pinfunction "1_1") (pintype "passive"))
      (node (ref "C91") (pin "1") (pinfunction "1_1") (pintype "passive"))
      (node (ref "C92") (pin "1") (pinfunction "1_1") (pintype "passive"))
      (node (ref "C93") (pin "1") (pinfunction "1_1") (pintype "passive"))
      (node (ref "C94") (pin "1") (pinfunction "1_1") (pintype "passive"))
      (node (ref "C95") (pin "1") (pinfunction "1_1") (pintype "passive"))
      (node (ref "C96") (pin "1") (pinfunction "1_1") (pintype "passive"))
      (node (ref "C97") (pin "1") (pinfunction "1_1") (pintype "passive"))
      (node (ref "C98") (pin "1") (pinfunction "1_1") (pintype "passive"))
      (node (ref "C99") (pin "1") (pinfunction "1_1") (pintype "passive"))
      (node (ref "JP1") (pin "1") (pinfunction "1_1") (pintype "passive"))
      (node (ref "L1") (pin "1-VDD") (pinfunction "VDD_1-VDD") (pintype "bidirectional"))
      (node (ref "L10") (pin "1-VDD") (pinfunction "VDD_1-VDD") (pintype "bidirectional"))
      (node (ref "L100") (pin "1-VDD") (pinfunction "VDD_1-VDD") (pintype "bidirectional"))
      (node (ref "L101") (pin "1-VDD") (pinfunction "VDD_1-VDD") (pintype "bidirectional"))
      (node (ref "L102") (pin "1-VDD") (pinfunction "VDD_1-VDD") (pintype "bidirectional"))
      (node (ref "L103") (pin "1-VDD") (pinfunction "VDD_1-VDD") (pintype "bidirectional"))
      (node (ref "L104") (pin "1-VDD") (pinfunction "VDD_1-VDD") (pintype "bidirectional"))
      (node (ref "L105") (pin "1-VDD") (pinfunction "VDD_1-VDD") (pintype "bidirectional"))
      (node (ref "L106") (pin "1-VDD") (pinfunction "VDD_1-VDD") (pintype "bidirectional"))
      (node (ref "L107") (pin "1-VDD") (pinfunction "VDD_1-VDD") (pintype "bidirectional"))
      (node (ref "L108") (pin "1-VDD") (pinfunction "VDD_1-VDD") (pintype "bidirectional"))
      (node (ref "L109") (pin "1-VDD") (pinfunction "VDD_1-VDD") (pintype "bidirectional"))
      (node (ref "L11") (pin "1-VDD") (pinfunction "VDD_1-VDD") (pintype "bidirectional"))
      (node (ref "L110") (pin "1-VDD") (pinfunction "VDD_1-VDD") (pintype "bidirectional"))
      (node (ref "L111") (pin "1-VDD") (pinfunction "VDD_1-VDD") (pintype "bidirectional"))
      (node (ref "L112") (pin "1-VDD") (pinfunction "VDD_1-VDD") (pintype "bidirectional"))
      (node (ref "L113") (pin "1-VDD") (pinfunction "VDD_1-VDD") (pintype "bidirectional"))
      (node (ref "L114") (pin "1-VDD") (pinfunction "VDD_1-VDD") (pintype "bidirectional"))
      (node (ref "L115") (pin "1-VDD") (pinfunction "VDD_1-VDD") (pintype "bidirectional"))
      (node (ref "L116") (pin "1-VDD") (pinfunction "VDD_1-VDD") (pintype "bidirectional"))
      (node (ref "L117") (pin "1-VDD") (pinfunction "VDD_1-VDD") (pintype "bidirectional"))
      (node (ref "L118") (pin "1-VDD") (pinfunction "VDD_1-VDD") (pintype "bidirectional"))
      (node (ref "L119") (pin "1-VDD") (pinfunction "VDD_1-VDD") (pintype "bidirectional"))
      (node (ref "L12") (pin "1-VDD") (pinfunction "VDD_1-VDD") (pintype "bidirectional"))
      (node (ref "L120") (pin "1-VDD") (pinfunction "VDD_1-VDD") (pintype "bidirectional"))
      (node (ref "L121") (pin "1-VDD") (pinfunction "VDD_1-VDD") (pintype "bidirectional"))
      (node (ref "L122") (pin "1-VDD") (pinfunction "VDD_1-VDD") (pintype "bidirectional"))
      (node (ref "L123") (pin "1-VDD") (pinfunction "VDD_1-VDD") (pintype "bidirectional"))
      (node (ref "L124") (pin "1-VDD") (pinfunction "VDD_1-VDD") (pintype "bidirectional"))
      (node (ref "L125") (pin "1-VDD") (pinfunction "VDD_1-VDD") (pintype "bidirectional"))
      (node (ref "L126") (pin "1-VDD") (pinfunction "VDD_1-VDD") (pintype "bidirectional"))
      (node (ref "L127") (pin "1-VDD") (pinfunction "VDD_1-VDD") (pintype "bidirectional"))
      (node (ref "L128") (pin "1-VDD") (pinfunction "VDD_1-VDD") (pintype "bidirectional"))
      (node (ref "L129") (pin "1-VDD") (pinfunction "VDD_1-VDD") (pintype "bidirectional"))
      (node (ref "L13") (pin "1-VDD") (pinfunction "VDD_1-VDD") (pintype "bidirectional"))
      (node (ref "L130") (pin "1-VDD") (pinfunction "VDD_1-VDD") (pintype "bidirectional"))
      (node (ref "L131") (pin "1-VDD") (pinfunction "VDD_1-VDD") (pintype "bidirectional"))
      (node (ref "L132") (pin "1-VDD") (pinfunction "VDD_1-VDD") (pintype "bidirectional"))
      (node (ref "L133") (pin "1-VDD") (pinfunction "VDD_1-VDD") (pintype "bidirectional"))
      (node (ref "L134") (pin "1-VDD") (pinfunction "VDD_1-VDD") (pintype "bidirectional"))
      (node (ref "L135") (pin "1-VDD") (pinfunction "VDD_1-VDD") (pintype "bidirectional"))
      (node (ref "L136") (pin "1-VDD") (pinfunction "VDD_1-VDD") (pintype "bidirectional"))
      (node (ref "L137") (pin "1-VDD") (pinfunction "VDD_1-VDD") (pintype "bidirectional"))
      (node (ref "L138") (pin "1-VDD") (pinfunction "VDD_1-VDD") (pintype "bidirectional"))
      (node (ref "L139") (pin "1-VDD") (pinfunction "VDD_1-VDD") (pintype "bidirectional"))
      (node (ref "L14") (pin "1-VDD") (pinfunction "VDD_1-VDD") (pintype "bidirectional"))
      (node (ref "L140") (pin "1-VDD") (pinfunction "VDD_1-VDD") (pintype "bidirectional"))
      (node (ref "L141") (pin "1-VDD") (pinfunction "VDD_1-VDD") (pintype "bidirectional"))
      (node (ref "L142") (pin "1-VDD") (pinfunction "VDD_1-VDD") (pintype "bidirectional"))
      (node (ref "L143") (pin "1-VDD") (pinfunction "VDD_1-VDD") (pintype "bidirectional"))
      (node (ref "L144") (pin "1-VDD") (pinfunction "VDD_1-VDD") (pintype "bidirectional"))
      (node (ref "L145") (pin "1-VDD") (pinfunction "VDD_1-VDD") (pintype "bidirectional"))
      (node (ref "L146") (pin "1-VDD") (pinfunction "VDD_1-VDD") (pintype "bidirectional"))
      (node (ref "L147") (pin "1-VDD") (pinfunction "VDD_1-VDD") (pintype "bidirectional"))
      (node (ref "L148") (pin "1-VDD") (pinfunction "VDD_1-VDD") (pintype "bidirectional"))
      (node (ref "L149") (pin "1-VDD") (pinfunction "VDD_1-VDD") (pintype "bidirectional"))
      (node (ref "L15") (pin "1-VDD") (pinfunction "VDD_1-VDD") (pintype "bidirectional"))
      (node (ref "L150") (pin "1-VDD") (pinfunction "VDD_1-VDD") (pintype "bidirectional"))
      (node (ref "L151") (pin "1-VDD") (pinfunction "VDD_1-VDD") (pintype "bidirectional"))
      (node (ref "L152") (pin "1-VDD") (pinfunction "VDD_1-VDD") (pintype "bidirectional"))
      (node (ref "L153") (pin "1-VDD") (pinfunction "VDD_1-VDD") (pintype "bidirectional"))
      (node (ref "L154") (pin "1-VDD") (pinfunction "VDD_1-VDD") (pintype "bidirectional"))
      (node (ref "L155") (pin "1-VDD") (pinfunction "VDD_1-VDD") (pintype "bidirectional"))
      (node (ref "L156") (pin "1-VDD") (pinfunction "VDD_1-VDD") (pintype "bidirectional"))
      (node (ref "L157") (pin "1-VDD") (pinfunction "VDD_1-VDD") (pintype "bidirectional"))
      (node (ref "L158") (pin "1-VDD") (pinfunction "VDD_1-VDD") (pintype "bidirectional"))
      (node (ref "L159") (pin "1-VDD") (pinfunction "VDD_1-VDD") (pintype "bidirectional"))
      (node (ref "L16") (pin "1-VDD") (pinfunction "VDD_1-VDD") (pintype "bidirectional"))
      (node (ref "L160") (pin "1-VDD") (pinfunction "VDD_1-VDD") (pintype "bidirectional"))
      (node (ref "L161") (pin "1-VDD") (pinfunction "VDD_1-VDD") (pintype "bidirectional"))
      (node (ref "L162") (pin "1-VDD") (pinfunction "VDD_1-VDD") (pintype "bidirectional"))
      (node (ref "L163") (pin "1-VDD") (pinfunction "VDD_1-VDD") (pintype "bidirectional"))
      (node (ref "L164") (pin "1-VDD") (pinfunction "VDD_1-VDD") (pintype "bidirectional"))
      (node (ref "L165") (pin "1-VDD") (pinfunction "VDD_1-VDD") (pintype "bidirectional"))
      (node (ref "L166") (pin "1-VDD") (pinfunction "VDD_1-VDD") (pintype "bidirectional"))
      (node (ref "L167") (pin "1-VDD") (pinfunction "VDD_1-VDD") (pintype "bidirectional"))
      (node (ref "L168") (pin "1-VDD") (pinfunction "VDD_1-VDD") (pintype "bidirectional"))
      (node (ref "L169") (pin "1-VDD") (pinfunction "VDD_1-VDD") (pintype "bidirectional"))
      (node (ref "L17") (pin "1-VDD") (pinfunction "VDD_1-VDD") (pintype "bidirectional"))
      (node (ref "L170") (pin "1-VDD") (pinfunction "VDD_1-VDD") (pintype "bidirectional"))
      (node (ref "L171") (pin "1-VDD") (pinfunction "VDD_1-VDD") (pintype "bidirectional"))
      (node (ref "L172") (pin "1-VDD") (pinfunction "VDD_1-VDD") (pintype "bidirectional"))
      (node (ref "L173") (pin "1-VDD") (pinfunction "VDD_1-VDD") (pintype "bidirectional"))
      (node (ref "L174") (pin "1-VDD") (pinfunction "VDD_1-VDD") (pintype "bidirectional"))
      (node (ref "L175") (pin "1-VDD") (pinfunction "VDD_1-VDD") (pintype "bidirectional"))
      (node (ref "L176") (pin "1-VDD") (pinfunction "VDD_1-VDD") (pintype "bidirectional"))
      (node (ref "L177") (pin "1-VDD") (pinfunction "VDD_1-VDD") (pintype "bidirectional"))
      (node (ref "L178") (pin "1-VDD") (pinfunction "VDD_1-VDD") (pintype "bidirectional"))
      (node (ref "L179") (pin "1-VDD") (pinfunction "VDD_1-VDD") (pintype "bidirectional"))
      (node (ref "L18") (pin "1-VDD") (pinfunction "VDD_1-VDD") (pintype "bidirectional"))
      (node (ref "L180") (pin "1-VDD") (pinfunction "VDD_1-VDD") (pintype "bidirectional"))
      (node (ref "L181") (pin "1-VDD") (pinfunction "VDD_1-VDD") (pintype "bidirectional"))
      (node (ref "L182") (pin "1-VDD") (pinfunction "VDD_1-VDD") (pintype "bidirectional"))
      (node (ref "L183") (pin "1-VDD") (pinfunction "VDD_1-VDD") (pintype "bidirectional"))
      (node (ref "L184") (pin "1-VDD") (pinfunction "VDD_1-VDD") (pintype "bidirectional"))
      (node (ref "L185") (pin "1-VDD") (pinfunction "VDD_1-VDD") (pintype "bidirectional"))
      (node (ref "L186") (pin "1-VDD") (pinfunction "VDD_1-VDD") (pintype "bidirectional"))
      (node (ref "L187") (pin "1-VDD") (pinfunction "VDD_1-VDD") (pintype "bidirectional"))
      (node (ref "L188") (pin "1-VDD") (pinfunction "VDD_1-VDD") (pintype "bidirectional"))
      (node (ref "L189") (pin "1-VDD") (pinfunction "VDD_1-VDD") (pintype "bidirectional"))
      (node (ref "L19") (pin "1-VDD") (pinfunction "VDD_1-VDD") (pintype "bidirectional"))
      (node (ref "L190") (pin "1-VDD") (pinfunction "VDD_1-VDD") (pintype "bidirectional"))
      (node (ref "L191") (pin "1-VDD") (pinfunction "VDD_1-VDD") (pintype "bidirectional"))
      (node (ref "L192") (pin "1-VDD") (pinfunction "VDD_1-VDD") (pintype "bidirectional"))
      (node (ref "L193") (pin "1-VDD") (pinfunction "VDD_1-VDD") (pintype "bidirectional"))
      (node (ref "L194") (pin "1-VDD") (pinfunction "VDD_1-VDD") (pintype "bidirectional"))
      (node (ref "L195") (pin "1-VDD") (pinfunction "VDD_1-VDD") (pintype "bidirectional"))
      (node (ref "L196") (pin "1-VDD") (pinfunction "VDD_1-VDD") (pintype "bidirectional"))
      (node (ref "L197") (pin "1-VDD") (pinfunction "VDD_1-VDD") (pintype "bidirectional"))
      (node (ref "L198") (pin "1-VDD") (pinfunction "VDD_1-VDD") (pintype "bidirectional"))
      (node (ref "L199") (pin "1-VDD") (pinfunction "VDD_1-VDD") (pintype "bidirectional"))
      (node (ref "L2") (pin "1-VDD") (pinfunction "VDD_1-VDD") (pintype "bidirectional"))
      (node (ref "L20") (pin "1-VDD") (pinfunction "VDD_1-VDD") (pintype "bidirectional"))
      (node (ref "L200") (pin "1-VDD") (pinfunction "VDD_1-VDD") (pintype "bidirectional"))
      (node (ref "L201") (pin "1-VDD") (pinfunction "VDD_1-VDD") (pintype "bidirectional"))
      (node (ref "L202") (pin "1-VDD") (pinfunction "VDD_1-VDD") (pintype "bidirectional"))
      (node (ref "L203") (pin "1-VDD") (pinfunction "VDD_1-VDD") (pintype "bidirectional"))
      (node (ref "L204") (pin "1-VDD") (pinfunction "VDD_1-VDD") (pintype "bidirectional"))
      (node (ref "L205") (pin "1-VDD") (pinfunction "VDD_1-VDD") (pintype "bidirectional"))
      (node (ref "L206") (pin "1-VDD") (pinfunction "VDD_1-VDD") (pintype "bidirectional"))
      (node (ref "L207") (pin "1-VDD") (pinfunction "VDD_1-VDD") (pintype "bidirectional"))
      (node (ref "L208") (pin "1-VDD") (pinfunction "VDD_1-VDD") (pintype "bidirectional"))
      (node (ref "L209") (pin "1-VDD") (pinfunction "VDD_1-VDD") (pintype "bidirectional"))
      (node (ref "L21") (pin "1-VDD") (pinfunction "VDD_1-VDD") (pintype "bidirectional"))
      (node (ref "L210") (pin "1-VDD") (pinfunction "VDD_1-VDD") (pintype "bidirectional"))
      (node (ref "L211") (pin "1-VDD") (pinfunction "VDD_1-VDD") (pintype "bidirectional"))
      (node (ref "L212") (pin "1-VDD") (pinfunction "VDD_1-VDD") (pintype "bidirectional"))
      (node (ref "L213") (pin "1-VDD") (pinfunction "VDD_1-VDD") (pintype "bidirectional"))
      (node (ref "L214") (pin "1-VDD") (pinfunction "VDD_1-VDD") (pintype "bidirectional"))
      (node (ref "L215") (pin "1-VDD") (pinfunction "VDD_1-VDD") (pintype "bidirectional"))
      (node (ref "L216") (pin "1-VDD") (pinfunction "VDD_1-VDD") (pintype "bidirectional"))
      (node (ref "L217") (pin "1-VDD") (pinfunction "VDD_1-VDD") (pintype "bidirectional"))
      (node (ref "L218") (pin "1-VDD") (pinfunction "VDD_1-VDD") (pintype "bidirectional"))
      (node (ref "L219") (pin "1-VDD") (pinfunction "VDD_1-VDD") (pintype "bidirectional"))
      (node (ref "L22") (pin "1-VDD") (pinfunction "VDD_1-VDD") (pintype "bidirectional"))
      (node (ref "L220") (pin "1-VDD") (pinfunction "VDD_1-VDD") (pintype "bidirectional"))
      (node (ref "L221") (pin "1-VDD") (pinfunction "VDD_1-VDD") (pintype "bidirectional"))
      (node (ref "L222") (pin "1-VDD") (pinfunction "VDD_1-VDD") (pintype "bidirectional"))
      (node (ref "L223") (pin "1-VDD") (pinfunction "VDD_1-VDD") (pintype "bidirectional"))
      (node (ref "L224") (pin "1-VDD") (pinfunction "VDD_1-VDD") (pintype "bidirectional"))
      (node (ref "L225") (pin "1-VDD") (pinfunction "VDD_1-VDD") (pintype "bidirectional"))
      (node (ref "L226") (pin "1-VDD") (pinfunction "VDD_1-VDD") (pintype "bidirectional"))
      (node (ref "L227") (pin "1-VDD") (pinfunction "VDD_1-VDD") (pintype "bidirectional"))
      (node (ref "L228") (pin "1-VDD") (pinfunction "VDD_1-VDD") (pintype "bidirectional"))
      (node (ref "L229") (pin "1-VDD") (pinfunction "VDD_1-VDD") (pintype "bidirectional"))
      (node (ref "L23") (pin "1-VDD") (pinfunction "VDD_1-VDD") (pintype "bidirectional"))
      (node (ref "L230") (pin "1-VDD") (pinfunction "VDD_1-VDD") (pintype "bidirectional"))
      (node (ref "L231") (pin "1-VDD") (pinfunction "VDD_1-VDD") (pintype "bidirectional"))
      (node (ref "L232") (pin "1-VDD") (pinfunction "VDD_1-VDD") (pintype "bidirectional"))
      (node (ref "L233") (pin "1-VDD") (pinfunction "VDD_1-VDD") (pintype "bidirectional"))
      (node (ref "L234") (pin "1-VDD") (pinfunction "VDD_1-VDD") (pintype "bidirectional"))
      (node (ref "L235") (pin "1-VDD") (pinfunction "VDD_1-VDD") (pintype "bidirectional"))
      (node (ref "L236") (pin "1-VDD") (pinfunction "VDD_1-VDD") (pintype "bidirectional"))
      (node (ref "L237") (pin "1-VDD") (pinfunction "VDD_1-VDD") (pintype "bidirectional"))
      (node (ref "L238") (pin "1-VDD") (pinfunction "VDD_1-VDD") (pintype "bidirectional"))
      (node (ref "L239") (pin "1-VDD") (pinfunction "VDD_1-VDD") (pintype "bidirectional"))
      (node (ref "L24") (pin "1-VDD") (pinfunction "VDD_1-VDD") (pintype "bidirectional"))
      (node (ref "L240") (pin "1-VDD") (pinfunction "VDD_1-VDD") (pintype "bidirectional"))
      (node (ref "L241") (pin "1-VDD") (pinfunction "VDD_1-VDD") (pintype "bidirectional"))
      (node (ref "L242") (pin "1-VDD") (pinfunction "VDD_1-VDD") (pintype "bidirectional"))
      (node (ref "L243") (pin "1-VDD") (pinfunction "VDD_1-VDD") (pintype "bidirectional"))
      (node (ref "L244") (pin "1-VDD") (pinfunction "VDD_1-VDD") (pintype "bidirectional"))
      (node (ref "L245") (pin "1-VDD") (pinfunction "VDD_1-VDD") (pintype "bidirectional"))
      (node (ref "L246") (pin "1-VDD") (pinfunction "VDD_1-VDD") (pintype "bidirectional"))
      (node (ref "L247") (pin "1-VDD") (pinfunction "VDD_1-VDD") (pintype "bidirectional"))
      (node (ref "L248") (pin "1-VDD") (pinfunction "VDD_1-VDD") (pintype "bidirectional"))
      (node (ref "L249") (pin "1-VDD") (pinfunction "VDD_1-VDD") (pintype "bidirectional"))
      (node (ref "L25") (pin "1-VDD") (pinfunction "VDD_1-VDD") (pintype "bidirectional"))
      (node (ref "L250") (pin "1-VDD") (pinfunction "VDD_1-VDD") (pintype "bidirectional"))
      (node (ref "L251") (pin "1-VDD") (pinfunction "VDD_1-VDD") (pintype "bidirectional"))
      (node (ref "L252") (pin "1-VDD") (pinfunction "VDD_1-VDD") (pintype "bidirectional"))
      (node (ref "L253") (pin "1-VDD") (pinfunction "VDD_1-VDD") (pintype "bidirectional"))
      (node (ref "L254") (pin "1-VDD") (pinfunction "VDD_1-VDD") (pintype "bidirectional"))
      (node (ref "L255") (pin "1-VDD") (pinfunction "VDD_1-VDD") (pintype "bidirectional"))
      (node (ref "L256") (pin "1-VDD") (pinfunction "VDD_1-VDD") (pintype "bidirectional"))
      (node (ref "L26") (pin "1-VDD") (pinfunction "VDD_1-VDD") (pintype "bidirectional"))
      (node (ref "L27") (pin "1-VDD") (pinfunction "VDD_1-VDD") (pintype "bidirectional"))
      (node (ref "L28") (pin "1-VDD") (pinfunction "VDD_1-VDD") (pintype "bidirectional"))
      (node (ref "L29") (pin "1-VDD") (pinfunction "VDD_1-VDD") (pintype "bidirectional"))
      (node (ref "L3") (pin "1-VDD") (pinfunction "VDD_1-VDD") (pintype "bidirectional"))
      (node (ref "L30") (pin "1-VDD") (pinfunction "VDD_1-VDD") (pintype "bidirectional"))
      (node (ref "L31") (pin "1-VDD") (pinfunction "VDD_1-VDD") (pintype "bidirectional"))
      (node (ref "L32") (pin "1-VDD") (pinfunction "VDD_1-VDD") (pintype "bidirectional"))
      (node (ref "L33") (pin "1-VDD") (pinfunction "VDD_1-VDD") (pintype "bidirectional"))
      (node (ref "L34") (pin "1-VDD") (pinfunction "VDD_1-VDD") (pintype "bidirectional"))
      (node (ref "L35") (pin "1-VDD") (pinfunction "VDD_1-VDD") (pintype "bidirectional"))
      (node (ref "L36") (pin "1-VDD") (pinfunction "VDD_1-VDD") (pintype "bidirectional"))
      (node (ref "L37") (pin "1-VDD") (pinfunction "VDD_1-VDD") (pintype "bidirectional"))
      (node (ref "L38") (pin "1-VDD") (pinfunction "VDD_1-VDD") (pintype "bidirectional"))
      (node (ref "L39") (pin "1-VDD") (pinfunction "VDD_1-VDD") (pintype "bidirectional"))
      (node (ref "L4") (pin "1-VDD") (pinfunction "VDD_1-VDD") (pintype "bidirectional"))
      (node (ref "L40") (pin "1-VDD") (pinfunction "VDD_1-VDD") (pintype "bidirectional"))
      (node (ref "L41") (pin "1-VDD") (pinfunction "VDD_1-VDD") (pintype "bidirectional"))
      (node (ref "L42") (pin "1-VDD") (pinfunction "VDD_1-VDD") (pintype "bidirectional"))
      (node (ref "L43") (pin "1-VDD") (pinfunction "VDD_1-VDD") (pintype "bidirectional"))
      (node (ref "L44") (pin "1-VDD") (pinfunction "VDD_1-VDD") (pintype "bidirectional"))
      (node (ref "L45") (pin "1-VDD") (pinfunction "VDD_1-VDD") (pintype "bidirectional"))
      (node (ref "L46") (pin "1-VDD") (pinfunction "VDD_1-VDD") (pintype "bidirectional"))
      (node (ref "L47") (pin "1-VDD") (pinfunction "VDD_1-VDD") (pintype "bidirectional"))
      (node (ref "L48") (pin "1-VDD") (pinfunction "VDD_1-VDD") (pintype "bidirectional"))
      (node (ref "L49") (pin "1-VDD") (pinfunction "VDD_1-VDD") (pintype "bidirectional"))
      (node (ref "L5") (pin "1-VDD") (pinfunction "VDD_1-VDD") (pintype "bidirectional"))
      (node (ref "L50") (pin "1-VDD") (pinfunction "VDD_1-VDD") (pintype "bidirectional"))
      (node (ref "L51") (pin "1-VDD") (pinfunction "VDD_1-VDD") (pintype "bidirectional"))
      (node (ref "L52") (pin "1-VDD") (pinfunction "VDD_1-VDD") (pintype "bidirectional"))
      (node (ref "L53") (pin "1-VDD") (pinfunction "VDD_1-VDD") (pintype "bidirectional"))
      (node (ref "L54") (pin "1-VDD") (pinfunction "VDD_1-VDD") (pintype "bidirectional"))
      (node (ref "L55") (pin "1-VDD") (pinfunction "VDD_1-VDD") (pintype "bidirectional"))
      (node (ref "L56") (pin "1-VDD") (pinfunction "VDD_1-VDD") (pintype "bidirectional"))
      (node (ref "L57") (pin "1-VDD") (pinfunction "VDD_1-VDD") (pintype "bidirectional"))
      (node (ref "L58") (pin "1-VDD") (pinfunction "VDD_1-VDD") (pintype "bidirectional"))
      (node (ref "L59") (pin "1-VDD") (pinfunction "VDD_1-VDD") (pintype "bidirectional"))
      (node (ref "L6") (pin "1-VDD") (pinfunction "VDD_1-VDD") (pintype "bidirectional"))
      (node (ref "L60") (pin "1-VDD") (pinfunction "VDD_1-VDD") (pintype "bidirectional"))
      (node (ref "L61") (pin "1-VDD") (pinfunction "VDD_1-VDD") (pintype "bidirectional"))
      (node (ref "L62") (pin "1-VDD") (pinfunction "VDD_1-VDD") (pintype "bidirectional"))
      (node (ref "L63") (pin "1-VDD") (pinfunction "VDD_1-VDD") (pintype "bidirectional"))
      (node (ref "L64") (pin "1-VDD") (pinfunction "VDD_1-VDD") (pintype "bidirectional"))
      (node (ref "L65") (pin "1-VDD") (pinfunction "VDD_1-VDD") (pintype "bidirectional"))
      (node (ref "L66") (pin "1-VDD") (pinfunction "VDD_1-VDD") (pintype "bidirectional"))
      (node (ref "L67") (pin "1-VDD") (pinfunction "VDD_1-VDD") (pintype "bidirectional"))
      (node (ref "L68") (pin "1-VDD") (pinfunction "VDD_1-VDD") (pintype "bidirectional"))
      (node (ref "L69") (pin "1-VDD") (pinfunction "VDD_1-VDD") (pintype "bidirectional"))
      (node (ref "L7") (pin "1-VDD") (pinfunction "VDD_1-VDD") (pintype "bidirectional"))
      (node (ref "L70") (pin "1-VDD") (pinfunction "VDD_1-VDD") (pintype "bidirectional"))
      (node (ref "L71") (pin "1-VDD") (pinfunction "VDD_1-VDD") (pintype "bidirectional"))
      (node (ref "L72") (pin "1-VDD") (pinfunction "VDD_1-VDD") (pintype "bidirectional"))
      (node (ref "L73") (pin "1-VDD") (pinfunction "VDD_1-VDD") (pintype "bidirectional"))
      (node (ref "L74") (pin "1-VDD") (pinfunction "VDD_1-VDD") (pintype "bidirectional"))
      (node (ref "L75") (pin "1-VDD") (pinfunction "VDD_1-VDD") (pintype "bidirectional"))
      (node (ref "L76") (pin "1-VDD") (pinfunction "VDD_1-VDD") (pintype "bidirectional"))
      (node (ref "L77") (pin "1-VDD") (pinfunction "VDD_1-VDD") (pintype "bidirectional"))
      (node (ref "L78") (pin "1-VDD") (pinfunction "VDD_1-VDD") (pintype "bidirectional"))
      (node (ref "L79") (pin "1-VDD") (pinfunction "VDD_1-VDD") (pintype "bidirectional"))
      (node (ref "L8") (pin "1-VDD") (pinfunction "VDD_1-VDD") (pintype "bidirectional"))
      (node (ref "L80") (pin "1-VDD") (pinfunction "VDD_1-VDD") (pintype "bidirectional"))
      (node (ref "L81") (pin "1-VDD") (pinfunction "VDD_1-VDD") (pintype "bidirectional"))
      (node (ref "L82") (pin "1-VDD") (pinfunction "VDD_1-VDD") (pintype "bidirectional"))
      (node (ref "L83") (pin "1-VDD") (pinfunction "VDD_1-VDD") (pintype "bidirectional"))
      (node (ref "L84") (pin "1-VDD") (pinfunction "VDD_1-VDD") (pintype "bidirectional"))
      (node (ref "L85") (pin "1-VDD") (pinfunction "VDD_1-VDD") (pintype "bidirectional"))
      (node (ref "L86") (pin "1-VDD") (pinfunction "VDD_1-VDD") (pintype "bidirectional"))
      (node (ref "L87") (pin "1-VDD") (pinfunction "VDD_1-VDD") (pintype "bidirectional"))
      (node (ref "L88") (pin "1-VDD") (pinfunction "VDD_1-VDD") (pintype "bidirectional"))
      (node (ref "L89") (pin "1-VDD") (pinfunction "VDD_1-VDD") (pintype "bidirectional"))
      (node (ref "L9") (pin "1-VDD") (pinfunction "VDD_1-VDD") (pintype "bidirectional"))
      (node (ref "L90") (pin "1-VDD") (pinfunction "VDD_1-VDD") (pintype "bidirectional"))
      (node (ref "L91") (pin "1-VDD") (pinfunction "VDD_1-VDD") (pintype "bidirectional"))
      (node (ref "L92") (pin "1-VDD") (pinfunction "VDD_1-VDD") (pintype "bidirectional"))
      (node (ref "L93") (pin "1-VDD") (pinfunction "VDD_1-VDD") (pintype "bidirectional"))
      (node (ref "L94") (pin "1-VDD") (pinfunction "VDD_1-VDD") (pintype "bidirectional"))
      (node (ref "L95") (pin "1-VDD") (pinfunction "VDD_1-VDD") (pintype "bidirectional"))
      (node (ref "L96") (pin "1-VDD") (pinfunction "VDD_1-VDD") (pintype "bidirectional"))
      (node (ref "L97") (pin "1-VDD") (pinfunction "VDD_1-VDD") (pintype "bidirectional"))
      (node (ref "L98") (pin "1-VDD") (pinfunction "VDD_1-VDD") (pintype "bidirectional"))
      (node (ref "L99") (pin "1-VDD") (pinfunction "VDD_1-VDD") (pintype "bidirectional"))
    )
    (net (code "263") (name "unconnected-(L64-DOUT-Pad2-DOUT)") (class "Default")
      (node (ref "L64") (pin "2-DOUT") (pinfunction "DOUT_2-DOUT") (pintype "output"))
    )
    (net (code "264") (name "unconnected-(L128-DOUT-Pad2-DOUT)") (class "Default")
      (node (ref "L128") (pin "2-DOUT") (pinfunction "DOUT_2-DOUT") (pintype "output"))
    )
    (net (code "265") (name "unconnected-(L192-DOUT-Pad2-DOUT)") (class "Default")
      (node (ref "L192") (pin "2-DOUT") (pinfunction "DOUT_2-DOUT") (pintype "output"))
    )
    (net (code "266") (name "unconnected-(L256-DOUT-Pad2-DOUT)") (class "Default")
      (node (ref "L256") (pin "2-DOUT") (pinfunction "DOUT_2-DOUT") (pintype "output"))
    )
  )
)
